# Titan_Teknic_v1p01b.net
KiCad netlist of a schematic drawn in EAGLE
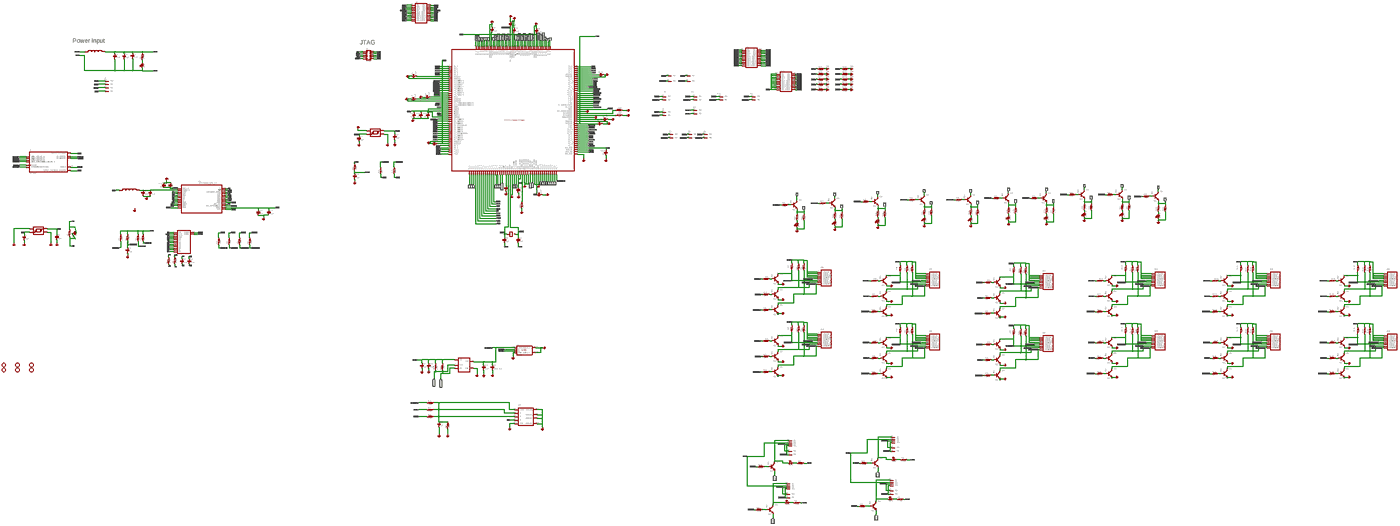
[diagram p0: schematic, sheet 1, overview]
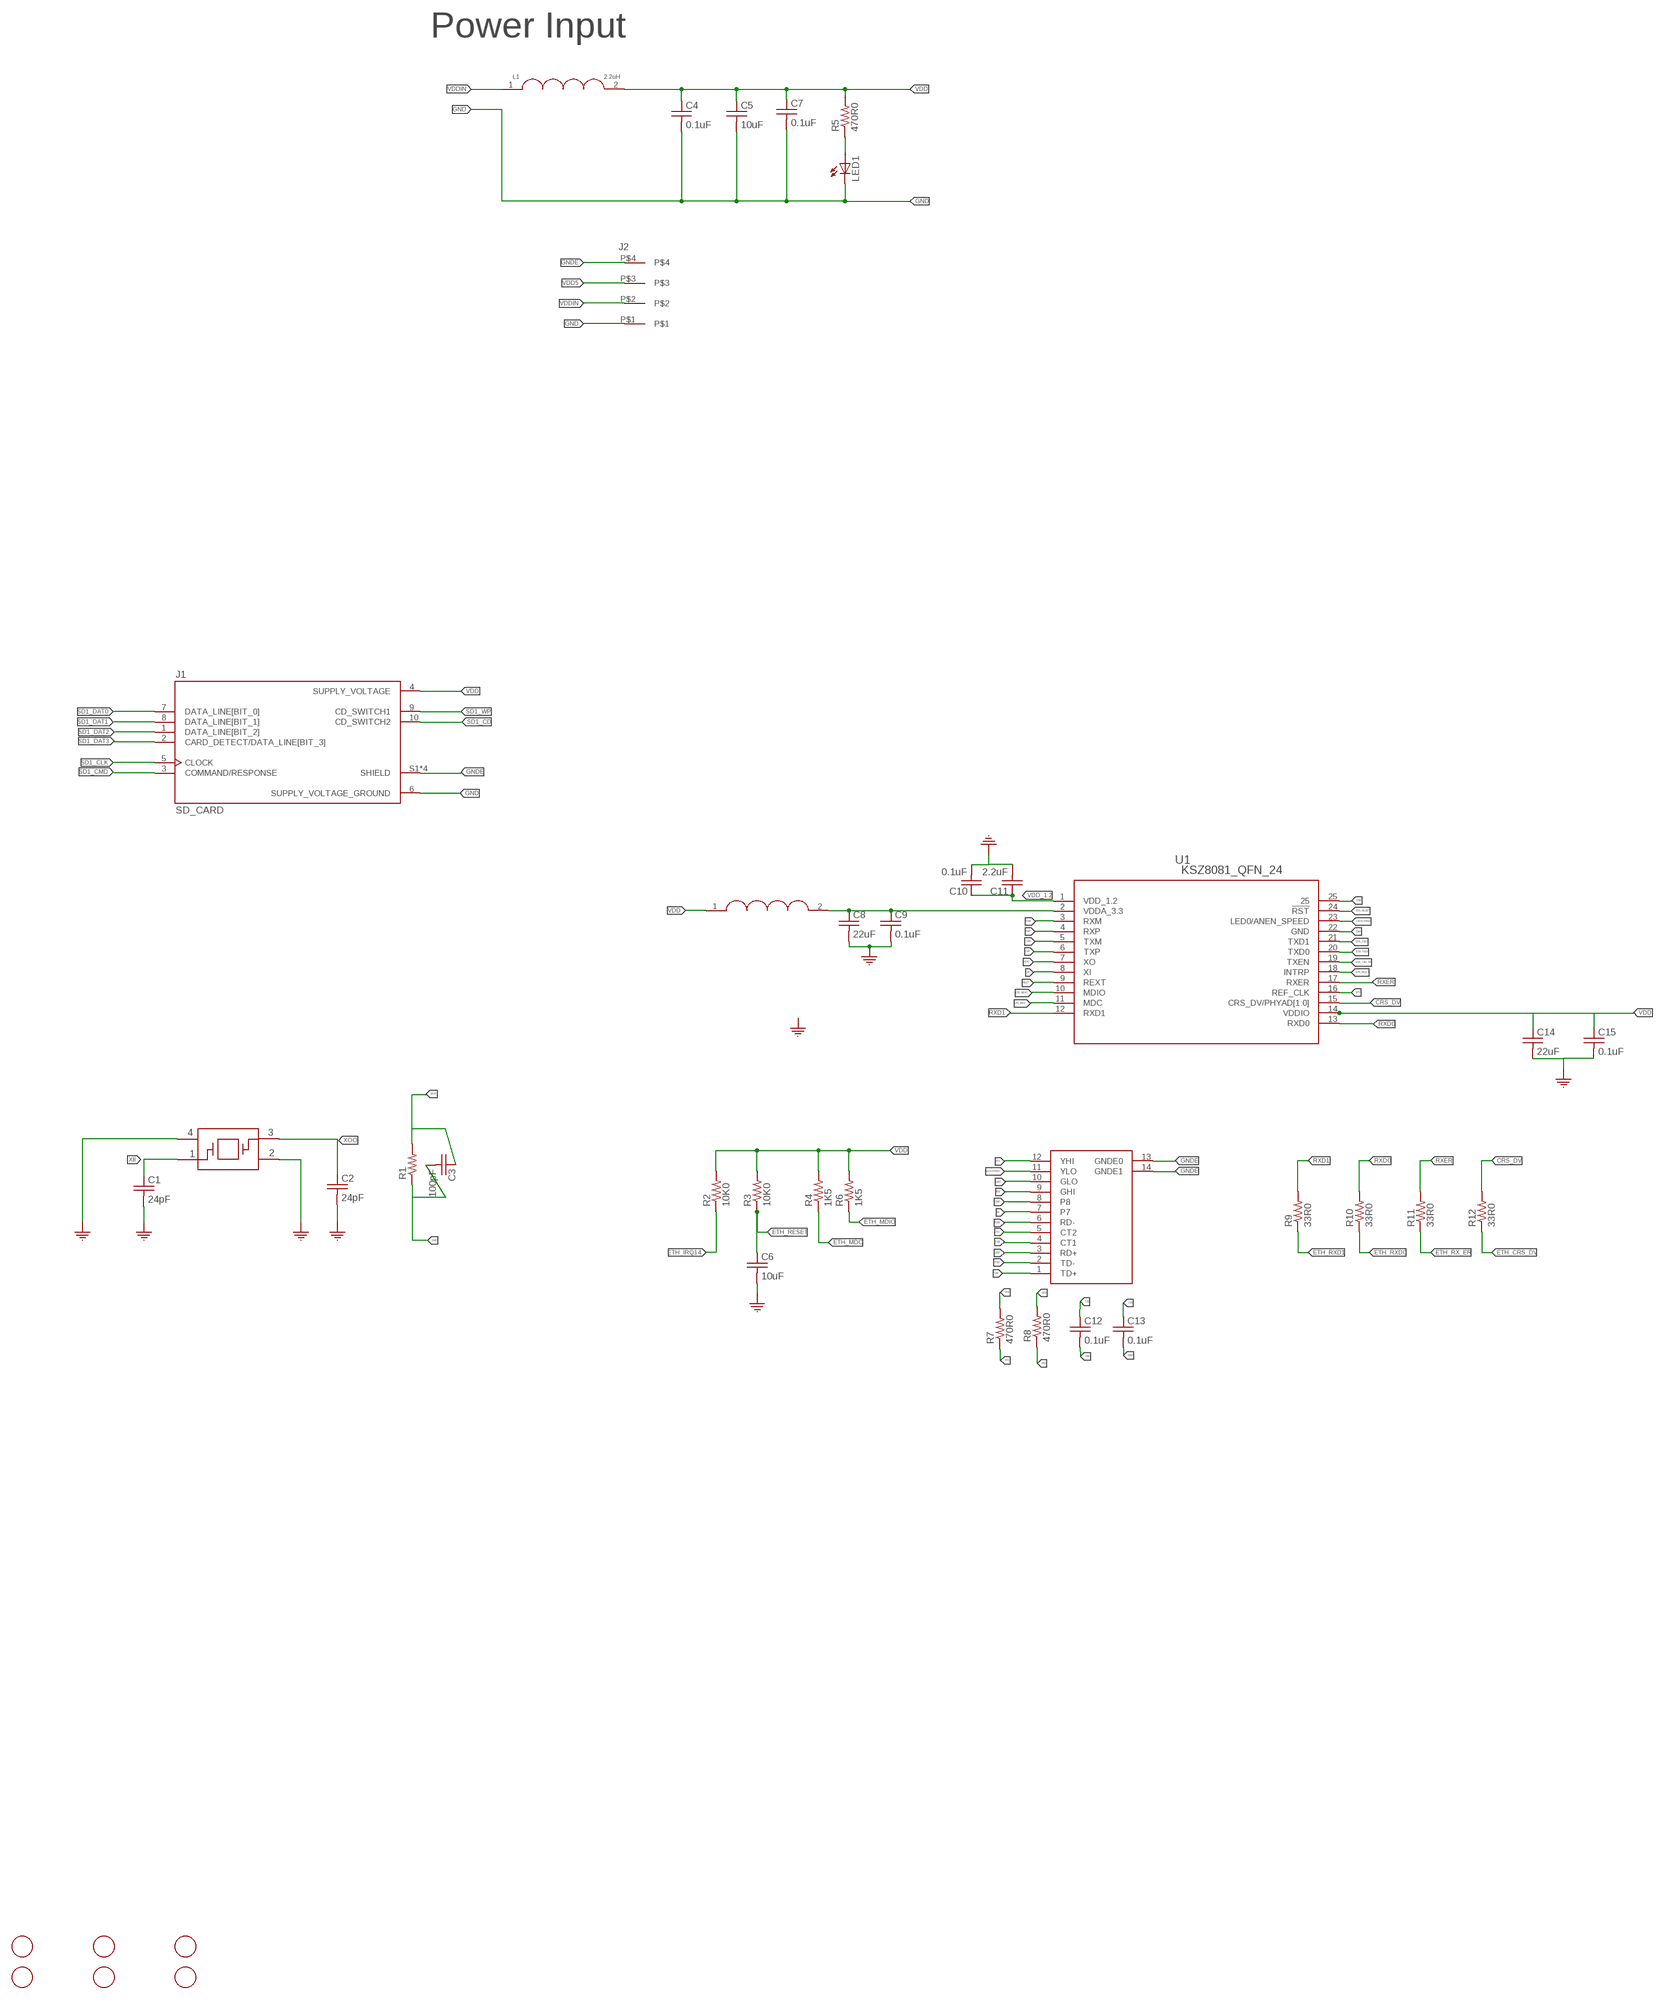
[diagram p1: schematic, sheet 1, part 1 of 6]
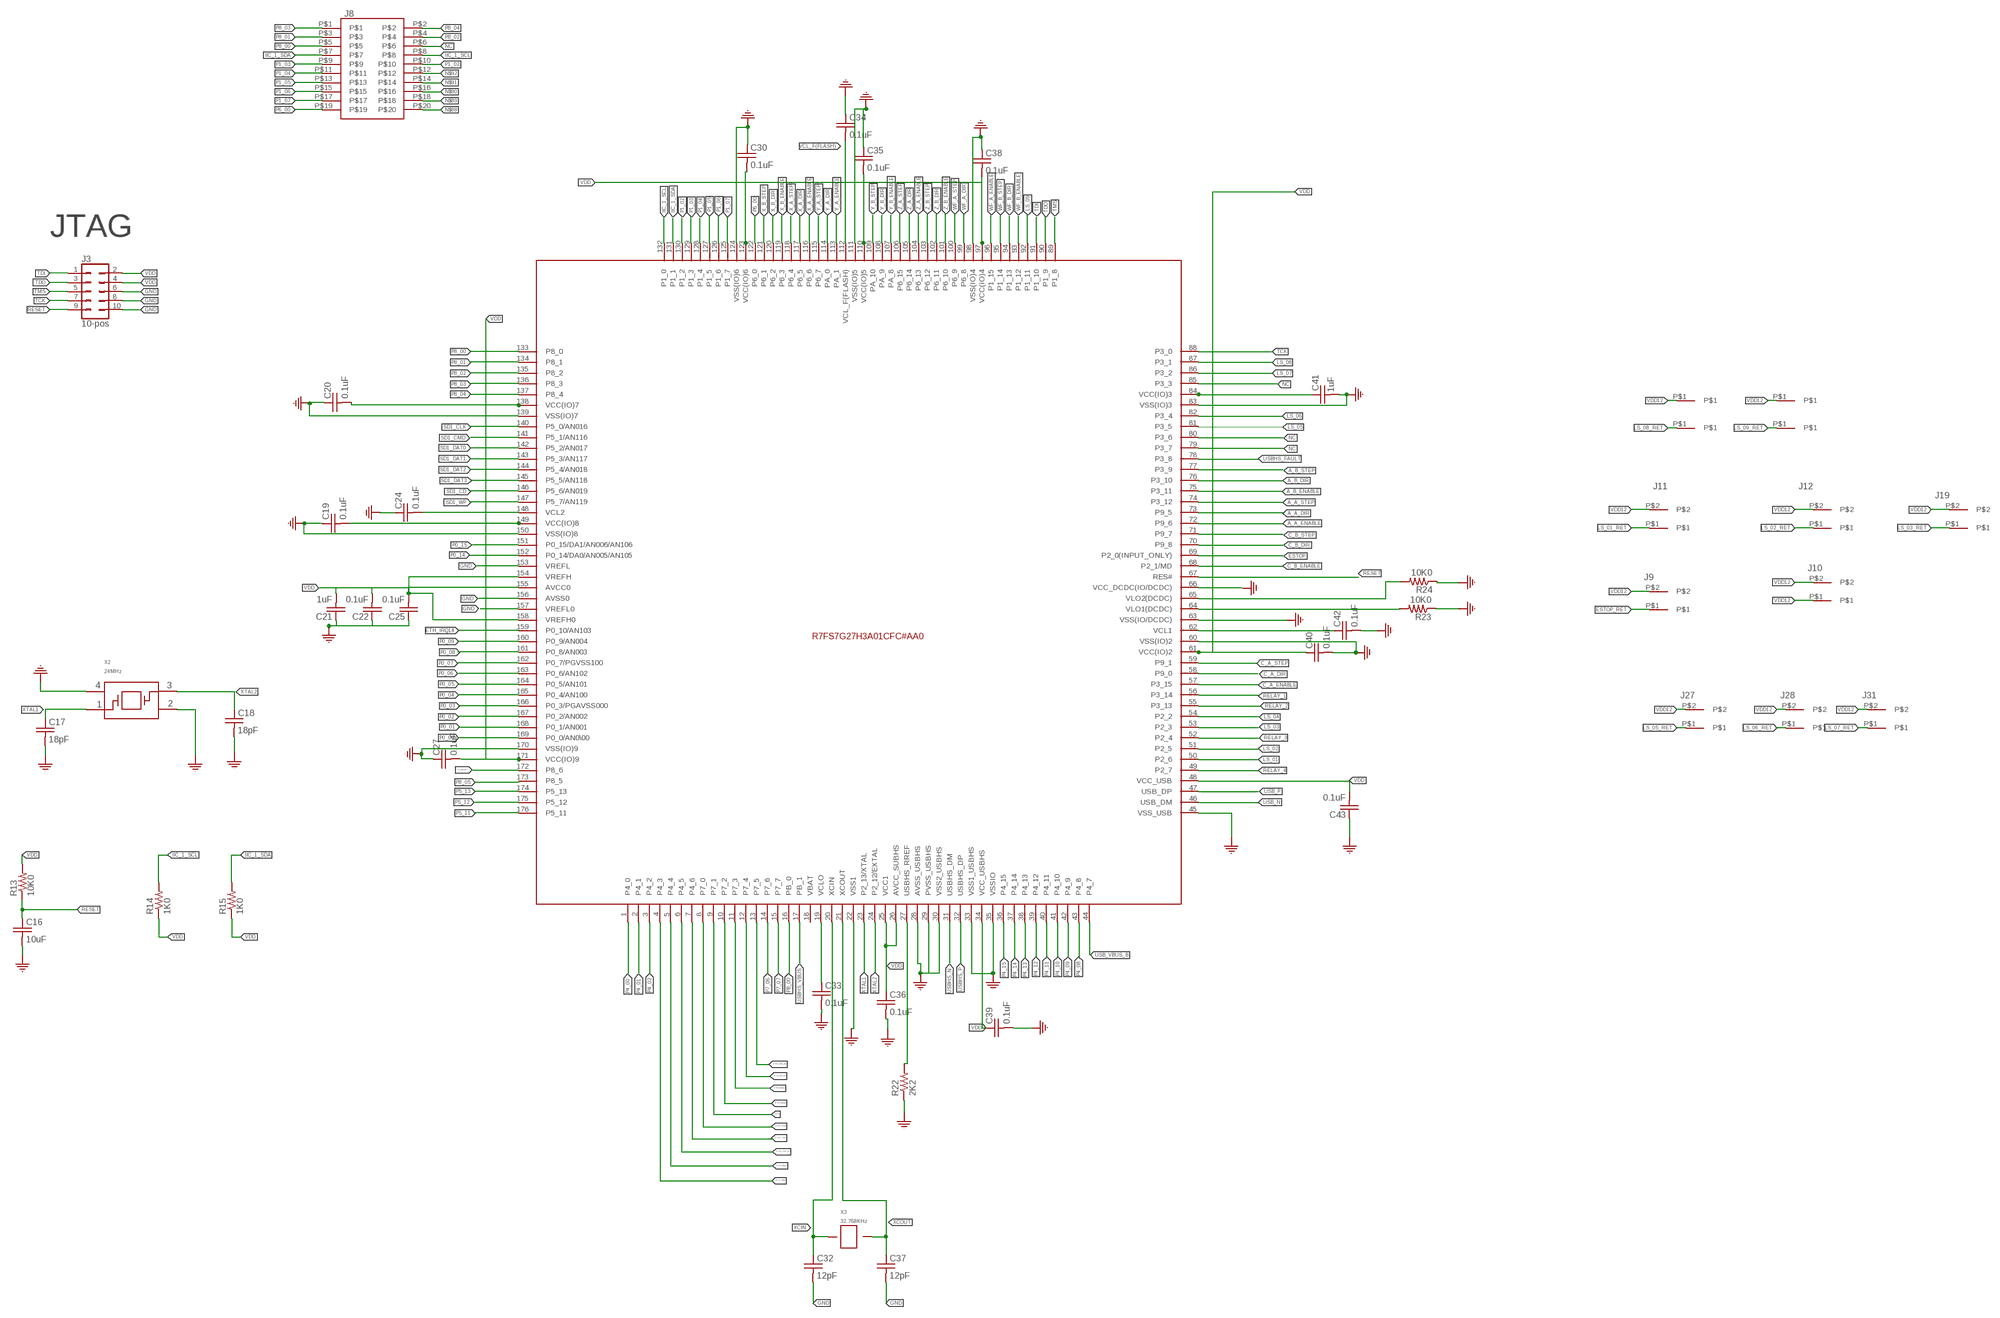
[diagram p2: schematic, sheet 1, part 2 of 6]
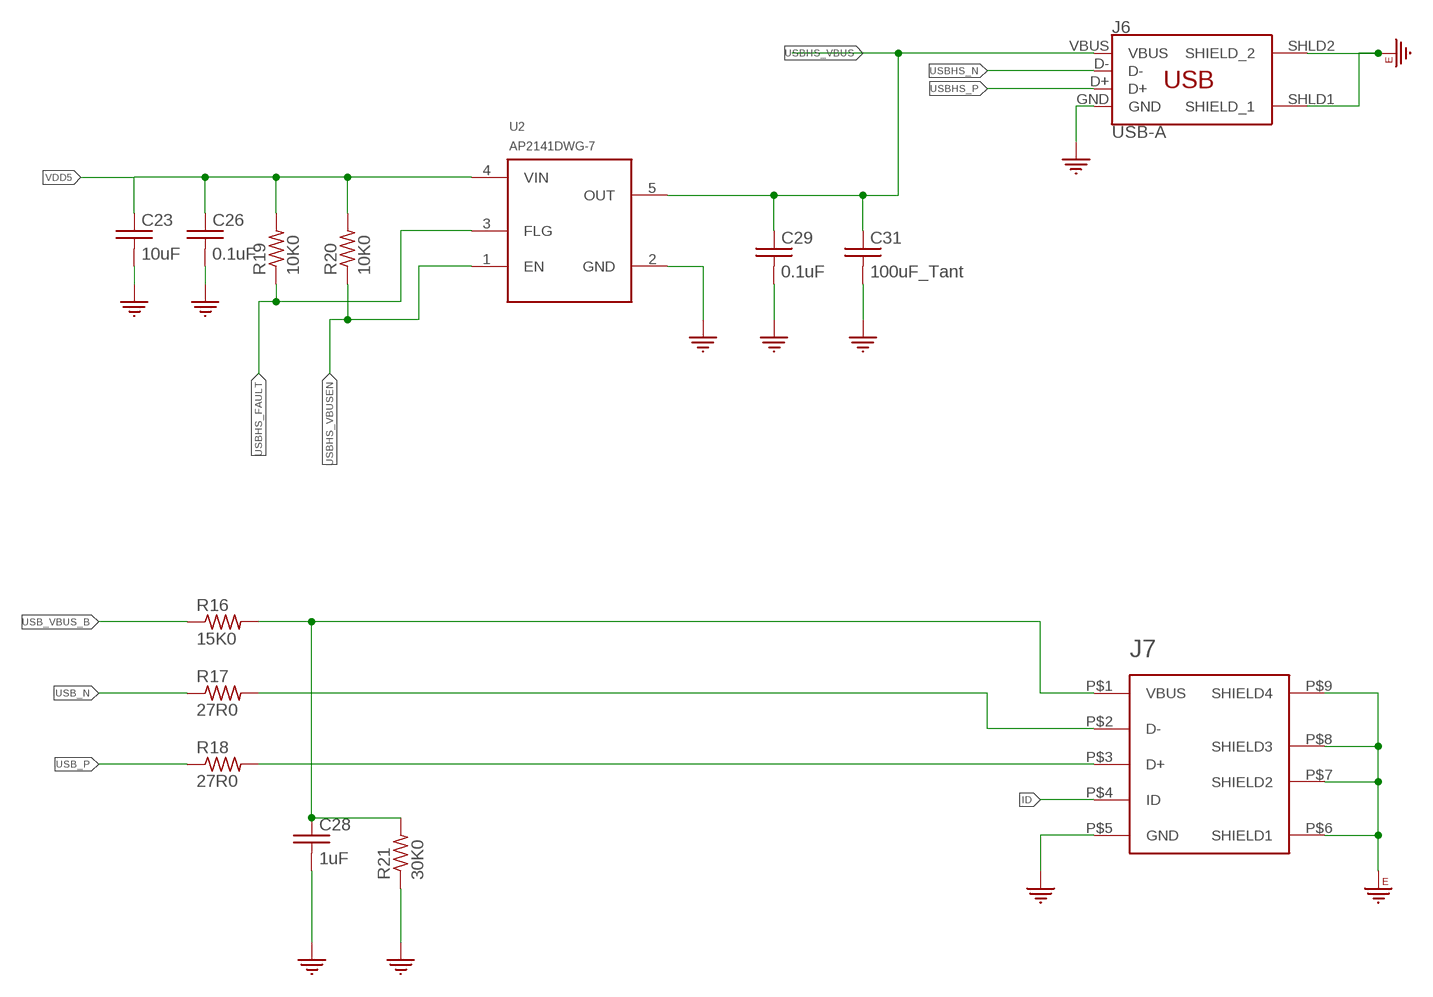
[diagram p3: schematic, sheet 1, part 3 of 6]
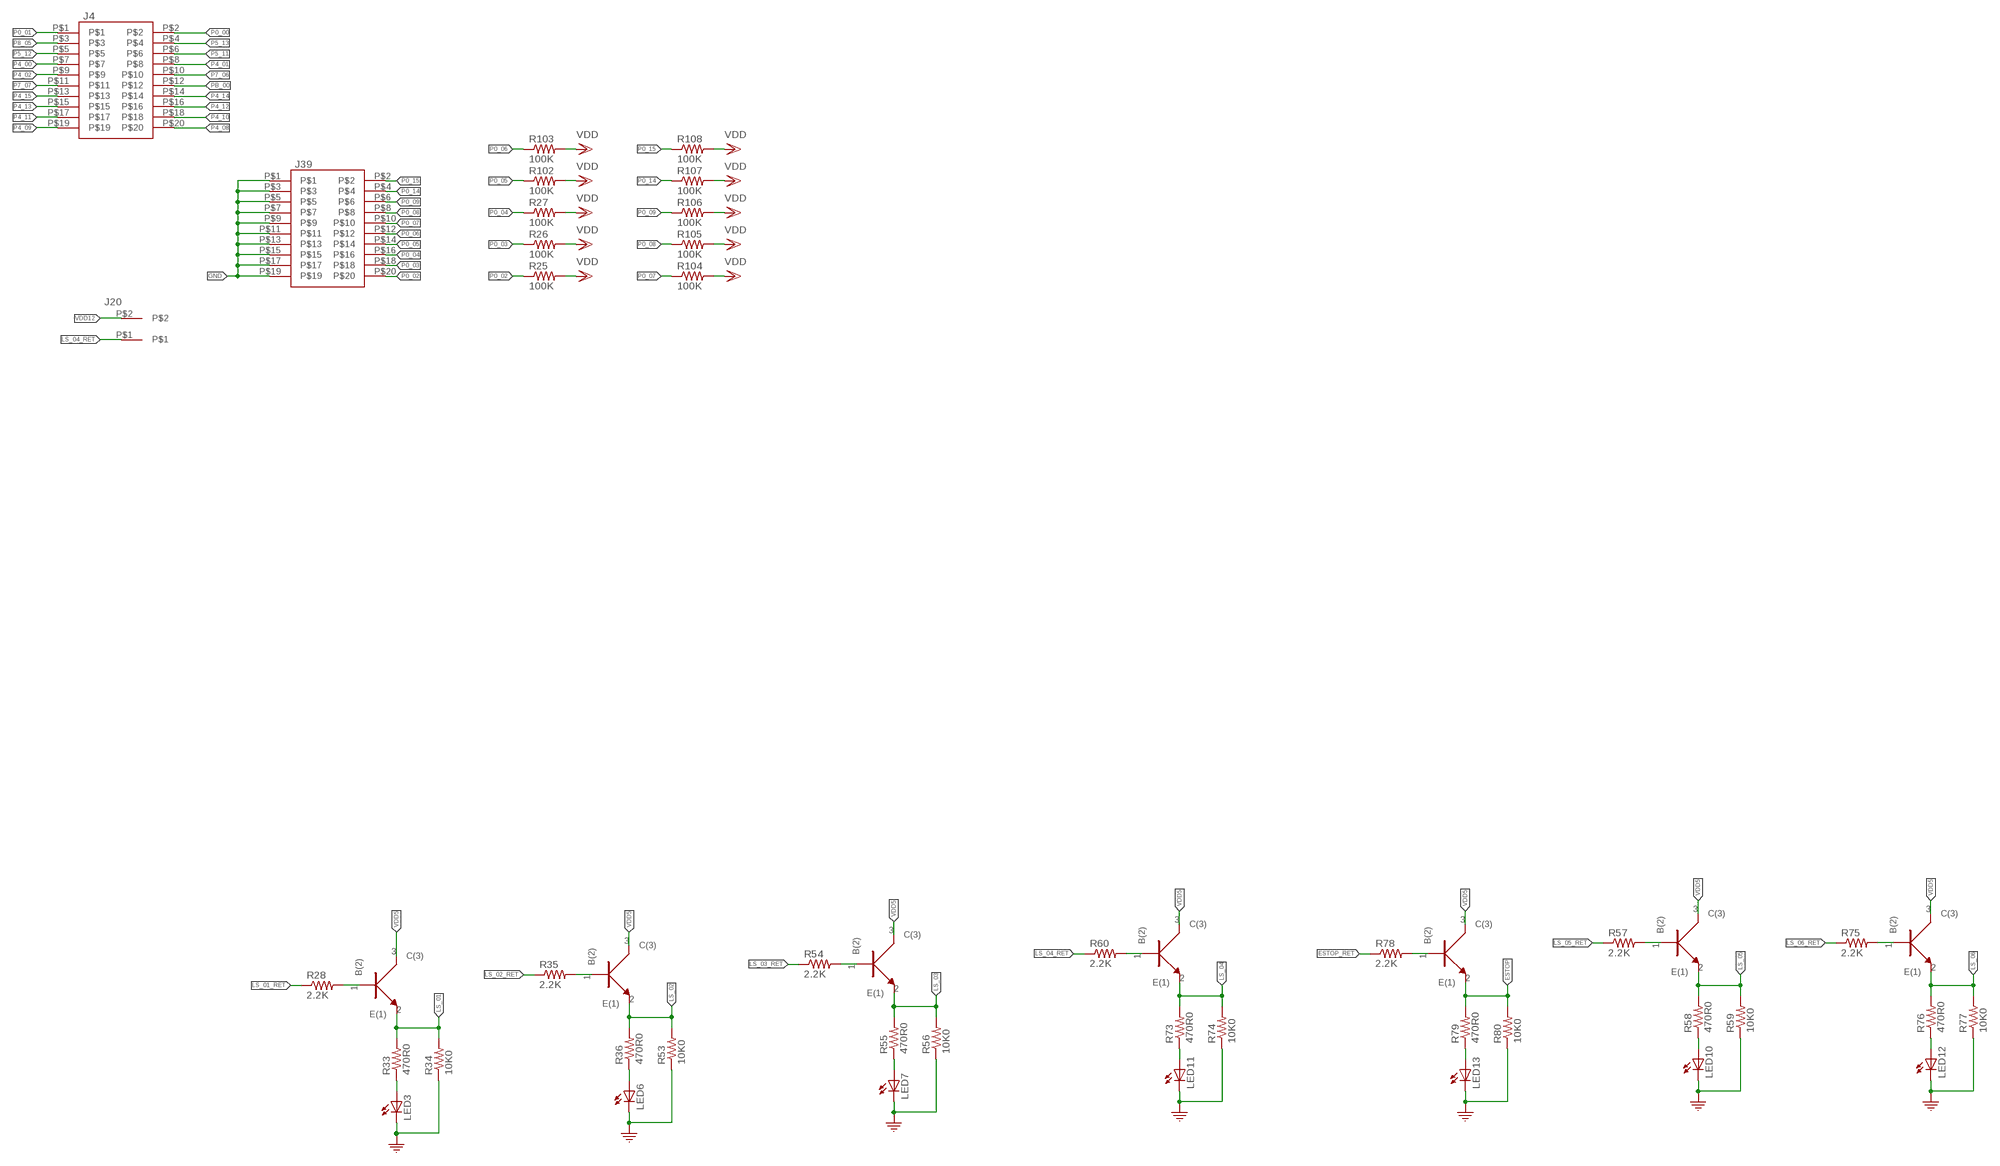
[diagram p4: schematic, sheet 1, part 4 of 6]
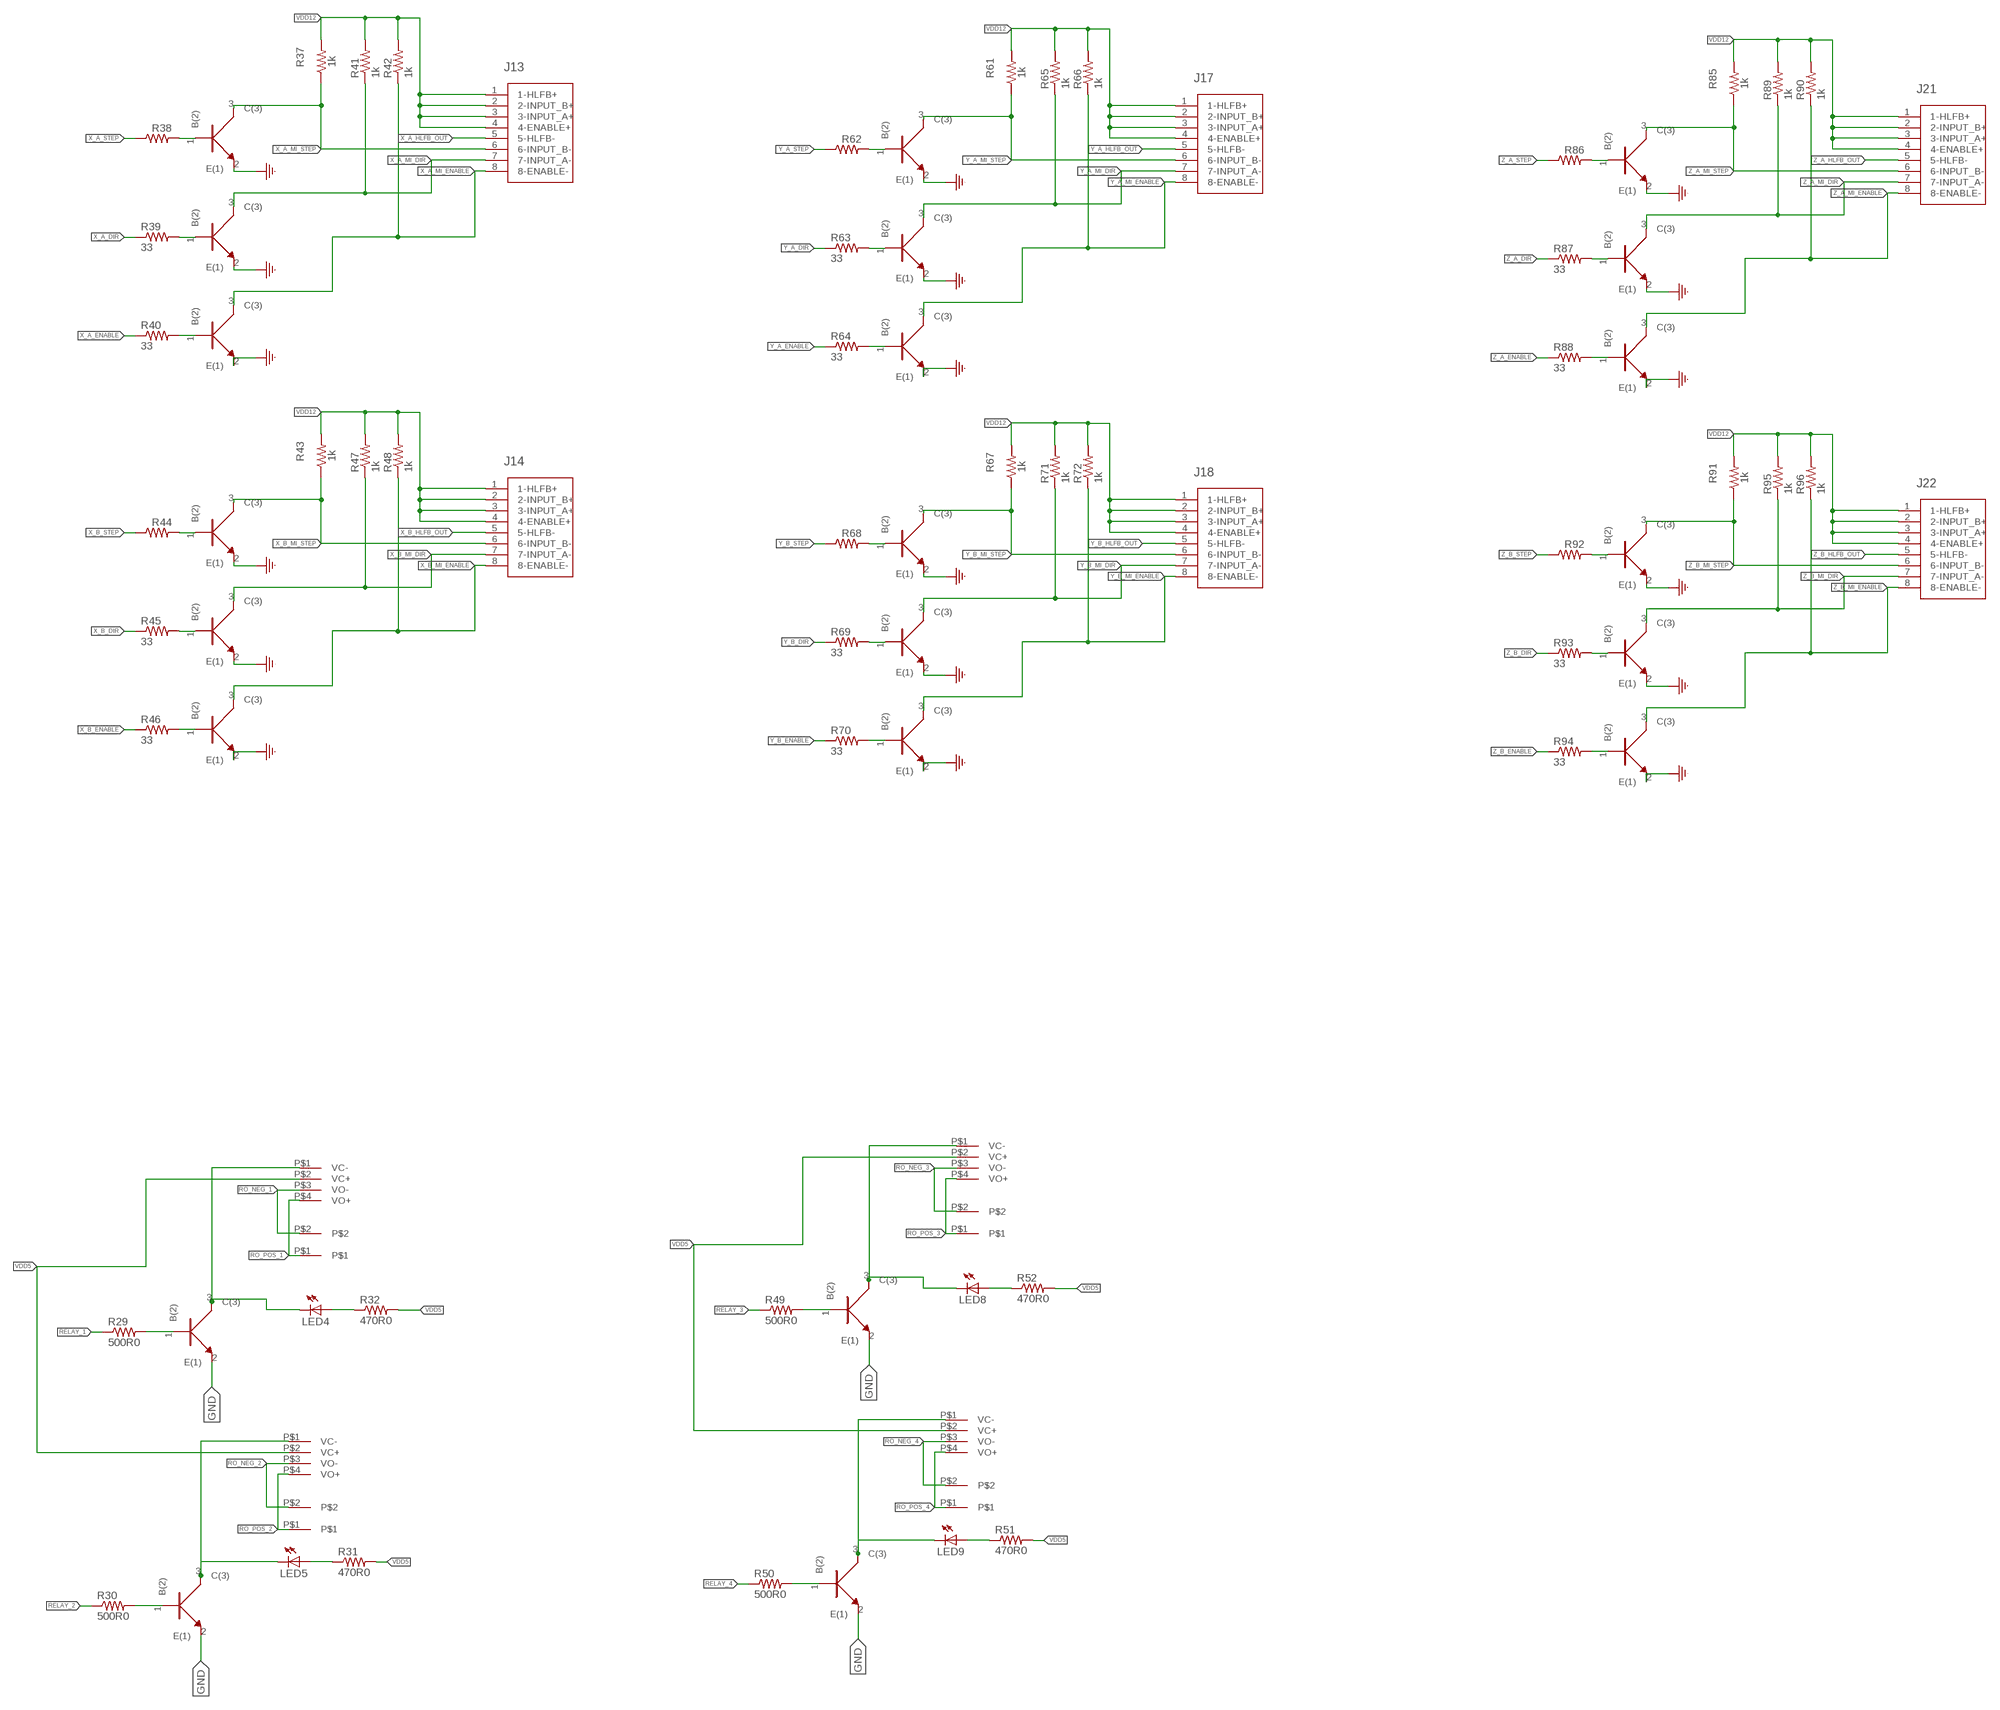
[diagram p5: schematic, sheet 1, part 5 of 6]
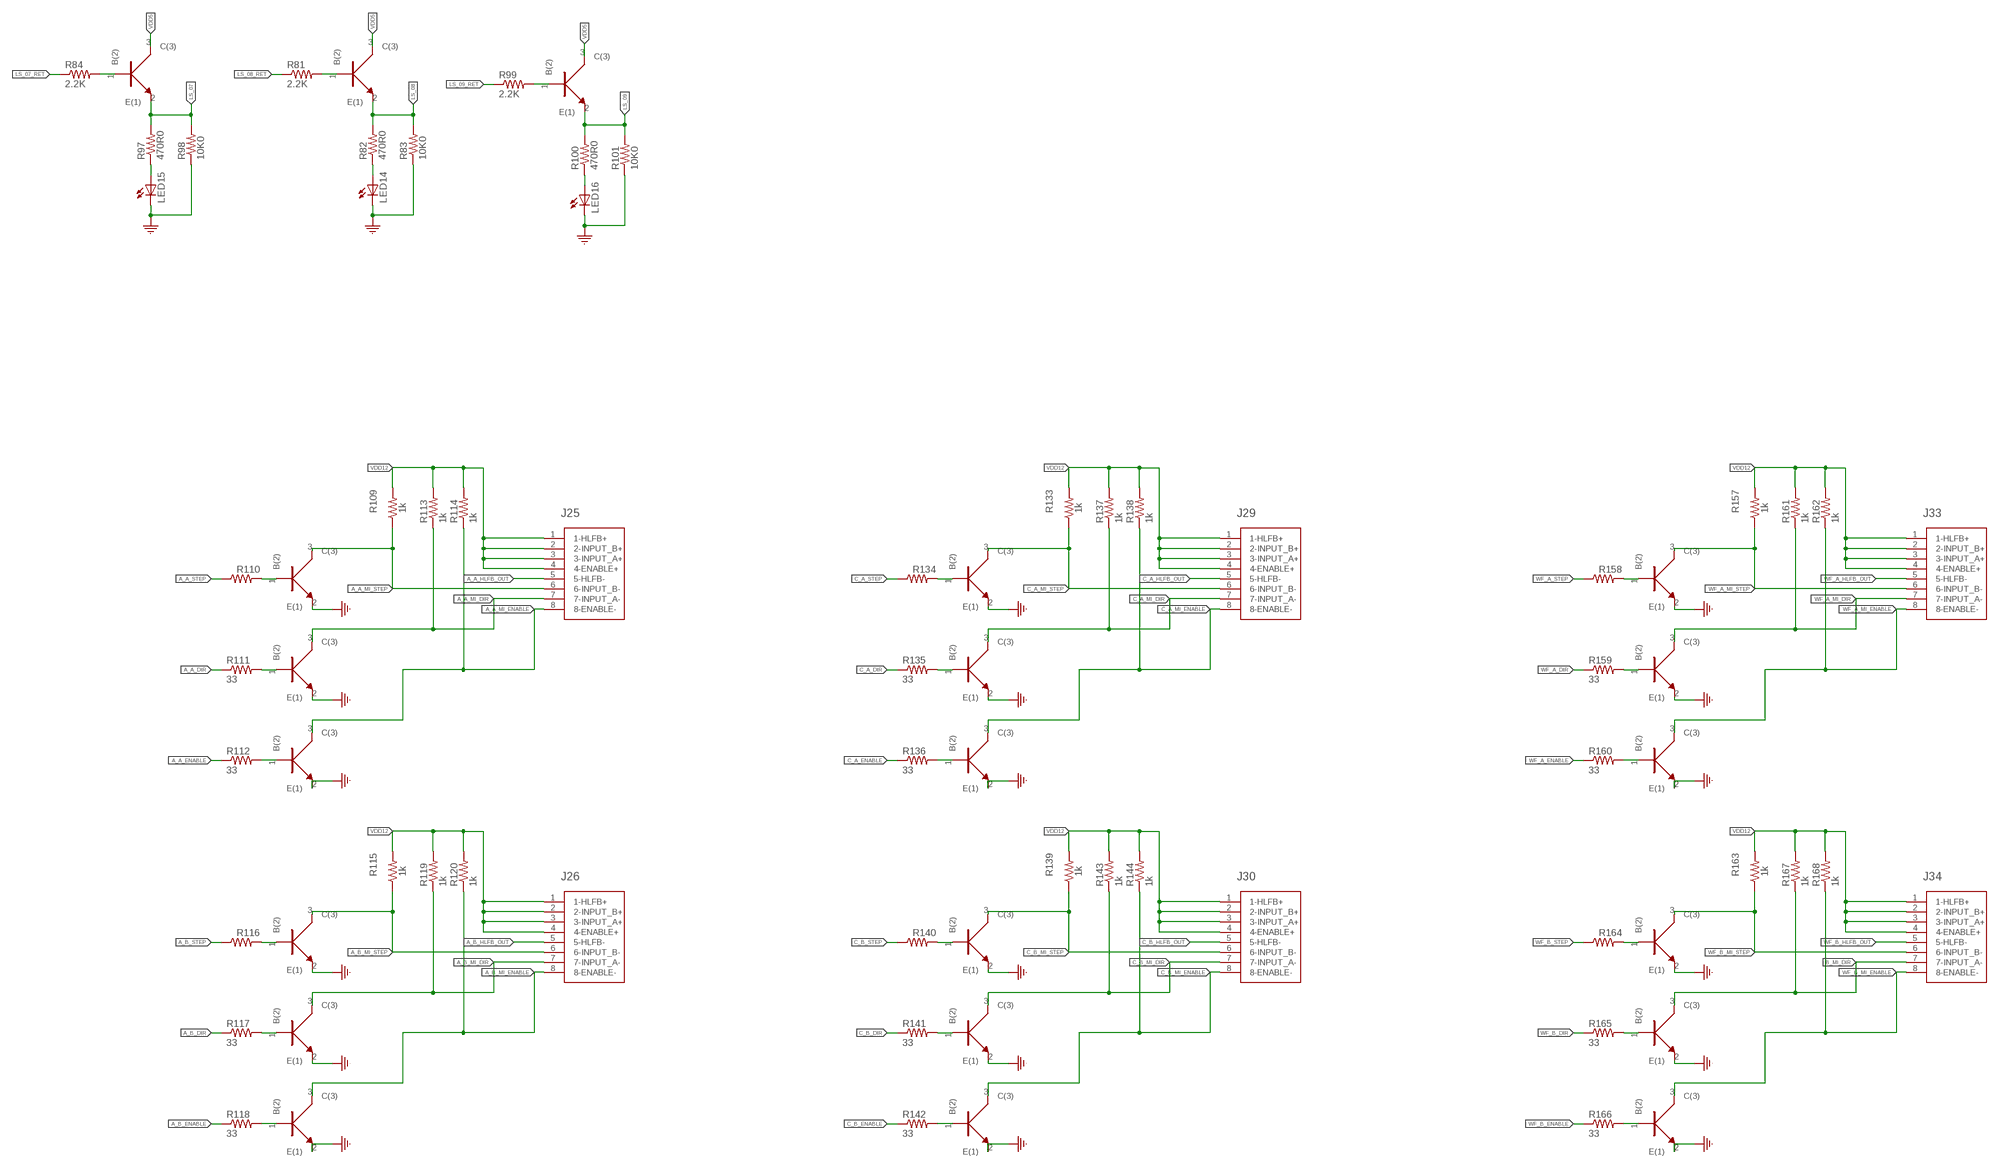
[diagram p6: schematic, sheet 1, part 6 of 6]

(export (version "E")
  (design (tool "Eeschema 10.0.6"))
  (components
    (comp (ref "AFID1")
      (value "FIDUCIAL_1MM")
      (footprint "eagle-import:FIDUCIAL_1MM")
      (libsource (lib "eagle-import") (part "FIDUCIAL_1MM"))
    )
    (comp (ref "AFID2")
      (value "FIDUCIAL_1MM")
      (footprint "eagle-import:FIDUCIAL_1MM")
      (libsource (lib "eagle-import") (part "FIDUCIAL_1MM"))
    )
    (comp (ref "AFID3")
      (value "FIDUCIAL_1MM")
      (footprint "eagle-import:FIDUCIAL_1MM")
      (libsource (lib "eagle-import") (part "FIDUCIAL_1MM"))
    )
    (comp (ref "AFID4")
      (value "FIDUCIAL_1MM")
      (footprint "eagle-import:FIDUCIAL_1MM")
      (libsource (lib "eagle-import") (part "FIDUCIAL_1MM"))
    )
    (comp (ref "AFID5")
      (value "FIDUCIAL_1MM")
      (footprint "eagle-import:FIDUCIAL_1MM")
      (libsource (lib "eagle-import") (part "FIDUCIAL_1MM"))
    )
    (comp (ref "AFID6")
      (value "FIDUCIAL_1MM")
      (footprint "eagle-import:FIDUCIAL_1MM")
      (libsource (lib "eagle-import") (part "FIDUCIAL_1MM"))
    )
    (comp (ref "C1")
      (value "24pF")
      (footprint "eagle-import:0402")
      (fields (field (name "PARTNO") "CC0402GRNPO9BN240"))
      (libsource (lib "eagle-import") (part "C_0402_24PF"))
    )
    (comp (ref "C2")
      (value "24pF")
      (footprint "eagle-import:0402")
      (fields (field (name "PARTNO") "CC0402GRNPO9BN240"))
      (libsource (lib "eagle-import") (part "C_0402_24PF"))
    )
    (comp (ref "C3")
      (value "100pF")
      (footprint "eagle-import:0402")
      (fields (field (name "PARTNO") "CL05C101JB5NNNC"))
      (libsource (lib "eagle-import") (part "C_0402_100PF"))
    )
    (comp (ref "C4")
      (value "0.1uF")
      (footprint "eagle-import:0402")
      (fields (field (name "PARTNO") "CL05F104ZO5NNNC"))
      (libsource (lib "eagle-import") (part "C_0402_0.1UF"))
    )
    (comp (ref "C5")
      (value "10uF")
      (footprint "eagle-import:0402")
      (fields (field (name "PARTNO") "CL05A106MP8NUB8"))
      (libsource (lib "eagle-import") (part "C_0402_10UF"))
    )
    (comp (ref "C6")
      (value "10uF")
      (footprint "eagle-import:0402")
      (fields (field (name "PARTNO") "CL05A106MP8NUB8"))
      (libsource (lib "eagle-import") (part "C_0402_10UF"))
    )
    (comp (ref "C7")
      (value "0.1uF")
      (footprint "eagle-import:0402")
      (fields (field (name "PARTNO") "CL05F104ZO5NNNC"))
      (libsource (lib "eagle-import") (part "C_0402_0.1UF"))
    )
    (comp (ref "C8")
      (value "22uF")
      (footprint "eagle-import:0402")
      (fields (field (name "PARTNO") "CL05A226MQ5N6J8"))
      (libsource (lib "eagle-import") (part "C_0402_22UF"))
    )
    (comp (ref "C9")
      (value "0.1uF")
      (footprint "eagle-import:0402")
      (fields (field (name "PARTNO") "CL05F104ZO5NNNC"))
      (libsource (lib "eagle-import") (part "C_0402_0.1UF"))
    )
    (comp (ref "C10")
      (value "0.1uF")
      (footprint "eagle-import:0402")
      (fields (field (name "PARTNO") "CL05F104ZO5NNNC"))
      (libsource (lib "eagle-import") (part "C_0402_0.1UF"))
    )
    (comp (ref "C11")
      (value "2.2uF")
      (footprint "eagle-import:0402")
      (fields (field (name "PARTNO") "GRM155C81C225ME15D"))
      (libsource (lib "eagle-import") (part "C_0402_2.2UF"))
    )
    (comp (ref "C12")
      (value "0.1uF")
      (footprint "eagle-import:0402")
      (fields (field (name "PARTNO") "CL05F104ZO5NNNC"))
      (libsource (lib "eagle-import") (part "C_0402_0.1UF"))
    )
    (comp (ref "C13")
      (value "0.1uF")
      (footprint "eagle-import:0402")
      (fields (field (name "PARTNO") "CL05F104ZO5NNNC"))
      (libsource (lib "eagle-import") (part "C_0402_0.1UF"))
    )
    (comp (ref "C14")
      (value "22uF")
      (footprint "eagle-import:0402")
      (fields (field (name "PARTNO") "CL05A226MQ5N6J8"))
      (libsource (lib "eagle-import") (part "C_0402_22UF"))
    )
    (comp (ref "C15")
      (value "0.1uF")
      (footprint "eagle-import:0402")
      (fields (field (name "PARTNO") "CL05F104ZO5NNNC"))
      (libsource (lib "eagle-import") (part "C_0402_0.1UF"))
    )
    (comp (ref "C16")
      (value "10uF")
      (footprint "eagle-import:0402")
      (fields (field (name "PARTNO") "CL05A106MP8NUB8"))
      (libsource (lib "eagle-import") (part "C_0402_10UF"))
    )
    (comp (ref "C17")
      (value "18pF")
      (footprint "eagle-import:0402")
      (fields (field (name "PARTNO") "UMK105CG180JV-F"))
      (libsource (lib "eagle-import") (part "C_0402_18PF"))
    )
    (comp (ref "C18")
      (value "18pF")
      (footprint "eagle-import:0402")
      (fields (field (name "PARTNO") "UMK105CG180JV-F"))
      (libsource (lib "eagle-import") (part "C_0402_18PF"))
    )
    (comp (ref "C19")
      (value "0.1uF")
      (footprint "eagle-import:0402")
      (fields (field (name "PARTNO") "CL05F104ZO5NNNC"))
      (libsource (lib "eagle-import") (part "C_0402_0.1UF"))
    )
    (comp (ref "C20")
      (value "0.1uF")
      (footprint "eagle-import:0402")
      (fields (field (name "PARTNO") "CL05F104ZO5NNNC"))
      (libsource (lib "eagle-import") (part "C_0402_0.1UF"))
    )
    (comp (ref "C21")
      (value "1uF")
      (footprint "eagle-import:0402")
      (fields (field (name "PARTNO") "CL05A105KO5NNNC"))
      (libsource (lib "eagle-import") (part "C_0402_1UF"))
    )
    (comp (ref "C22")
      (value "0.1uF")
      (footprint "eagle-import:0402")
      (fields (field (name "PARTNO") "CL05F104ZO5NNNC"))
      (libsource (lib "eagle-import") (part "C_0402_0.1UF"))
    )
    (comp (ref "C23")
      (value "10uF")
      (footprint "eagle-import:0402")
      (fields (field (name "PARTNO") "CL05A106MP8NUB8"))
      (libsource (lib "eagle-import") (part "C_0402_10UF"))
    )
    (comp (ref "C24")
      (value "0.1uF")
      (footprint "eagle-import:0402")
      (fields (field (name "PARTNO") "CL05F104ZO5NNNC"))
      (libsource (lib "eagle-import") (part "C_0402_0.1UF"))
    )
    (comp (ref "C25")
      (value "0.1uF")
      (footprint "eagle-import:0402")
      (fields (field (name "PARTNO") "CL05F104ZO5NNNC"))
      (libsource (lib "eagle-import") (part "C_0402_0.1UF"))
    )
    (comp (ref "C26")
      (value "0.1uF")
      (footprint "eagle-import:0402")
      (fields (field (name "PARTNO") "CL05F104ZO5NNNC"))
      (libsource (lib "eagle-import") (part "C_0402_0.1UF"))
    )
    (comp (ref "C27")
      (value "0.1uF")
      (footprint "eagle-import:0402")
      (fields (field (name "PARTNO") "CL05F104ZO5NNNC"))
      (libsource (lib "eagle-import") (part "C_0402_0.1UF"))
    )
    (comp (ref "C28")
      (value "1uF")
      (footprint "eagle-import:0402")
      (fields (field (name "PARTNO") "CL05A105KO5NNNC"))
      (libsource (lib "eagle-import") (part "C_0402_1UF"))
    )
    (comp (ref "C29")
      (value "0.1uF")
      (footprint "eagle-import:0402")
      (fields (field (name "PARTNO") "CL05F104ZO5NNNC"))
      (libsource (lib "eagle-import") (part "C_0402_0.1UF"))
    )
    (comp (ref "C30")
      (value "0.1uF")
      (footprint "eagle-import:0402")
      (fields (field (name "PARTNO") "CL05F104ZO5NNNC"))
      (libsource (lib "eagle-import") (part "C_0402_0.1UF"))
    )
    (comp (ref "C31")
      (value "100uF_Tant")
      (footprint "eagle-import:C1210")
      (fields (field (name "PARTNO") "TLJT107M010R0900"))
      (libsource (lib "eagle-import") (part "C_1210_100UF_TANT"))
    )
    (comp (ref "C32")
      (value "12pF")
      (footprint "eagle-import:0402")
      (fields (field (name "PARTNO") "CL05C120JB5NNNC"))
      (libsource (lib "eagle-import") (part "C_0402_12PF"))
    )
    (comp (ref "C33")
      (value "0.1uF")
      (footprint "eagle-import:0402")
      (fields (field (name "PARTNO") "CL05F104ZO5NNNC"))
      (libsource (lib "eagle-import") (part "C_0402_0.1UF"))
    )
    (comp (ref "C34")
      (value "0.1uF")
      (footprint "eagle-import:0402")
      (fields (field (name "PARTNO") "CL05F104ZO5NNNC"))
      (libsource (lib "eagle-import") (part "C_0402_0.1UF"))
    )
    (comp (ref "C35")
      (value "0.1uF")
      (footprint "eagle-import:0402")
      (fields (field (name "PARTNO") "CL05F104ZO5NNNC"))
      (libsource (lib "eagle-import") (part "C_0402_0.1UF"))
    )
    (comp (ref "C36")
      (value "0.1uF")
      (footprint "eagle-import:0402")
      (fields (field (name "PARTNO") "CL05F104ZO5NNNC"))
      (libsource (lib "eagle-import") (part "C_0402_0.1UF"))
    )
    (comp (ref "C37")
      (value "12pF")
      (footprint "eagle-import:0402")
      (fields (field (name "PARTNO") "CL05C120JB5NNNC"))
      (libsource (lib "eagle-import") (part "C_0402_12PF"))
    )
    (comp (ref "C38")
      (value "0.1uF")
      (footprint "eagle-import:0402")
      (fields (field (name "PARTNO") "CL05F104ZO5NNNC"))
      (libsource (lib "eagle-import") (part "C_0402_0.1UF"))
    )
    (comp (ref "C39")
      (value "0.1uF")
      (footprint "eagle-import:0402")
      (fields (field (name "PARTNO") "CL05F104ZO5NNNC"))
      (libsource (lib "eagle-import") (part "C_0402_0.1UF"))
    )
    (comp (ref "C40")
      (value "0.1uF")
      (footprint "eagle-import:0402")
      (fields (field (name "PARTNO") "CL05F104ZO5NNNC"))
      (libsource (lib "eagle-import") (part "C_0402_0.1UF"))
    )
    (comp (ref "C41")
      (value "1uF")
      (footprint "eagle-import:0402")
      (fields (field (name "PARTNO") "CL05A105KO5NNNC"))
      (libsource (lib "eagle-import") (part "C_0402_1UF"))
    )
    (comp (ref "C42")
      (value "0.1uF")
      (footprint "eagle-import:0402")
      (fields (field (name "PARTNO") "CL05F104ZO5NNNC"))
      (libsource (lib "eagle-import") (part "C_0402_0.1UF"))
    )
    (comp (ref "C43")
      (value "0.1uF")
      (footprint "eagle-import:0402")
      (fields (field (name "PARTNO") "CL05F104ZO5NNNC"))
      (libsource (lib "eagle-import") (part "C_0402_0.1UF"))
    )
    (comp (ref "FB1")
      (value "FB2_603")
      (footprint "eagle-import:0603")
      (fields (field (name "PARTNO") "BLM18PG121SN1D"))
      (libsource (lib "eagle-import") (part "FB_0603_120_OHM0603"))
    )
    (comp (ref "J1")
      (value "SD_CARD")
      (footprint "eagle-import:SD_CARD")
      (fields (field (name "MF") "Amphenol ICC") (field (name "PARTNO") "114-00841-68"))
      (libsource (lib "eagle-import") (part "SD_CARD_1140084168"))
    )
    (comp (ref "J2")
      (value "4-pos")
      (footprint "eagle-import:1X4_3.81MM_PITCH")
      (fields (field (name "PARTNO") "691322310004"))
      (libsource (lib "eagle-import") (part "3.81MM_1_X_4_RT_ANGLE_PLUG_HEADER"))
    )
    (comp (ref "J3")
      (value "10-pos")
      (footprint "eagle-import:2X5")
      (fields (field (name "PARTNO") "PH2RA-10-UA"))
      (libsource (lib "eagle-import") (part "CONN_05X2_RAPTH"))
    )
    (comp (ref "J4")
      (value "20-pos")
      (footprint "eagle-import:2_X_10_.1_INCH")
      (fields (field (name "PARTNO") "67996-420HLF"))
      (libsource (lib "eagle-import") (part "2_X_10_HEADER_GENERIC"))
    )
    (comp (ref "J6")
      (value "USB-A")
      (footprint "eagle-import:USB_A_SMT")
      (fields (field (name "PARTNO") "87583-3010RPALF"))
      (libsource (lib "eagle-import") (part "USB_A"))
    )
    (comp (ref "J7")
      (value "USB-B-Micro")
      (footprint "eagle-import:USB_MICRO-B")
      (fields (field (name "PARTNO") "10118192-0002LF"))
      (libsource (lib "eagle-import") (part "USB_MICRO-B"))
    )
    (comp (ref "J8")
      (value "2_X_10_HEADER_GENERIC")
      (footprint "eagle-import:2_X_10_.1_INCH")
      (fields (field (name "PARTNO") "67996-420HLF"))
      (libsource (lib "eagle-import") (part "2_X_10_HEADER_GENERIC"))
    )
    (comp (ref "J9")
      (value "2-pos")
      (footprint "eagle-import:2_3.81MM_PITCH")
      (fields (field (name "PARTNO") "691322310002"))
      (libsource (lib "eagle-import") (part "3.81MM_1_X_2_RT_ANGLE_PLUG_HEADER"))
    )
    (comp (ref "J10")
      (value "2-pos")
      (footprint "eagle-import:2_3.81MM_PITCH")
      (fields (field (name "PARTNO") "691322310002"))
      (libsource (lib "eagle-import") (part "3.81MM_1_X_2_RT_ANGLE_PLUG_HEADER"))
    )
    (comp (ref "J11")
      (value "2-pos")
      (footprint "eagle-import:2_3.81MM_PITCH")
      (fields (field (name "PARTNO") "691322310002"))
      (libsource (lib "eagle-import") (part "3.81MM_1_X_2_RT_ANGLE_PLUG_HEADER"))
    )
    (comp (ref "J12")
      (value "2-pos")
      (footprint "eagle-import:2_3.81MM_PITCH")
      (fields (field (name "PARTNO") "691322310002"))
      (libsource (lib "eagle-import") (part "3.81MM_1_X_2_RT_ANGLE_PLUG_HEADER"))
    )
    (comp (ref "J13")
      (value "TEKNIC_MOTOR_8PIN")
      (footprint "eagle-import:CON_39281083")
      (fields
        (field (name "MANUFACTURER_PART_NUMBER") "39281083")
        (field (name "COPYRIGHT") "Copyright (C) 2022 Ultra Librarian. All rights reserved.")
      )
      (libsource (lib "eagle-import") (part "TEKNIC_MOTOR_8PIN"))
    )
    (comp (ref "J14")
      (value "TEKNIC_MOTOR_8PIN")
      (footprint "eagle-import:CON_39281083")
      (fields
        (field (name "MANUFACTURER_PART_NUMBER") "39281083")
        (field (name "COPYRIGHT") "Copyright (C) 2022 Ultra Librarian. All rights reserved.")
      )
      (libsource (lib "eagle-import") (part "TEKNIC_MOTOR_8PIN"))
    )
    (comp (ref "J15")
      (value "2-pos")
      (footprint "eagle-import:2_3.81MM_PITCH")
      (fields (field (name "PARTNO") "691322310002"))
      (libsource (lib "eagle-import") (part "3.81MM_1_X_2_RT_ANGLE_PLUG_HEADER"))
    )
    (comp (ref "J16")
      (value "2-pos")
      (footprint "eagle-import:2_3.81MM_PITCH")
      (fields (field (name "PARTNO") "691322310002"))
      (libsource (lib "eagle-import") (part "3.81MM_1_X_2_RT_ANGLE_PLUG_HEADER"))
    )
    (comp (ref "J17")
      (value "TEKNIC_MOTOR_8PIN")
      (footprint "eagle-import:CON_39281083")
      (fields
        (field (name "MANUFACTURER_PART_NUMBER") "39281083")
        (field (name "COPYRIGHT") "Copyright (C) 2022 Ultra Librarian. All rights reserved.")
      )
      (libsource (lib "eagle-import") (part "TEKNIC_MOTOR_8PIN"))
    )
    (comp (ref "J18")
      (value "TEKNIC_MOTOR_8PIN")
      (footprint "eagle-import:CON_39281083")
      (fields
        (field (name "MANUFACTURER_PART_NUMBER") "39281083")
        (field (name "COPYRIGHT") "Copyright (C) 2022 Ultra Librarian. All rights reserved.")
      )
      (libsource (lib "eagle-import") (part "TEKNIC_MOTOR_8PIN"))
    )
    (comp (ref "J19")
      (value "2-pos")
      (footprint "eagle-import:2_3.81MM_PITCH")
      (fields (field (name "PARTNO") "691322310002"))
      (libsource (lib "eagle-import") (part "3.81MM_1_X_2_RT_ANGLE_PLUG_HEADER"))
    )
    (comp (ref "J20")
      (value "2-pos")
      (footprint "eagle-import:2_3.81MM_PITCH")
      (fields (field (name "PARTNO") "691322310002"))
      (libsource (lib "eagle-import") (part "3.81MM_1_X_2_RT_ANGLE_PLUG_HEADER"))
    )
    (comp (ref "J21")
      (value "TEKNIC_MOTOR_8PIN")
      (footprint "eagle-import:CON_39281083")
      (fields
        (field (name "MANUFACTURER_PART_NUMBER") "39281083")
        (field (name "COPYRIGHT") "Copyright (C) 2022 Ultra Librarian. All rights reserved.")
      )
      (libsource (lib "eagle-import") (part "TEKNIC_MOTOR_8PIN"))
    )
    (comp (ref "J22")
      (value "TEKNIC_MOTOR_8PIN")
      (footprint "eagle-import:CON_39281083")
      (fields
        (field (name "MANUFACTURER_PART_NUMBER") "39281083")
        (field (name "COPYRIGHT") "Copyright (C) 2022 Ultra Librarian. All rights reserved.")
      )
      (libsource (lib "eagle-import") (part "TEKNIC_MOTOR_8PIN"))
    )
    (comp (ref "J23")
      (value "2-pos")
      (footprint "eagle-import:2_3.81MM_PITCH")
      (fields (field (name "PARTNO") "691322310002"))
      (libsource (lib "eagle-import") (part "3.81MM_1_X_2_RT_ANGLE_PLUG_HEADER"))
    )
    (comp (ref "J24")
      (value "2-pos")
      (footprint "eagle-import:2_3.81MM_PITCH")
      (fields (field (name "PARTNO") "691322310002"))
      (libsource (lib "eagle-import") (part "3.81MM_1_X_2_RT_ANGLE_PLUG_HEADER"))
    )
    (comp (ref "J25")
      (value "TEKNIC_MOTOR_8PIN")
      (footprint "eagle-import:CON_39281083")
      (fields
        (field (name "MANUFACTURER_PART_NUMBER") "39281083")
        (field (name "COPYRIGHT") "Copyright (C) 2022 Ultra Librarian. All rights reserved.")
      )
      (libsource (lib "eagle-import") (part "TEKNIC_MOTOR_8PIN"))
    )
    (comp (ref "J26")
      (value "TEKNIC_MOTOR_8PIN")
      (footprint "eagle-import:CON_39281083")
      (fields
        (field (name "MANUFACTURER_PART_NUMBER") "39281083")
        (field (name "COPYRIGHT") "Copyright (C) 2022 Ultra Librarian. All rights reserved.")
      )
      (libsource (lib "eagle-import") (part "TEKNIC_MOTOR_8PIN"))
    )
    (comp (ref "J27")
      (value "2-pos")
      (footprint "eagle-import:2_3.81MM_PITCH")
      (fields (field (name "PARTNO") "691322310002"))
      (libsource (lib "eagle-import") (part "3.81MM_1_X_2_RT_ANGLE_PLUG_HEADER"))
    )
    (comp (ref "J28")
      (value "2-pos")
      (footprint "eagle-import:2_3.81MM_PITCH")
      (fields (field (name "PARTNO") "691322310002"))
      (libsource (lib "eagle-import") (part "3.81MM_1_X_2_RT_ANGLE_PLUG_HEADER"))
    )
    (comp (ref "J29")
      (value "TEKNIC_MOTOR_8PIN")
      (footprint "eagle-import:CON_39281083")
      (fields
        (field (name "MANUFACTURER_PART_NUMBER") "39281083")
        (field (name "COPYRIGHT") "Copyright (C) 2022 Ultra Librarian. All rights reserved.")
      )
      (libsource (lib "eagle-import") (part "TEKNIC_MOTOR_8PIN"))
    )
    (comp (ref "J30")
      (value "TEKNIC_MOTOR_8PIN")
      (footprint "eagle-import:CON_39281083")
      (fields
        (field (name "MANUFACTURER_PART_NUMBER") "39281083")
        (field (name "COPYRIGHT") "Copyright (C) 2022 Ultra Librarian. All rights reserved.")
      )
      (libsource (lib "eagle-import") (part "TEKNIC_MOTOR_8PIN"))
    )
    (comp (ref "J31")
      (value "2-pos")
      (footprint "eagle-import:2_3.81MM_PITCH")
      (fields (field (name "PARTNO") "691322310002"))
      (libsource (lib "eagle-import") (part "3.81MM_1_X_2_RT_ANGLE_PLUG_HEADER"))
    )
    (comp (ref "J33")
      (value "TEKNIC_MOTOR_8PIN")
      (footprint "eagle-import:CON_39281083")
      (fields
        (field (name "MANUFACTURER_PART_NUMBER") "39281083")
        (field (name "COPYRIGHT") "Copyright (C) 2022 Ultra Librarian. All rights reserved.")
      )
      (libsource (lib "eagle-import") (part "TEKNIC_MOTOR_8PIN"))
    )
    (comp (ref "J34")
      (value "TEKNIC_MOTOR_8PIN")
      (footprint "eagle-import:CON_39281083")
      (fields
        (field (name "MANUFACTURER_PART_NUMBER") "39281083")
        (field (name "COPYRIGHT") "Copyright (C) 2022 Ultra Librarian. All rights reserved.")
      )
      (libsource (lib "eagle-import") (part "TEKNIC_MOTOR_8PIN"))
    )
    (comp (ref "J39")
      (value "2_X_10_HEADER_GENERIC")
      (footprint "eagle-import:2_X_10_.1_INCH")
      (fields (field (name "PARTNO") "67996-420HLF"))
      (libsource (lib "eagle-import") (part "2_X_10_HEADER_GENERIC"))
    )
    (comp (ref "L1")
      (value "2.2uH")
      (footprint "eagle-import:1008")
      (fields (field (name "PARTNO") "LQM2HPN2R2MG0L"))
      (libsource (lib "eagle-import") (part "INDUCTOR_1008_2.2_MH_1.3A"))
    )
    (comp (ref "LED1")
      (value "Green")
      (footprint "eagle-import:0805")
      (fields (field (name "PARTNO") "LG R971-KN-1"))
      (libsource (lib "eagle-import") (part "LED_0805_GREEN"))
    )
    (comp (ref "LED3")
      (value "Green")
      (footprint "eagle-import:0805")
      (fields (field (name "PARTNO") "LG R971-KN-1"))
      (libsource (lib "eagle-import") (part "LED_0805_GREEN"))
    )
    (comp (ref "LED4")
      (value "Green")
      (footprint "eagle-import:0805")
      (fields (field (name "PARTNO") "LG R971-KN-1"))
      (libsource (lib "eagle-import") (part "LED_0805_GREEN"))
    )
    (comp (ref "LED5")
      (value "Green")
      (footprint "eagle-import:0805")
      (fields (field (name "PARTNO") "LG R971-KN-1"))
      (libsource (lib "eagle-import") (part "LED_0805_GREEN"))
    )
    (comp (ref "LED6")
      (value "Green")
      (footprint "eagle-import:0805")
      (fields (field (name "PARTNO") "LG R971-KN-1"))
      (libsource (lib "eagle-import") (part "LED_0805_GREEN"))
    )
    (comp (ref "LED7")
      (value "Green")
      (footprint "eagle-import:0805")
      (fields (field (name "PARTNO") "LG R971-KN-1"))
      (libsource (lib "eagle-import") (part "LED_0805_GREEN"))
    )
    (comp (ref "LED8")
      (value "Green")
      (footprint "eagle-import:0805")
      (fields (field (name "PARTNO") "LG R971-KN-1"))
      (libsource (lib "eagle-import") (part "LED_0805_GREEN"))
    )
    (comp (ref "LED9")
      (value "Green")
      (footprint "eagle-import:0805")
      (fields (field (name "PARTNO") "LG R971-KN-1"))
      (libsource (lib "eagle-import") (part "LED_0805_GREEN"))
    )
    (comp (ref "LED10")
      (value "Green")
      (footprint "eagle-import:0805")
      (fields (field (name "PARTNO") "LG R971-KN-1"))
      (libsource (lib "eagle-import") (part "LED_0805_GREEN"))
    )
    (comp (ref "LED11")
      (value "Green")
      (footprint "eagle-import:0805")
      (fields (field (name "PARTNO") "LG R971-KN-1"))
      (libsource (lib "eagle-import") (part "LED_0805_GREEN"))
    )
    (comp (ref "LED12")
      (value "Green")
      (footprint "eagle-import:0805")
      (fields (field (name "PARTNO") "LG R971-KN-1"))
      (libsource (lib "eagle-import") (part "LED_0805_GREEN"))
    )
    (comp (ref "LED13")
      (value "Green")
      (footprint "eagle-import:0805")
      (fields (field (name "PARTNO") "LG R971-KN-1"))
      (libsource (lib "eagle-import") (part "LED_0805_GREEN"))
    )
    (comp (ref "LED14")
      (value "Green")
      (footprint "eagle-import:0805")
      (fields (field (name "PARTNO") "LG R971-KN-1"))
      (libsource (lib "eagle-import") (part "LED_0805_GREEN"))
    )
    (comp (ref "LED15")
      (value "Green")
      (footprint "eagle-import:0805")
      (fields (field (name "PARTNO") "LG R971-KN-1"))
      (libsource (lib "eagle-import") (part "LED_0805_GREEN"))
    )
    (comp (ref "LED16")
      (value "Green")
      (footprint "eagle-import:0805")
      (fields (field (name "PARTNO") "LG R971-KN-1"))
      (libsource (lib "eagle-import") (part "LED_0805_GREEN"))
    )
    (comp (ref "P1")
      (value "1_X_1_1MM_PIN")
      (footprint "eagle-import:1_X_1_1MM_PIN")
      (libsource (lib "eagle-import") (part "1_X_1_1MM_PIN"))
    )
    (comp (ref "P2")
      (value "1_X_1_1MM_PIN")
      (footprint "eagle-import:1_X_1_1MM_PIN")
      (libsource (lib "eagle-import") (part "1_X_1_1MM_PIN"))
    )
    (comp (ref "P3")
      (value "1_X_1_1MM_PIN")
      (footprint "eagle-import:1_X_1_1MM_PIN")
      (libsource (lib "eagle-import") (part "1_X_1_1MM_PIN"))
    )
    (comp (ref "P4")
      (value "1_X_1_1MM_PIN")
      (footprint "eagle-import:1_X_1_1MM_PIN")
      (libsource (lib "eagle-import") (part "1_X_1_1MM_PIN"))
    )
    (comp (ref "R1")
      (value "6K49")
      (footprint "eagle-import:0402")
      (fields (field (name "PARTNO") "RMCF0402FT6K49"))
      (libsource (lib "eagle-import") (part "R_0402_6K49"))
    )
    (comp (ref "R2")
      (value "10K0")
      (footprint "eagle-import:0402")
      (fields (field (name "PARTNO") "RMCF0402JT10K0"))
      (libsource (lib "eagle-import") (part "R_0402_10K0"))
    )
    (comp (ref "R3")
      (value "10K0")
      (footprint "eagle-import:0402")
      (fields (field (name "PARTNO") "RMCF0402JT10K0"))
      (libsource (lib "eagle-import") (part "R_0402_10K0"))
    )
    (comp (ref "R4")
      (value "1K5")
      (footprint "eagle-import:0402")
      (fields (field (name "PARTNO") "RMCF0402JT1K50"))
      (libsource (lib "eagle-import") (part "R_0402_1K5"))
    )
    (comp (ref "R5")
      (value "470R0")
      (footprint "eagle-import:0402")
      (fields (field (name "PARTNO") "RMCF0402JT470R"))
      (libsource (lib "eagle-import") (part "R_0402_470R0"))
    )
    (comp (ref "R6")
      (value "1K5")
      (footprint "eagle-import:0402")
      (fields (field (name "PARTNO") "RMCF0402JT1K50"))
      (libsource (lib "eagle-import") (part "R_0402_1K5"))
    )
    (comp (ref "R7")
      (value "470R0")
      (footprint "eagle-import:0402")
      (fields (field (name "PARTNO") "RMCF0402JT470R"))
      (libsource (lib "eagle-import") (part "R_0402_470R0"))
    )
    (comp (ref "R8")
      (value "470R0")
      (footprint "eagle-import:0402")
      (fields (field (name "PARTNO") "RMCF0402JT470R"))
      (libsource (lib "eagle-import") (part "R_0402_470R0"))
    )
    (comp (ref "R9")
      (value "33R0")
      (footprint "eagle-import:0402")
      (fields (field (name "PARTNO") "RMCF0402JT33R0"))
      (libsource (lib "eagle-import") (part "R_0402_33R0"))
    )
    (comp (ref "R10")
      (value "33R0")
      (footprint "eagle-import:0402")
      (fields (field (name "PARTNO") "RMCF0402JT33R0"))
      (libsource (lib "eagle-import") (part "R_0402_33R0"))
    )
    (comp (ref "R11")
      (value "33R0")
      (footprint "eagle-import:0402")
      (fields (field (name "PARTNO") "RMCF0402JT33R0"))
      (libsource (lib "eagle-import") (part "R_0402_33R0"))
    )
    (comp (ref "R12")
      (value "33R0")
      (footprint "eagle-import:0402")
      (fields (field (name "PARTNO") "RMCF0402JT33R0"))
      (libsource (lib "eagle-import") (part "R_0402_33R0"))
    )
    (comp (ref "R13")
      (value "10K0")
      (footprint "eagle-import:0402")
      (fields (field (name "PARTNO") "RMCF0402JT10K0"))
      (libsource (lib "eagle-import") (part "R_0402_10K0"))
    )
    (comp (ref "R14")
      (value "1K0")
      (footprint "eagle-import:0402")
      (fields (field (name "PARTNO") "CRG0402J1K0"))
      (libsource (lib "eagle-import") (part "R_0402_1K0"))
    )
    (comp (ref "R15")
      (value "1K0")
      (footprint "eagle-import:0402")
      (fields (field (name "PARTNO") "CRG0402J1K0"))
      (libsource (lib "eagle-import") (part "R_0402_1K0"))
    )
    (comp (ref "R16")
      (value "15K0")
      (footprint "eagle-import:0402")
      (fields (field (name "PARTNO") "RMCF0402JT15K0"))
      (libsource (lib "eagle-import") (part "R_0402_15K0"))
    )
    (comp (ref "R17")
      (value "27R0")
      (footprint "eagle-import:0402")
      (fields (field (name "PARTNO") "RMCF0402JT27R0"))
      (libsource (lib "eagle-import") (part "R_0402_27R0"))
    )
    (comp (ref "R18")
      (value "27R0")
      (footprint "eagle-import:0402")
      (fields (field (name "PARTNO") "RMCF0402JT27R0"))
      (libsource (lib "eagle-import") (part "R_0402_27R0"))
    )
    (comp (ref "R19")
      (value "10K0")
      (footprint "eagle-import:0402")
      (fields (field (name "PARTNO") "RMCF0402JT10K0"))
      (libsource (lib "eagle-import") (part "R_0402_10K0"))
    )
    (comp (ref "R20")
      (value "10K0")
      (footprint "eagle-import:0402")
      (fields (field (name "PARTNO") "RMCF0402JT10K0"))
      (libsource (lib "eagle-import") (part "R_0402_10K0"))
    )
    (comp (ref "R21")
      (value "30K0")
      (footprint "eagle-import:0402")
      (fields (field (name "PARTNO") "RC0402JR-0730KL"))
      (libsource (lib "eagle-import") (part "R_0402_30K0"))
    )
    (comp (ref "R22")
      (value "2K2")
      (footprint "eagle-import:0402")
      (fields (field (name "PARTNO") "RMCF0402JT2K20"))
      (libsource (lib "eagle-import") (part "R_0402_2K2"))
    )
    (comp (ref "R23")
      (value "10K0")
      (footprint "eagle-import:0402")
      (fields (field (name "PARTNO") "RMCF0402JT10K0"))
      (libsource (lib "eagle-import") (part "R_0402_10K0"))
    )
    (comp (ref "R24")
      (value "10K0")
      (footprint "eagle-import:0402")
      (fields (field (name "PARTNO") "RMCF0402JT10K0"))
      (libsource (lib "eagle-import") (part "R_0402_10K0"))
    )
    (comp (ref "R25")
      (value "100K")
      (footprint "eagle-import:0402")
      (libsource (lib "eagle-import") (part "R_0402"))
    )
    (comp (ref "R26")
      (value "100K")
      (footprint "eagle-import:0402")
      (libsource (lib "eagle-import") (part "R_0402"))
    )
    (comp (ref "R27")
      (value "100K")
      (footprint "eagle-import:0402")
      (libsource (lib "eagle-import") (part "R_0402"))
    )
    (comp (ref "R28")
      (value "2.2K")
      (footprint "eagle-import:0402")
      (libsource (lib "eagle-import") (part "R_0402"))
    )
    (comp (ref "R29")
      (value "500R0")
      (footprint "eagle-import:0402")
      (libsource (lib "eagle-import") (part "R_0402"))
    )
    (comp (ref "R30")
      (value "500R0")
      (footprint "eagle-import:0402")
      (libsource (lib "eagle-import") (part "R_0402"))
    )
    (comp (ref "R31")
      (value "470R0")
      (footprint "eagle-import:0402")
      (fields (field (name "PARTNO") "RMCF0402JT470R"))
      (libsource (lib "eagle-import") (part "R_0402_470R0"))
    )
    (comp (ref "R32")
      (value "470R0")
      (footprint "eagle-import:0402")
      (fields (field (name "PARTNO") "RMCF0402JT470R"))
      (libsource (lib "eagle-import") (part "R_0402_470R0"))
    )
    (comp (ref "R33")
      (value "470R0")
      (footprint "eagle-import:0402")
      (fields (field (name "PARTNO") "RMCF0402JT470R"))
      (libsource (lib "eagle-import") (part "R_0402_470R0"))
    )
    (comp (ref "R34")
      (value "10K0")
      (footprint "eagle-import:0402")
      (fields (field (name "PARTNO") "RMCF0402JT10K0"))
      (libsource (lib "eagle-import") (part "R_0402_10K0"))
    )
    (comp (ref "R35")
      (value "2.2K")
      (footprint "eagle-import:0402")
      (libsource (lib "eagle-import") (part "R_0402"))
    )
    (comp (ref "R36")
      (value "470R0")
      (footprint "eagle-import:0402")
      (fields (field (name "PARTNO") "RMCF0402JT470R"))
      (libsource (lib "eagle-import") (part "R_0402_470R0"))
    )
    (comp (ref "R37")
      (value "1k")
      (footprint "eagle-import:0805")
      (libsource (lib "eagle-import") (part "R_0805"))
    )
    (comp (ref "R38")
      (value "33")
      (footprint "eagle-import:0805")
      (libsource (lib "eagle-import") (part "R_0805"))
    )
    (comp (ref "R39")
      (value "33")
      (footprint "eagle-import:0805")
      (libsource (lib "eagle-import") (part "R_0805"))
    )
    (comp (ref "R40")
      (value "33")
      (footprint "eagle-import:0805")
      (libsource (lib "eagle-import") (part "R_0805"))
    )
    (comp (ref "R41")
      (value "1k")
      (footprint "eagle-import:0805")
      (libsource (lib "eagle-import") (part "R_0805"))
    )
    (comp (ref "R42")
      (value "1k")
      (footprint "eagle-import:0805")
      (libsource (lib "eagle-import") (part "R_0805"))
    )
    (comp (ref "R43")
      (value "1k")
      (footprint "eagle-import:0805")
      (libsource (lib "eagle-import") (part "R_0805"))
    )
    (comp (ref "R44")
      (value "33")
      (footprint "eagle-import:0805")
      (libsource (lib "eagle-import") (part "R_0805"))
    )
    (comp (ref "R45")
      (value "33")
      (footprint "eagle-import:0805")
      (libsource (lib "eagle-import") (part "R_0805"))
    )
    (comp (ref "R46")
      (value "33")
      (footprint "eagle-import:0805")
      (libsource (lib "eagle-import") (part "R_0805"))
    )
    (comp (ref "R47")
      (value "1k")
      (footprint "eagle-import:0805")
      (libsource (lib "eagle-import") (part "R_0805"))
    )
    (comp (ref "R48")
      (value "1k")
      (footprint "eagle-import:0805")
      (libsource (lib "eagle-import") (part "R_0805"))
    )
    (comp (ref "R49")
      (value "500R0")
      (footprint "eagle-import:0402")
      (libsource (lib "eagle-import") (part "R_0402"))
    )
    (comp (ref "R50")
      (value "500R0")
      (footprint "eagle-import:0402")
      (libsource (lib "eagle-import") (part "R_0402"))
    )
    (comp (ref "R51")
      (value "470R0")
      (footprint "eagle-import:0402")
      (fields (field (name "PARTNO") "RMCF0402JT470R"))
      (libsource (lib "eagle-import") (part "R_0402_470R0"))
    )
    (comp (ref "R52")
      (value "470R0")
      (footprint "eagle-import:0402")
      (fields (field (name "PARTNO") "RMCF0402JT470R"))
      (libsource (lib "eagle-import") (part "R_0402_470R0"))
    )
    (comp (ref "R53")
      (value "10K0")
      (footprint "eagle-import:0402")
      (fields (field (name "PARTNO") "RMCF0402JT10K0"))
      (libsource (lib "eagle-import") (part "R_0402_10K0"))
    )
    (comp (ref "R54")
      (value "2.2K")
      (footprint "eagle-import:0402")
      (libsource (lib "eagle-import") (part "R_0402"))
    )
    (comp (ref "R55")
      (value "470R0")
      (footprint "eagle-import:0402")
      (fields (field (name "PARTNO") "RMCF0402JT470R"))
      (libsource (lib "eagle-import") (part "R_0402_470R0"))
    )
    (comp (ref "R56")
      (value "10K0")
      (footprint "eagle-import:0402")
      (fields (field (name "PARTNO") "RMCF0402JT10K0"))
      (libsource (lib "eagle-import") (part "R_0402_10K0"))
    )
    (comp (ref "R57")
      (value "2.2K")
      (footprint "eagle-import:0402")
      (libsource (lib "eagle-import") (part "R_0402"))
    )
    (comp (ref "R58")
      (value "470R0")
      (footprint "eagle-import:0402")
      (fields (field (name "PARTNO") "RMCF0402JT470R"))
      (libsource (lib "eagle-import") (part "R_0402_470R0"))
    )
    (comp (ref "R59")
      (value "10K0")
      (footprint "eagle-import:0402")
      (fields (field (name "PARTNO") "RMCF0402JT10K0"))
      (libsource (lib "eagle-import") (part "R_0402_10K0"))
    )
    (comp (ref "R60")
      (value "2.2K")
      (footprint "eagle-import:0402")
      (libsource (lib "eagle-import") (part "R_0402"))
    )
    (comp (ref "R61")
      (value "1k")
      (footprint "eagle-import:0805")
      (libsource (lib "eagle-import") (part "R_0805"))
    )
    (comp (ref "R62")
      (value "33")
      (footprint "eagle-import:0805")
      (libsource (lib "eagle-import") (part "R_0805"))
    )
    (comp (ref "R63")
      (value "33")
      (footprint "eagle-import:0805")
      (libsource (lib "eagle-import") (part "R_0805"))
    )
    (comp (ref "R64")
      (value "33")
      (footprint "eagle-import:0805")
      (libsource (lib "eagle-import") (part "R_0805"))
    )
    (comp (ref "R65")
      (value "1k")
      (footprint "eagle-import:0805")
      (libsource (lib "eagle-import") (part "R_0805"))
    )
    (comp (ref "R66")
      (value "1k")
      (footprint "eagle-import:0805")
      (libsource (lib "eagle-import") (part "R_0805"))
    )
    (comp (ref "R67")
      (value "1k")
      (footprint "eagle-import:0805")
      (libsource (lib "eagle-import") (part "R_0805"))
    )
    (comp (ref "R68")
      (value "33")
      (footprint "eagle-import:0805")
      (libsource (lib "eagle-import") (part "R_0805"))
    )
    (comp (ref "R69")
      (value "33")
      (footprint "eagle-import:0805")
      (libsource (lib "eagle-import") (part "R_0805"))
    )
    (comp (ref "R70")
      (value "33")
      (footprint "eagle-import:0805")
      (libsource (lib "eagle-import") (part "R_0805"))
    )
    (comp (ref "R71")
      (value "1k")
      (footprint "eagle-import:0805")
      (libsource (lib "eagle-import") (part "R_0805"))
    )
    (comp (ref "R72")
      (value "1k")
      (footprint "eagle-import:0805")
      (libsource (lib "eagle-import") (part "R_0805"))
    )
    (comp (ref "R73")
      (value "470R0")
      (footprint "eagle-import:0402")
      (fields (field (name "PARTNO") "RMCF0402JT470R"))
      (libsource (lib "eagle-import") (part "R_0402_470R0"))
    )
    (comp (ref "R74")
      (value "10K0")
      (footprint "eagle-import:0402")
      (fields (field (name "PARTNO") "RMCF0402JT10K0"))
      (libsource (lib "eagle-import") (part "R_0402_10K0"))
    )
    (comp (ref "R75")
      (value "2.2K")
      (footprint "eagle-import:0402")
      (libsource (lib "eagle-import") (part "R_0402"))
    )
    (comp (ref "R76")
      (value "470R0")
      (footprint "eagle-import:0402")
      (fields (field (name "PARTNO") "RMCF0402JT470R"))
      (libsource (lib "eagle-import") (part "R_0402_470R0"))
    )
    (comp (ref "R77")
      (value "10K0")
      (footprint "eagle-import:0402")
      (fields (field (name "PARTNO") "RMCF0402JT10K0"))
      (libsource (lib "eagle-import") (part "R_0402_10K0"))
    )
    (comp (ref "R78")
      (value "2.2K")
      (footprint "eagle-import:0402")
      (libsource (lib "eagle-import") (part "R_0402"))
    )
    (comp (ref "R79")
      (value "470R0")
      (footprint "eagle-import:0402")
      (fields (field (name "PARTNO") "RMCF0402JT470R"))
      (libsource (lib "eagle-import") (part "R_0402_470R0"))
    )
    (comp (ref "R80")
      (value "10K0")
      (footprint "eagle-import:0402")
      (fields (field (name "PARTNO") "RMCF0402JT10K0"))
      (libsource (lib "eagle-import") (part "R_0402_10K0"))
    )
    (comp (ref "R81")
      (value "2.2K")
      (footprint "eagle-import:0402")
      (libsource (lib "eagle-import") (part "R_0402"))
    )
    (comp (ref "R82")
      (value "470R0")
      (footprint "eagle-import:0402")
      (fields (field (name "PARTNO") "RMCF0402JT470R"))
      (libsource (lib "eagle-import") (part "R_0402_470R0"))
    )
    (comp (ref "R83")
      (value "10K0")
      (footprint "eagle-import:0402")
      (fields (field (name "PARTNO") "RMCF0402JT10K0"))
      (libsource (lib "eagle-import") (part "R_0402_10K0"))
    )
    (comp (ref "R84")
      (value "2.2K")
      (footprint "eagle-import:0402")
      (libsource (lib "eagle-import") (part "R_0402"))
    )
    (comp (ref "R85")
      (value "1k")
      (footprint "eagle-import:0805")
      (libsource (lib "eagle-import") (part "R_0805"))
    )
    (comp (ref "R86")
      (value "33")
      (footprint "eagle-import:0805")
      (libsource (lib "eagle-import") (part "R_0805"))
    )
    (comp (ref "R87")
      (value "33")
      (footprint "eagle-import:0805")
      (libsource (lib "eagle-import") (part "R_0805"))
    )
    (comp (ref "R88")
      (value "33")
      (footprint "eagle-import:0805")
      (libsource (lib "eagle-import") (part "R_0805"))
    )
    (comp (ref "R89")
      (value "1k")
      (footprint "eagle-import:0805")
      (libsource (lib "eagle-import") (part "R_0805"))
    )
    (comp (ref "R90")
      (value "1k")
      (footprint "eagle-import:0805")
      (libsource (lib "eagle-import") (part "R_0805"))
    )
    (comp (ref "R91")
      (value "1k")
      (footprint "eagle-import:0805")
      (libsource (lib "eagle-import") (part "R_0805"))
    )
    (comp (ref "R92")
      (value "33")
      (footprint "eagle-import:0805")
      (libsource (lib "eagle-import") (part "R_0805"))
    )
    (comp (ref "R93")
      (value "33")
      (footprint "eagle-import:0805")
      (libsource (lib "eagle-import") (part "R_0805"))
    )
    (comp (ref "R94")
      (value "33")
      (footprint "eagle-import:0805")
      (libsource (lib "eagle-import") (part "R_0805"))
    )
    (comp (ref "R95")
      (value "1k")
      (footprint "eagle-import:0805")
      (libsource (lib "eagle-import") (part "R_0805"))
    )
    (comp (ref "R96")
      (value "1k")
      (footprint "eagle-import:0805")
      (libsource (lib "eagle-import") (part "R_0805"))
    )
    (comp (ref "R97")
      (value "470R0")
      (footprint "eagle-import:0402")
      (fields (field (name "PARTNO") "RMCF0402JT470R"))
      (libsource (lib "eagle-import") (part "R_0402_470R0"))
    )
    (comp (ref "R98")
      (value "10K0")
      (footprint "eagle-import:0402")
      (fields (field (name "PARTNO") "RMCF0402JT10K0"))
      (libsource (lib "eagle-import") (part "R_0402_10K0"))
    )
    (comp (ref "R99")
      (value "2.2K")
      (footprint "eagle-import:0402")
      (libsource (lib "eagle-import") (part "R_0402"))
    )
    (comp (ref "R100")
      (value "470R0")
      (footprint "eagle-import:0402")
      (fields (field (name "PARTNO") "RMCF0402JT470R"))
      (libsource (lib "eagle-import") (part "R_0402_470R0"))
    )
    (comp (ref "R101")
      (value "10K0")
      (footprint "eagle-import:0402")
      (fields (field (name "PARTNO") "RMCF0402JT10K0"))
      (libsource (lib "eagle-import") (part "R_0402_10K0"))
    )
    (comp (ref "R102")
      (value "100K")
      (footprint "eagle-import:0402")
      (libsource (lib "eagle-import") (part "R_0402"))
    )
    (comp (ref "R103")
      (value "100K")
      (footprint "eagle-import:0402")
      (libsource (lib "eagle-import") (part "R_0402"))
    )
    (comp (ref "R104")
      (value "100K")
      (footprint "eagle-import:0402")
      (libsource (lib "eagle-import") (part "R_0402"))
    )
    (comp (ref "R105")
      (value "100K")
      (footprint "eagle-import:0402")
      (libsource (lib "eagle-import") (part "R_0402"))
    )
    (comp (ref "R106")
      (value "100K")
      (footprint "eagle-import:0402")
      (libsource (lib "eagle-import") (part "R_0402"))
    )
    (comp (ref "R107")
      (value "100K")
      (footprint "eagle-import:0402")
      (libsource (lib "eagle-import") (part "R_0402"))
    )
    (comp (ref "R108")
      (value "100K")
      (footprint "eagle-import:0402")
      (libsource (lib "eagle-import") (part "R_0402"))
    )
    (comp (ref "R109")
      (value "1k")
      (footprint "eagle-import:0805")
      (libsource (lib "eagle-import") (part "R_0805"))
    )
    (comp (ref "R110")
      (value "33")
      (footprint "eagle-import:0805")
      (libsource (lib "eagle-import") (part "R_0805"))
    )
    (comp (ref "R111")
      (value "33")
      (footprint "eagle-import:0805")
      (libsource (lib "eagle-import") (part "R_0805"))
    )
    (comp (ref "R112")
      (value "33")
      (footprint "eagle-import:0805")
      (libsource (lib "eagle-import") (part "R_0805"))
    )
    (comp (ref "R113")
      (value "1k")
      (footprint "eagle-import:0805")
      (libsource (lib "eagle-import") (part "R_0805"))
    )
    (comp (ref "R114")
      (value "1k")
      (footprint "eagle-import:0805")
      (libsource (lib "eagle-import") (part "R_0805"))
    )
    (comp (ref "R115")
      (value "1k")
      (footprint "eagle-import:0805")
      (libsource (lib "eagle-import") (part "R_0805"))
    )
    (comp (ref "R116")
      (value "33")
      (footprint "eagle-import:0805")
      (libsource (lib "eagle-import") (part "R_0805"))
    )
    (comp (ref "R117")
      (value "33")
      (footprint "eagle-import:0805")
      (libsource (lib "eagle-import") (part "R_0805"))
    )
    (comp (ref "R118")
      (value "33")
      (footprint "eagle-import:0805")
      (libsource (lib "eagle-import") (part "R_0805"))
    )
    (comp (ref "R119")
      (value "1k")
      (footprint "eagle-import:0805")
      (libsource (lib "eagle-import") (part "R_0805"))
    )
    (comp (ref "R120")
      (value "1k")
      (footprint "eagle-import:0805")
      (libsource (lib "eagle-import") (part "R_0805"))
    )
    (comp (ref "R133")
      (value "1k")
      (footprint "eagle-import:0805")
      (libsource (lib "eagle-import") (part "R_0805"))
    )
    (comp (ref "R134")
      (value "33")
      (footprint "eagle-import:0805")
      (libsource (lib "eagle-import") (part "R_0805"))
    )
    (comp (ref "R135")
      (value "33")
      (footprint "eagle-import:0805")
      (libsource (lib "eagle-import") (part "R_0805"))
    )
    (comp (ref "R136")
      (value "33")
      (footprint "eagle-import:0805")
      (libsource (lib "eagle-import") (part "R_0805"))
    )
    (comp (ref "R137")
      (value "1k")
      (footprint "eagle-import:0805")
      (libsource (lib "eagle-import") (part "R_0805"))
    )
    (comp (ref "R138")
      (value "1k")
      (footprint "eagle-import:0805")
      (libsource (lib "eagle-import") (part "R_0805"))
    )
    (comp (ref "R139")
      (value "1k")
      (footprint "eagle-import:0805")
      (libsource (lib "eagle-import") (part "R_0805"))
    )
    (comp (ref "R140")
      (value "33")
      (footprint "eagle-import:0805")
      (libsource (lib "eagle-import") (part "R_0805"))
    )
    (comp (ref "R141")
      (value "33")
      (footprint "eagle-import:0805")
      (libsource (lib "eagle-import") (part "R_0805"))
    )
    (comp (ref "R142")
      (value "33")
      (footprint "eagle-import:0805")
      (libsource (lib "eagle-import") (part "R_0805"))
    )
    (comp (ref "R143")
      (value "1k")
      (footprint "eagle-import:0805")
      (libsource (lib "eagle-import") (part "R_0805"))
    )
    (comp (ref "R144")
      (value "1k")
      (footprint "eagle-import:0805")
      (libsource (lib "eagle-import") (part "R_0805"))
    )
    (comp (ref "R157")
      (value "1k")
      (footprint "eagle-import:0805")
      (libsource (lib "eagle-import") (part "R_0805"))
    )
    (comp (ref "R158")
      (value "33")
      (footprint "eagle-import:0805")
      (libsource (lib "eagle-import") (part "R_0805"))
    )
    (comp (ref "R159")
      (value "33")
      (footprint "eagle-import:0805")
      (libsource (lib "eagle-import") (part "R_0805"))
    )
    (comp (ref "R160")
      (value "33")
      (footprint "eagle-import:0805")
      (libsource (lib "eagle-import") (part "R_0805"))
    )
    (comp (ref "R161")
      (value "1k")
      (footprint "eagle-import:0805")
      (libsource (lib "eagle-import") (part "R_0805"))
    )
    (comp (ref "R162")
      (value "1k")
      (footprint "eagle-import:0805")
      (libsource (lib "eagle-import") (part "R_0805"))
    )
    (comp (ref "R163")
      (value "1k")
      (footprint "eagle-import:0805")
      (libsource (lib "eagle-import") (part "R_0805"))
    )
    (comp (ref "R164")
      (value "33")
      (footprint "eagle-import:0805")
      (libsource (lib "eagle-import") (part "R_0805"))
    )
    (comp (ref "R165")
      (value "33")
      (footprint "eagle-import:0805")
      (libsource (lib "eagle-import") (part "R_0805"))
    )
    (comp (ref "R166")
      (value "33")
      (footprint "eagle-import:0805")
      (libsource (lib "eagle-import") (part "R_0805"))
    )
    (comp (ref "R167")
      (value "1k")
      (footprint "eagle-import:0805")
      (libsource (lib "eagle-import") (part "R_0805"))
    )
    (comp (ref "R168")
      (value "1k")
      (footprint "eagle-import:0805")
      (libsource (lib "eagle-import") (part "R_0805"))
    )
    (comp (ref "RJ1")
      (value "RJ45")
      (footprint "eagle-import:RJ45_TH_ELEC")
      (fields (field (name "PARTNO") "13F-64GYD2PL2NL"))
      (libsource (lib "eagle-import") (part "RJ45_WITH_ELEC"))
    )
    (comp (ref "U$1")
      (value "RELAY_KYOTO_KF0604D")
      (footprint "eagle-import:RELAY_KYOTO_KF0604D")
      (libsource (lib "eagle-import") (part "RELAY_KYOTO_KF0604D"))
    )
    (comp (ref "U$2")
      (value "RELAY_KYOTO_KF0604D")
      (footprint "eagle-import:RELAY_KYOTO_KF0604D")
      (libsource (lib "eagle-import") (part "RELAY_KYOTO_KF0604D"))
    )
    (comp (ref "U$7")
      (value "RELAY_KYOTO_KF0604D")
      (footprint "eagle-import:RELAY_KYOTO_KF0604D")
      (libsource (lib "eagle-import") (part "RELAY_KYOTO_KF0604D"))
    )
    (comp (ref "U$8")
      (value "RELAY_KYOTO_KF0604D")
      (footprint "eagle-import:RELAY_KYOTO_KF0604D")
      (libsource (lib "eagle-import") (part "RELAY_KYOTO_KF0604D"))
    )
    (comp (ref "U1")
      (value "KSZ8081_QFN_24")
      (footprint "eagle-import:QFN-24-M")
      (fields (field (name "PARTNO") "KSZ8081RNACA"))
      (libsource (lib "eagle-import") (part "KSZ8081RNACAQFN-24-M"))
    )
    (comp (ref "U2")
      (value "AP2151DWG-7")
      (footprint "eagle-import:SOT-23-5")
      (fields (field (name "PARTNO") "AP2151WG-7"))
      (libsource (lib "eagle-import") (part "AP2151DWG-7"))
    )
    (comp (ref "U3")
      (value "S7G2LQFP176")
      (footprint "eagle-import:LQFP176_24X24")
      (fields (field (name "PARTNO") "R7FS7G27H3A01CFC#AA0"))
      (libsource (lib "eagle-import") (part "RENESAS_S7G2_X_176"))
    )
    (comp (ref "U5")
      (value "NPN")
      (footprint "eagle-import:SOT323")
      (fields (field (name "PARTNO") "BC846BW_NPN"))
      (libsource (lib "eagle-import") (part "BC846BW"))
    )
    (comp (ref "U6")
      (value "NPN")
      (footprint "eagle-import:SOT323")
      (fields (field (name "PARTNO") "BC846BW_NPN"))
      (libsource (lib "eagle-import") (part "BC846BW"))
    )
    (comp (ref "U7")
      (value "NPN")
      (footprint "eagle-import:SOT323")
      (fields (field (name "PARTNO") "BC846BW_NPN"))
      (libsource (lib "eagle-import") (part "BC846BW"))
    )
    (comp (ref "U8")
      (value "NPN")
      (footprint "eagle-import:SOT323")
      (fields (field (name "PARTNO") "BC846BW_NPN"))
      (libsource (lib "eagle-import") (part "BC846BW"))
    )
    (comp (ref "U9")
      (value "NPN")
      (footprint "eagle-import:SOT323")
      (fields (field (name "PARTNO") "BC846BW_NPN"))
      (libsource (lib "eagle-import") (part "BC846BW"))
    )
    (comp (ref "U10")
      (value "NPN")
      (footprint "eagle-import:SOT323")
      (fields (field (name "PARTNO") "BC846BW_NPN"))
      (libsource (lib "eagle-import") (part "BC846BW"))
    )
    (comp (ref "U11")
      (value "NPN")
      (footprint "eagle-import:SOT323")
      (fields (field (name "PARTNO") "BC846BW_NPN"))
      (libsource (lib "eagle-import") (part "BC846BW"))
    )
    (comp (ref "U12")
      (value "NPN")
      (footprint "eagle-import:SOT323")
      (fields (field (name "PARTNO") "BC846BW_NPN"))
      (libsource (lib "eagle-import") (part "BC846BW"))
    )
    (comp (ref "U13")
      (value "NPN")
      (footprint "eagle-import:SOT323")
      (fields (field (name "PARTNO") "BC846BW_NPN"))
      (libsource (lib "eagle-import") (part "BC846BW"))
    )
    (comp (ref "U14")
      (value "NPN")
      (footprint "eagle-import:SOT323")
      (fields (field (name "PARTNO") "BC846BW_NPN"))
      (libsource (lib "eagle-import") (part "BC846BW"))
    )
    (comp (ref "U15")
      (value "NPN")
      (footprint "eagle-import:SOT323")
      (fields (field (name "PARTNO") "BC846BW_NPN"))
      (libsource (lib "eagle-import") (part "BC846BW"))
    )
    (comp (ref "U16")
      (value "NPN")
      (footprint "eagle-import:SOT323")
      (fields (field (name "PARTNO") "BC846BW_NPN"))
      (libsource (lib "eagle-import") (part "BC846BW"))
    )
    (comp (ref "U17")
      (value "NPN")
      (footprint "eagle-import:SOT323")
      (fields (field (name "PARTNO") "BC846BW_NPN"))
      (libsource (lib "eagle-import") (part "BC846BW"))
    )
    (comp (ref "U18")
      (value "NPN")
      (footprint "eagle-import:SOT323")
      (fields (field (name "PARTNO") "BC846BW_NPN"))
      (libsource (lib "eagle-import") (part "BC846BW"))
    )
    (comp (ref "U19")
      (value "NPN")
      (footprint "eagle-import:SOT323")
      (fields (field (name "PARTNO") "BC846BW_NPN"))
      (libsource (lib "eagle-import") (part "BC846BW"))
    )
    (comp (ref "U20")
      (value "NPN")
      (footprint "eagle-import:SOT323")
      (fields (field (name "PARTNO") "BC846BW_NPN"))
      (libsource (lib "eagle-import") (part "BC846BW"))
    )
    (comp (ref "U21")
      (value "NPN")
      (footprint "eagle-import:SOT323")
      (fields (field (name "PARTNO") "BC846BW_NPN"))
      (libsource (lib "eagle-import") (part "BC846BW"))
    )
    (comp (ref "U22")
      (value "NPN")
      (footprint "eagle-import:SOT323")
      (fields (field (name "PARTNO") "BC846BW_NPN"))
      (libsource (lib "eagle-import") (part "BC846BW"))
    )
    (comp (ref "U23")
      (value "NPN")
      (footprint "eagle-import:SOT323")
      (fields (field (name "PARTNO") "BC846BW_NPN"))
      (libsource (lib "eagle-import") (part "BC846BW"))
    )
    (comp (ref "U24")
      (value "NPN")
      (footprint "eagle-import:SOT323")
      (fields (field (name "PARTNO") "BC846BW_NPN"))
      (libsource (lib "eagle-import") (part "BC846BW"))
    )
    (comp (ref "U25")
      (value "NPN")
      (footprint "eagle-import:SOT323")
      (fields (field (name "PARTNO") "BC846BW_NPN"))
      (libsource (lib "eagle-import") (part "BC846BW"))
    )
    (comp (ref "U26")
      (value "NPN")
      (footprint "eagle-import:SOT323")
      (fields (field (name "PARTNO") "BC846BW_NPN"))
      (libsource (lib "eagle-import") (part "BC846BW"))
    )
    (comp (ref "U27")
      (value "NPN")
      (footprint "eagle-import:SOT323")
      (fields (field (name "PARTNO") "BC846BW_NPN"))
      (libsource (lib "eagle-import") (part "BC846BW"))
    )
    (comp (ref "U28")
      (value "NPN")
      (footprint "eagle-import:SOT323")
      (fields (field (name "PARTNO") "BC846BW_NPN"))
      (libsource (lib "eagle-import") (part "BC846BW"))
    )
    (comp (ref "U29")
      (value "NPN")
      (footprint "eagle-import:SOT323")
      (fields (field (name "PARTNO") "BC846BW_NPN"))
      (libsource (lib "eagle-import") (part "BC846BW"))
    )
    (comp (ref "U30")
      (value "NPN")
      (footprint "eagle-import:SOT323")
      (fields (field (name "PARTNO") "BC846BW_NPN"))
      (libsource (lib "eagle-import") (part "BC846BW"))
    )
    (comp (ref "U34")
      (value "NPN")
      (footprint "eagle-import:SOT323")
      (fields (field (name "PARTNO") "BC846BW_NPN"))
      (libsource (lib "eagle-import") (part "BC846BW"))
    )
    (comp (ref "U35")
      (value "NPN")
      (footprint "eagle-import:SOT323")
      (fields (field (name "PARTNO") "BC846BW_NPN"))
      (libsource (lib "eagle-import") (part "BC846BW"))
    )
    (comp (ref "U36")
      (value "NPN")
      (footprint "eagle-import:SOT323")
      (fields (field (name "PARTNO") "BC846BW_NPN"))
      (libsource (lib "eagle-import") (part "BC846BW"))
    )
    (comp (ref "U37")
      (value "NPN")
      (footprint "eagle-import:SOT323")
      (fields (field (name "PARTNO") "BC846BW_NPN"))
      (libsource (lib "eagle-import") (part "BC846BW"))
    )
    (comp (ref "U38")
      (value "NPN")
      (footprint "eagle-import:SOT323")
      (fields (field (name "PARTNO") "BC846BW_NPN"))
      (libsource (lib "eagle-import") (part "BC846BW"))
    )
    (comp (ref "U39")
      (value "NPN")
      (footprint "eagle-import:SOT323")
      (fields (field (name "PARTNO") "BC846BW_NPN"))
      (libsource (lib "eagle-import") (part "BC846BW"))
    )
    (comp (ref "U46")
      (value "NPN")
      (footprint "eagle-import:SOT323")
      (fields (field (name "PARTNO") "BC846BW_NPN"))
      (libsource (lib "eagle-import") (part "BC846BW"))
    )
    (comp (ref "U47")
      (value "NPN")
      (footprint "eagle-import:SOT323")
      (fields (field (name "PARTNO") "BC846BW_NPN"))
      (libsource (lib "eagle-import") (part "BC846BW"))
    )
    (comp (ref "U48")
      (value "NPN")
      (footprint "eagle-import:SOT323")
      (fields (field (name "PARTNO") "BC846BW_NPN"))
      (libsource (lib "eagle-import") (part "BC846BW"))
    )
    (comp (ref "U49")
      (value "NPN")
      (footprint "eagle-import:SOT323")
      (fields (field (name "PARTNO") "BC846BW_NPN"))
      (libsource (lib "eagle-import") (part "BC846BW"))
    )
    (comp (ref "U50")
      (value "NPN")
      (footprint "eagle-import:SOT323")
      (fields (field (name "PARTNO") "BC846BW_NPN"))
      (libsource (lib "eagle-import") (part "BC846BW"))
    )
    (comp (ref "U51")
      (value "NPN")
      (footprint "eagle-import:SOT323")
      (fields (field (name "PARTNO") "BC846BW_NPN"))
      (libsource (lib "eagle-import") (part "BC846BW"))
    )
    (comp (ref "U58")
      (value "NPN")
      (footprint "eagle-import:SOT323")
      (fields (field (name "PARTNO") "BC846BW_NPN"))
      (libsource (lib "eagle-import") (part "BC846BW"))
    )
    (comp (ref "U59")
      (value "NPN")
      (footprint "eagle-import:SOT323")
      (fields (field (name "PARTNO") "BC846BW_NPN"))
      (libsource (lib "eagle-import") (part "BC846BW"))
    )
    (comp (ref "U60")
      (value "NPN")
      (footprint "eagle-import:SOT323")
      (fields (field (name "PARTNO") "BC846BW_NPN"))
      (libsource (lib "eagle-import") (part "BC846BW"))
    )
    (comp (ref "U61")
      (value "NPN")
      (footprint "eagle-import:SOT323")
      (fields (field (name "PARTNO") "BC846BW_NPN"))
      (libsource (lib "eagle-import") (part "BC846BW"))
    )
    (comp (ref "U62")
      (value "NPN")
      (footprint "eagle-import:SOT323")
      (fields (field (name "PARTNO") "BC846BW_NPN"))
      (libsource (lib "eagle-import") (part "BC846BW"))
    )
    (comp (ref "U63")
      (value "NPN")
      (footprint "eagle-import:SOT323")
      (fields (field (name "PARTNO") "BC846BW_NPN"))
      (libsource (lib "eagle-import") (part "BC846BW"))
    )
    (comp (ref "U70")
      (value "NPN")
      (footprint "eagle-import:SOT323")
      (fields (field (name "PARTNO") "BC846BW_NPN"))
      (libsource (lib "eagle-import") (part "BC846BW"))
    )
    (comp (ref "U71")
      (value "NPN")
      (footprint "eagle-import:SOT323")
      (fields (field (name "PARTNO") "BC846BW_NPN"))
      (libsource (lib "eagle-import") (part "BC846BW"))
    )
    (comp (ref "U72")
      (value "NPN")
      (footprint "eagle-import:SOT323")
      (fields (field (name "PARTNO") "BC846BW_NPN"))
      (libsource (lib "eagle-import") (part "BC846BW"))
    )
    (comp (ref "U73")
      (value "NPN")
      (footprint "eagle-import:SOT323")
      (fields (field (name "PARTNO") "BC846BW_NPN"))
      (libsource (lib "eagle-import") (part "BC846BW"))
    )
    (comp (ref "U74")
      (value "NPN")
      (footprint "eagle-import:SOT323")
      (fields (field (name "PARTNO") "BC846BW_NPN"))
      (libsource (lib "eagle-import") (part "BC846BW"))
    )
    (comp (ref "U75")
      (value "NPN")
      (footprint "eagle-import:SOT323")
      (fields (field (name "PARTNO") "BC846BW_NPN"))
      (libsource (lib "eagle-import") (part "BC846BW"))
    )
    (comp (ref "X1")
      (value "25MHz")
      (footprint "eagle-import:SMD_3225")
      (fields (field (name "PARTNO") "FA-238 25.0000MB-B3"))
      (libsource (lib "eagle-import") (part "XTAL_25_MHZ"))
    )
    (comp (ref "X2")
      (value "24MHz")
      (footprint "eagle-import:SMD_3225")
      (fields (field (name "PARTNO") "FA-238 24.0000MB-C3 "))
      (libsource (lib "eagle-import") (part "XTAL_24_MHZ"))
    )
    (comp (ref "X3")
      (value "32.768KHz")
      (footprint "eagle-import:SMD_X_2_PADS")
      (fields (field (name "PARTNO") "ABS07-32.768KHZ-T"))
      (libsource (lib "eagle-import") (part "XTAL_32.768KHZ"))
    )
  )
  (nets
    (net (code "1") (name "A_A_DIR") (class "Default")
      (node (ref "R111") (pin "1") (pinfunction "1_1") (pintype "passive"))
      (node (ref "U3") (pin "73") (pinfunction "P9_5_73") (pintype "bidirectional"))
    )
    (net (code "2") (name "A_A_ENABLE") (class "Default")
      (node (ref "R112") (pin "1") (pinfunction "1_1") (pintype "passive"))
      (node (ref "U3") (pin "72") (pinfunction "P9_6_72") (pintype "bidirectional"))
    )
    (net (code "3") (name "A_A_HLFB_OUT") (class "Default")
      (node (ref "J25") (pin "5") (pinfunction "5-HLFB-_5") (pintype "passive"))
    )
    (net (code "4") (name "A_A_MI_DIR") (class "Default")
      (node (ref "J25") (pin "7") (pinfunction "7-INPUT_A-_7") (pintype "passive"))
      (node (ref "R113") (pin "1") (pinfunction "1_1") (pintype "passive"))
      (node (ref "U47") (pin "3") (pinfunction "C(3)_3") (pintype "input"))
    )
    (net (code "5") (name "A_A_MI_ENABLE") (class "Default")
      (node (ref "J25") (pin "8") (pinfunction "8-ENABLE-_8") (pintype "passive"))
      (node (ref "R114") (pin "1") (pinfunction "1_1") (pintype "passive"))
      (node (ref "U48") (pin "3") (pinfunction "C(3)_3") (pintype "input"))
    )
    (net (code "6") (name "A_A_MI_STEP") (class "Default")
      (node (ref "J25") (pin "6") (pinfunction "6-INPUT_B-_6") (pintype "passive"))
      (node (ref "R109") (pin "1") (pinfunction "1_1") (pintype "passive"))
      (node (ref "U46") (pin "3") (pinfunction "C(3)_3") (pintype "input"))
    )
    (net (code "7") (name "A_A_STEP") (class "Default")
      (node (ref "R110") (pin "1") (pinfunction "1_1") (pintype "passive"))
      (node (ref "U3") (pin "74") (pinfunction "P3_12_74") (pintype "bidirectional"))
    )
    (net (code "8") (name "A_B_DIR") (class "Default")
      (node (ref "R117") (pin "1") (pinfunction "1_1") (pintype "passive"))
      (node (ref "U3") (pin "76") (pinfunction "P3_10_76") (pintype "bidirectional"))
    )
    (net (code "9") (name "A_B_ENABLE") (class "Default")
      (node (ref "R118") (pin "1") (pinfunction "1_1") (pintype "passive"))
      (node (ref "U3") (pin "75") (pinfunction "P3_11_75") (pintype "bidirectional"))
    )
    (net (code "10") (name "A_B_HLFB_OUT") (class "Default")
      (node (ref "J26") (pin "5") (pinfunction "5-HLFB-_5") (pintype "passive"))
    )
    (net (code "11") (name "A_B_MI_DIR") (class "Default")
      (node (ref "J26") (pin "7") (pinfunction "7-INPUT_A-_7") (pintype "passive"))
      (node (ref "R119") (pin "1") (pinfunction "1_1") (pintype "passive"))
      (node (ref "U50") (pin "3") (pinfunction "C(3)_3") (pintype "input"))
    )
    (net (code "12") (name "A_B_MI_ENABLE") (class "Default")
      (node (ref "J26") (pin "8") (pinfunction "8-ENABLE-_8") (pintype "passive"))
      (node (ref "R120") (pin "1") (pinfunction "1_1") (pintype "passive"))
      (node (ref "U51") (pin "3") (pinfunction "C(3)_3") (pintype "input"))
    )
    (net (code "13") (name "A_B_MI_STEP") (class "Default")
      (node (ref "J26") (pin "6") (pinfunction "6-INPUT_B-_6") (pintype "passive"))
      (node (ref "R115") (pin "1") (pinfunction "1_1") (pintype "passive"))
      (node (ref "U49") (pin "3") (pinfunction "C(3)_3") (pintype "input"))
    )
    (net (code "14") (name "A_B_STEP") (class "Default")
      (node (ref "R116") (pin "1") (pinfunction "1_1") (pintype "passive"))
      (node (ref "U3") (pin "77") (pinfunction "P3_9_77") (pintype "bidirectional"))
    )
    (net (code "15") (name "B_MI_DIR") (class "Default")
      (node (ref "J34") (pin "7") (pinfunction "7-INPUT_A-_7") (pintype "passive"))
      (node (ref "R167") (pin "1") (pinfunction "1_1") (pintype "passive"))
      (node (ref "U74") (pin "3") (pinfunction "C(3)_3") (pintype "input"))
    )
    (net (code "16") (name "C58") (class "Default")
      (node (ref "C12") (pin "P$1") (pinfunction "1_P$1") (pintype "passive"))
      (node (ref "RJ1") (pin "4") (pinfunction "CT1_4") (pintype "bidirectional"))
    )
    (net (code "17") (name "C60") (class "Default")
      (node (ref "C13") (pin "P$1") (pinfunction "1_P$1") (pintype "passive"))
      (node (ref "RJ1") (pin "5") (pinfunction "CT2_5") (pintype "bidirectional"))
    )
    (net (code "18") (name "CRS_DV") (class "Default")
      (node (ref "R12") (pin "P$2") (pinfunction "2_P$2") (pintype "passive"))
      (node (ref "U1") (pin "15") (pinfunction "CRS_DV/PHYAD[1:0]_15") (pintype "bidirectional"))
    )
    (net (code "19") (name "C_A_DIR") (class "Default")
      (node (ref "R135") (pin "1") (pinfunction "1_1") (pintype "passive"))
      (node (ref "U3") (pin "58") (pinfunction "P9_0_58") (pintype "bidirectional"))
    )
    (net (code "20") (name "C_A_ENABLE") (class "Default")
      (node (ref "R136") (pin "1") (pinfunction "1_1") (pintype "passive"))
      (node (ref "U3") (pin "57") (pinfunction "P3_15_57") (pintype "bidirectional"))
    )
    (net (code "21") (name "C_A_HLFB_OUT") (class "Default")
      (node (ref "J29") (pin "5") (pinfunction "5-HLFB-_5") (pintype "passive"))
    )
    (net (code "22") (name "C_A_MI_DIR") (class "Default")
      (node (ref "J29") (pin "7") (pinfunction "7-INPUT_A-_7") (pintype "passive"))
      (node (ref "R137") (pin "1") (pinfunction "1_1") (pintype "passive"))
      (node (ref "U59") (pin "3") (pinfunction "C(3)_3") (pintype "input"))
    )
    (net (code "23") (name "C_A_MI_ENABLE") (class "Default")
      (node (ref "J29") (pin "8") (pinfunction "8-ENABLE-_8") (pintype "passive"))
      (node (ref "R138") (pin "1") (pinfunction "1_1") (pintype "passive"))
      (node (ref "U60") (pin "3") (pinfunction "C(3)_3") (pintype "input"))
    )
    (net (code "24") (name "C_A_MI_STEP") (class "Default")
      (node (ref "J29") (pin "6") (pinfunction "6-INPUT_B-_6") (pintype "passive"))
      (node (ref "R133") (pin "1") (pinfunction "1_1") (pintype "passive"))
      (node (ref "U58") (pin "3") (pinfunction "C(3)_3") (pintype "input"))
    )
    (net (code "25") (name "C_A_STEP") (class "Default")
      (node (ref "R134") (pin "1") (pinfunction "1_1") (pintype "passive"))
      (node (ref "U3") (pin "59") (pinfunction "P9_1_59") (pintype "bidirectional"))
    )
    (net (code "26") (name "C_B_DIR") (class "Default")
      (node (ref "R141") (pin "1") (pinfunction "1_1") (pintype "passive"))
      (node (ref "U3") (pin "70") (pinfunction "P9_8_70") (pintype "bidirectional"))
    )
    (net (code "27") (name "C_B_ENABLE") (class "Default")
      (node (ref "R142") (pin "1") (pinfunction "1_1") (pintype "passive"))
      (node (ref "U3") (pin "68") (pinfunction "P2_1/MD_68") (pintype "bidirectional"))
    )
    (net (code "28") (name "C_B_HLFB_OUT") (class "Default")
      (node (ref "J30") (pin "5") (pinfunction "5-HLFB-_5") (pintype "passive"))
    )
    (net (code "29") (name "C_B_MI_DIR") (class "Default")
      (node (ref "J30") (pin "7") (pinfunction "7-INPUT_A-_7") (pintype "passive"))
      (node (ref "R143") (pin "1") (pinfunction "1_1") (pintype "passive"))
      (node (ref "U62") (pin "3") (pinfunction "C(3)_3") (pintype "input"))
    )
    (net (code "30") (name "C_B_MI_ENABLE") (class "Default")
      (node (ref "J30") (pin "8") (pinfunction "8-ENABLE-_8") (pintype "passive"))
      (node (ref "R144") (pin "1") (pinfunction "1_1") (pintype "passive"))
      (node (ref "U63") (pin "3") (pinfunction "C(3)_3") (pintype "input"))
    )
    (net (code "31") (name "C_B_MI_STEP") (class "Default")
      (node (ref "J30") (pin "6") (pinfunction "6-INPUT_B-_6") (pintype "passive"))
      (node (ref "R139") (pin "1") (pinfunction "1_1") (pintype "passive"))
      (node (ref "U61") (pin "3") (pinfunction "C(3)_3") (pintype "input"))
    )
    (net (code "32") (name "C_B_STEP") (class "Default")
      (node (ref "R140") (pin "1") (pinfunction "1_1") (pintype "passive"))
      (node (ref "U3") (pin "71") (pinfunction "P9_7_71") (pintype "bidirectional"))
    )
    (net (code "33") (name "ESTOP") (class "Default")
      (node (ref "R79") (pin "P$2") (pinfunction "2_P$2") (pintype "passive"))
      (node (ref "R80") (pin "P$2") (pinfunction "2_P$2") (pintype "passive"))
      (node (ref "U21") (pin "2") (pinfunction "E(1)_2") (pintype "output"))
      (node (ref "U3") (pin "69") (pinfunction "P2_0(INPUT_ONLY)_69") (pintype "bidirectional"))
    )
    (net (code "34") (name "ESTOP_RET") (class "Default")
      (node (ref "J9") (pin "P$1") (pinfunction "P$1_P$1") (pintype "bidirectional"))
      (node (ref "R78") (pin "P$1") (pinfunction "1_P$1") (pintype "passive"))
    )
    (net (code "35") (name "ETH") (class "Default")
      (node (ref "U1") (pin "16") (pinfunction "REF_CLK_16") (pintype "bidirectional"))
      (node (ref "U3") (pin "9") (pinfunction "P7_1_9") (pintype "bidirectional"))
    )
    (net (code "36") (name "ETH_CRS_DV") (class "Default")
      (node (ref "R12") (pin "P$1") (pinfunction "1_P$1") (pintype "passive"))
      (node (ref "U3") (pin "13") (pinfunction "P7_5_13") (pintype "bidirectional"))
    )
    (net (code "37") (name "ETH_IRQ14") (class "Default")
      (node (ref "R2") (pin "P$1") (pinfunction "1_P$1") (pintype "passive"))
      (node (ref "U1") (pin "18") (pinfunction "INTRP_18") (pintype "bidirectional"))
      (node (ref "U3") (pin "159") (pinfunction "P0_10/AN103_159") (pintype "bidirectional"))
    )
    (net (code "38") (name "ETH_MDC") (class "Default")
      (node (ref "R4") (pin "P$1") (pinfunction "1_P$1") (pintype "passive"))
      (node (ref "U1") (pin "11") (pinfunction "MDC_11") (pintype "input"))
      (node (ref "U3") (pin "4") (pinfunction "P4_3_4") (pintype "bidirectional"))
    )
    (net (code "39") (name "ETH_MDIO") (class "Default")
      (node (ref "R6") (pin "P$1") (pinfunction "1_P$1") (pintype "passive"))
      (node (ref "U1") (pin "10") (pinfunction "MDIO_10") (pintype "bidirectional"))
      (node (ref "U3") (pin "5") (pinfunction "P4_4_5") (pintype "bidirectional"))
    )
    (net (code "40") (name "ETH_RESET") (class "Default")
      (node (ref "C6") (pin "P$1") (pinfunction "1_P$1") (pintype "passive"))
      (node (ref "R3") (pin "P$1") (pinfunction "1_P$1") (pintype "passive"))
      (node (ref "U1") (pin "24") (pinfunction "~{RST}_24") (pintype "input"))
      (node (ref "U3") (pin "172") (pinfunction "P8_6_172") (pintype "bidirectional"))
    )
    (net (code "41") (name "ETH_RXD0") (class "Default")
      (node (ref "R10") (pin "P$1") (pinfunction "1_P$1") (pintype "passive"))
      (node (ref "U3") (pin "10") (pinfunction "P7_2_10") (pintype "bidirectional"))
    )
    (net (code "42") (name "ETH_RXD1") (class "Default")
      (node (ref "R9") (pin "P$1") (pinfunction "1_P$1") (pintype "passive"))
      (node (ref "U3") (pin "11") (pinfunction "P7_3_11") (pintype "bidirectional"))
    )
    (net (code "43") (name "ETH_RX_ER") (class "Default")
      (node (ref "R11") (pin "P$1") (pinfunction "1_P$1") (pintype "passive"))
      (node (ref "U3") (pin "12") (pinfunction "P7_4_12") (pintype "bidirectional"))
    )
    (net (code "44") (name "ETH_TXD0") (class "Default")
      (node (ref "U1") (pin "20") (pinfunction "TXD0_20") (pintype "input"))
      (node (ref "U3") (pin "8") (pinfunction "P7_0_8") (pintype "bidirectional"))
    )
    (net (code "45") (name "ETH_TXD1") (class "Default")
      (node (ref "U1") (pin "21") (pinfunction "TXD1_21") (pintype "bidirectional"))
      (node (ref "U3") (pin "7") (pinfunction "P4_6_7") (pintype "bidirectional"))
    )
    (net (code "46") (name "ETH_TXD_EN") (class "Default")
      (node (ref "U1") (pin "19") (pinfunction "TXEN_19") (pintype "input"))
      (node (ref "U3") (pin "6") (pinfunction "P4_5_6") (pintype "bidirectional"))
    )
    (net (code "47") (name "GND") (class "Default")
      (node (ref "C1") (pin "P$2") (pinfunction "2_P$2") (pintype "passive"))
      (node (ref "C10") (pin "P$2") (pinfunction "2_P$2") (pintype "passive"))
      (node (ref "C11") (pin "P$2") (pinfunction "2_P$2") (pintype "passive"))
      (node (ref "C12") (pin "P$2") (pinfunction "2_P$2") (pintype "passive"))
      (node (ref "C13") (pin "P$2") (pinfunction "2_P$2") (pintype "passive"))
      (node (ref "C14") (pin "P$2") (pinfunction "2_P$2") (pintype "passive"))
      (node (ref "C15") (pin "P$2") (pinfunction "2_P$2") (pintype "passive"))
      (node (ref "C16") (pin "P$2") (pinfunction "2_P$2") (pintype "passive"))
      (node (ref "C17") (pin "P$2") (pinfunction "2_P$2") (pintype "passive"))
      (node (ref "C18") (pin "P$2") (pinfunction "2_P$2") (pintype "passive"))
      (node (ref "C19") (pin "P$1") (pinfunction "1_P$1") (pintype "passive"))
      (node (ref "C2") (pin "P$2") (pinfunction "2_P$2") (pintype "passive"))
      (node (ref "C20") (pin "P$1") (pinfunction "1_P$1") (pintype "passive"))
      (node (ref "C21") (pin "P$1") (pinfunction "1_P$1") (pintype "passive"))
      (node (ref "C22") (pin "P$1") (pinfunction "1_P$1") (pintype "passive"))
      (node (ref "C23") (pin "P$2") (pinfunction "2_P$2") (pintype "passive"))
      (node (ref "C24") (pin "P$1") (pinfunction "1_P$1") (pintype "passive"))
      (node (ref "C25") (pin "P$1") (pinfunction "1_P$1") (pintype "passive"))
      (node (ref "C26") (pin "P$2") (pinfunction "2_P$2") (pintype "passive"))
      (node (ref "C27") (pin "P$1") (pinfunction "1_P$1") (pintype "passive"))
      (node (ref "C28") (pin "P$2") (pinfunction "2_P$2") (pintype "passive"))
      (node (ref "C29") (pin "P$2") (pinfunction "2_P$2") (pintype "passive"))
      (node (ref "C3") (pin "P$2") (pinfunction "2_P$2") (pintype "passive"))
      (node (ref "C30") (pin "P$1") (pinfunction "1_P$1") (pintype "passive"))
      (node (ref "C31") (pin "2") (pinfunction "2_2") (pintype "passive"))
      (node (ref "C32") (pin "P$2") (pinfunction "2_P$2") (pintype "passive"))
      (node (ref "C33") (pin "P$2") (pinfunction "2_P$2") (pintype "passive"))
      (node (ref "C34") (pin "P$1") (pinfunction "1_P$1") (pintype "passive"))
      (node (ref "C35") (pin "P$1") (pinfunction "1_P$1") (pintype "passive"))
      (node (ref "C36") (pin "P$2") (pinfunction "2_P$2") (pintype "passive"))
      (node (ref "C37") (pin "P$2") (pinfunction "2_P$2") (pintype "passive"))
      (node (ref "C38") (pin "P$1") (pinfunction "1_P$1") (pintype "passive"))
      (node (ref "C39") (pin "P$2") (pinfunction "2_P$2") (pintype "passive"))
      (node (ref "C4") (pin "P$2") (pinfunction "2_P$2") (pintype "passive"))
      (node (ref "C40") (pin "P$2") (pinfunction "2_P$2") (pintype "passive"))
      (node (ref "C41") (pin "P$2") (pinfunction "2_P$2") (pintype "passive"))
      (node (ref "C42") (pin "P$2") (pinfunction "2_P$2") (pintype "passive"))
      (node (ref "C43") (pin "P$1") (pinfunction "1_P$1") (pintype "passive"))
      (node (ref "C5") (pin "P$2") (pinfunction "2_P$2") (pintype "passive"))
      (node (ref "C6") (pin "P$2") (pinfunction "2_P$2") (pintype "passive"))
      (node (ref "C7") (pin "P$2") (pinfunction "2_P$2") (pintype "passive"))
      (node (ref "C8") (pin "P$2") (pinfunction "2_P$2") (pintype "passive"))
      (node (ref "C9") (pin "P$2") (pinfunction "2_P$2") (pintype "passive"))
      (node (ref "J1") (pin "6") (pinfunction "SUPPLY_VOLTAGE_GROUND_6") (pintype "power_in"))
      (node (ref "J2") (pin "P$1") (pinfunction "P$1_P$1") (pintype "bidirectional"))
      (node (ref "J3") (pin "10") (pinfunction "10_10") (pintype "passive"))
      (node (ref "J3") (pin "6") (pinfunction "6_6") (pintype "passive"))
      (node (ref "J3") (pin "8") (pinfunction "8_8") (pintype "passive"))
      (node (ref "J39") (pin "P$1") (pinfunction "P$1_P$1") (pintype "bidirectional"))
      (node (ref "J39") (pin "P$11") (pinfunction "P$11_P$11") (pintype "bidirectional"))
      (node (ref "J39") (pin "P$13") (pinfunction "P$13_P$13") (pintype "bidirectional"))
      (node (ref "J39") (pin "P$15") (pinfunction "P$15_P$15") (pintype "bidirectional"))
      (node (ref "J39") (pin "P$17") (pinfunction "P$17_P$17") (pintype "bidirectional"))
      (node (ref "J39") (pin "P$19") (pinfunction "P$19_P$19") (pintype "bidirectional"))
      (node (ref "J39") (pin "P$3") (pinfunction "P$3_P$3") (pintype "bidirectional"))
      (node (ref "J39") (pin "P$5") (pinfunction "P$5_P$5") (pintype "bidirectional"))
      (node (ref "J39") (pin "P$7") (pinfunction "P$7_P$7") (pintype "bidirectional"))
      (node (ref "J39") (pin "P$9") (pinfunction "P$9_P$9") (pintype "bidirectional"))
      (node (ref "J6") (pin "GND") (pinfunction "GND_GND") (pintype "power_in"))
      (node (ref "J7") (pin "P$5") (pinfunction "GND_P$5") (pintype "bidirectional"))
      (node (ref "LED1") (pin "2") (pinfunction "C_2") (pintype "passive"))
      (node (ref "LED10") (pin "2") (pinfunction "C_2") (pintype "passive"))
      (node (ref "LED11") (pin "2") (pinfunction "C_2") (pintype "passive"))
      (node (ref "LED12") (pin "2") (pinfunction "C_2") (pintype "passive"))
      (node (ref "LED13") (pin "2") (pinfunction "C_2") (pintype "passive"))
      (node (ref "LED14") (pin "2") (pinfunction "C_2") (pintype "passive"))
      (node (ref "LED15") (pin "2") (pinfunction "C_2") (pintype "passive"))
      (node (ref "LED16") (pin "2") (pinfunction "C_2") (pintype "passive"))
      (node (ref "LED3") (pin "2") (pinfunction "C_2") (pintype "passive"))
      (node (ref "LED6") (pin "2") (pinfunction "C_2") (pintype "passive"))
      (node (ref "LED7") (pin "2") (pinfunction "C_2") (pintype "passive"))
      (node (ref "R1") (pin "P$1") (pinfunction "1_P$1") (pintype "passive"))
      (node (ref "R101") (pin "P$1") (pinfunction "1_P$1") (pintype "passive"))
      (node (ref "R21") (pin "P$1") (pinfunction "1_P$1") (pintype "passive"))
      (node (ref "R22") (pin "P$1") (pinfunction "1_P$1") (pintype "passive"))
      (node (ref "R23") (pin "P$1") (pinfunction "1_P$1") (pintype "passive"))
      (node (ref "R24") (pin "P$1") (pinfunction "1_P$1") (pintype "passive"))
      (node (ref "R34") (pin "P$1") (pinfunction "1_P$1") (pintype "passive"))
      (node (ref "R53") (pin "P$1") (pinfunction "1_P$1") (pintype "passive"))
      (node (ref "R56") (pin "P$1") (pinfunction "1_P$1") (pintype "passive"))
      (node (ref "R59") (pin "P$1") (pinfunction "1_P$1") (pintype "passive"))
      (node (ref "R74") (pin "P$1") (pinfunction "1_P$1") (pintype "passive"))
      (node (ref "R77") (pin "P$1") (pinfunction "1_P$1") (pintype "passive"))
      (node (ref "R80") (pin "P$1") (pinfunction "1_P$1") (pintype "passive"))
      (node (ref "R83") (pin "P$1") (pinfunction "1_P$1") (pintype "passive"))
      (node (ref "R98") (pin "P$1") (pinfunction "1_P$1") (pintype "passive"))
      (node (ref "RJ1") (pin "10") (pinfunction "GLO_10") (pintype "bidirectional"))
      (node (ref "RJ1") (pin "8") (pinfunction "P8_8") (pintype "bidirectional"))
      (node (ref "U1") (pin "22") (pinfunction "GND_22") (pintype "power_in"))
      (node (ref "U1") (pin "25") (pinfunction "25_25") (pintype "passive"))
      (node (ref "U10") (pin "2") (pinfunction "E(1)_2") (pintype "output"))
      (node (ref "U11") (pin "2") (pinfunction "E(1)_2") (pintype "output"))
      (node (ref "U12") (pin "2") (pinfunction "E(1)_2") (pintype "output"))
      (node (ref "U13") (pin "2") (pinfunction "E(1)_2") (pintype "output"))
      (node (ref "U14") (pin "2") (pinfunction "E(1)_2") (pintype "output"))
      (node (ref "U15") (pin "2") (pinfunction "E(1)_2") (pintype "output"))
      (node (ref "U16") (pin "2") (pinfunction "E(1)_2") (pintype "output"))
      (node (ref "U17") (pin "2") (pinfunction "E(1)_2") (pintype "output"))
      (node (ref "U2") (pin "2") (pinfunction "GND_2") (pintype "input"))
      (node (ref "U22") (pin "2") (pinfunction "E(1)_2") (pintype "output"))
      (node (ref "U23") (pin "2") (pinfunction "E(1)_2") (pintype "output"))
      (node (ref "U24") (pin "2") (pinfunction "E(1)_2") (pintype "output"))
      (node (ref "U25") (pin "2") (pinfunction "E(1)_2") (pintype "output"))
      (node (ref "U26") (pin "2") (pinfunction "E(1)_2") (pintype "output"))
      (node (ref "U27") (pin "2") (pinfunction "E(1)_2") (pintype "output"))
      (node (ref "U3") (pin "111") (pinfunction "VSS(IO)5_111") (pintype "bidirectional"))
      (node (ref "U3") (pin "124") (pinfunction "VSS(IO)6_124") (pintype "bidirectional"))
      (node (ref "U3") (pin "139") (pinfunction "VSS(IO)7_139") (pintype "bidirectional"))
      (node (ref "U3") (pin "150") (pinfunction "VSS(IO)8_150") (pintype "bidirectional"))
      (node (ref "U3") (pin "153") (pinfunction "VREFL_153") (pintype "bidirectional"))
      (node (ref "U3") (pin "156") (pinfunction "AVSS0_156") (pintype "bidirectional"))
      (node (ref "U3") (pin "157") (pinfunction "VREFL0_157") (pintype "bidirectional"))
      (node (ref "U3") (pin "170") (pinfunction "VSS(IO)9_170") (pintype "bidirectional"))
      (node (ref "U3") (pin "22") (pinfunction "VSS1_22") (pintype "bidirectional"))
      (node (ref "U3") (pin "28") (pinfunction "AVSS_USBHS_28") (pintype "bidirectional"))
      (node (ref "U3") (pin "29") (pinfunction "PVSS_USBHS_29") (pintype "bidirectional"))
      (node (ref "U3") (pin "30") (pinfunction "VSS2_USBHS_30") (pintype "bidirectional"))
      (node (ref "U3") (pin "33") (pinfunction "VSS1_USBHS_33") (pintype "bidirectional"))
      (node (ref "U3") (pin "35") (pinfunction "VSSIO_35") (pintype "bidirectional"))
      (node (ref "U3") (pin "45") (pinfunction "VSS_USB_45") (pintype "bidirectional"))
      (node (ref "U3") (pin "60") (pinfunction "VSS(IO)2_60") (pintype "bidirectional"))
      (node (ref "U3") (pin "63") (pinfunction "VSS(IO/DCDC)_63") (pintype "bidirectional"))
      (node (ref "U3") (pin "66") (pinfunction "VCC_DCDC(IO/DCDC)_66") (pintype "bidirectional"))
      (node (ref "U3") (pin "83") (pinfunction "VSS(IO)3_83") (pintype "bidirectional"))
      (node (ref "U3") (pin "98") (pinfunction "VSS(IO)4_98") (pintype "bidirectional"))
      (node (ref "U34") (pin "2") (pinfunction "E(1)_2") (pintype "output"))
      (node (ref "U35") (pin "2") (pinfunction "E(1)_2") (pintype "output"))
      (node (ref "U36") (pin "2") (pinfunction "E(1)_2") (pintype "output"))
      (node (ref "U37") (pin "2") (pinfunction "E(1)_2") (pintype "output"))
      (node (ref "U38") (pin "2") (pinfunction "E(1)_2") (pintype "output"))
      (node (ref "U39") (pin "2") (pinfunction "E(1)_2") (pintype "output"))
      (node (ref "U46") (pin "2") (pinfunction "E(1)_2") (pintype "output"))
      (node (ref "U47") (pin "2") (pinfunction "E(1)_2") (pintype "output"))
      (node (ref "U48") (pin "2") (pinfunction "E(1)_2") (pintype "output"))
      (node (ref "U49") (pin "2") (pinfunction "E(1)_2") (pintype "output"))
      (node (ref "U50") (pin "2") (pinfunction "E(1)_2") (pintype "output"))
      (node (ref "U51") (pin "2") (pinfunction "E(1)_2") (pintype "output"))
      (node (ref "U58") (pin "2") (pinfunction "E(1)_2") (pintype "output"))
      (node (ref "U59") (pin "2") (pinfunction "E(1)_2") (pintype "output"))
      (node (ref "U6") (pin "2") (pinfunction "E(1)_2") (pintype "output"))
      (node (ref "U60") (pin "2") (pinfunction "E(1)_2") (pintype "output"))
      (node (ref "U61") (pin "2") (pinfunction "E(1)_2") (pintype "output"))
      (node (ref "U62") (pin "2") (pinfunction "E(1)_2") (pintype "output"))
      (node (ref "U63") (pin "2") (pinfunction "E(1)_2") (pintype "output"))
      (node (ref "U7") (pin "2") (pinfunction "E(1)_2") (pintype "output"))
      (node (ref "U70") (pin "2") (pinfunction "E(1)_2") (pintype "output"))
      (node (ref "U71") (pin "2") (pinfunction "E(1)_2") (pintype "output"))
      (node (ref "U72") (pin "2") (pinfunction "E(1)_2") (pintype "output"))
      (node (ref "U73") (pin "2") (pinfunction "E(1)_2") (pintype "output"))
      (node (ref "U74") (pin "2") (pinfunction "E(1)_2") (pintype "output"))
      (node (ref "U75") (pin "2") (pinfunction "E(1)_2") (pintype "output"))
      (node (ref "X1") (pin "2") (pinfunction "2_2") (pintype "bidirectional"))
      (node (ref "X1") (pin "4") (pinfunction "4_4") (pintype "bidirectional"))
      (node (ref "X2") (pin "2") (pinfunction "2_2") (pintype "bidirectional"))
      (node (ref "X2") (pin "4") (pinfunction "4_4") (pintype "bidirectional"))
    )
    (net (code "48") (name "GNDE") (class "Default")
      (node (ref "J1") (pin "S1") (pinfunction "SHIELD_S1") (pintype "passive"))
      (node (ref "J1") (pin "S2") (pinfunction "SHIELD_S2") (pintype "passive"))
      (node (ref "J1") (pin "S3") (pinfunction "SHIELD_S3") (pintype "passive"))
      (node (ref "J1") (pin "S4") (pinfunction "SHIELD_S4") (pintype "passive"))
      (node (ref "J2") (pin "P$4") (pinfunction "P$4_P$4") (pintype "bidirectional"))
      (node (ref "J6") (pin "SHLD1") (pinfunction "SHIELD_1_SHLD1") (pintype "bidirectional"))
      (node (ref "J6") (pin "SHLD2") (pinfunction "SHIELD_2_SHLD2") (pintype "bidirectional"))
      (node (ref "J7") (pin "P$6") (pinfunction "SHIELD1_P$6") (pintype "bidirectional"))
      (node (ref "J7") (pin "P$7") (pinfunction "SHIELD2_P$7") (pintype "bidirectional"))
      (node (ref "J7") (pin "P$8") (pinfunction "SHIELD3_P$8") (pintype "bidirectional"))
      (node (ref "J7") (pin "P$9") (pinfunction "SHIELD4_P$9") (pintype "bidirectional"))
      (node (ref "RJ1") (pin "13") (pinfunction "GNDE0_13") (pintype "bidirectional"))
      (node (ref "RJ1") (pin "14") (pinfunction "GNDE1_14") (pintype "bidirectional"))
    )
    (net (code "49") (name "ID") (class "Default")
      (node (ref "J7") (pin "P$4") (pinfunction "ID_P$4") (pintype "bidirectional"))
    )
    (net (code "50") (name "IIC_1_SCL") (class "Default")
      (node (ref "J8") (pin "P$8") (pinfunction "P$8_P$8") (pintype "bidirectional"))
      (node (ref "R14") (pin "P$2") (pinfunction "2_P$2") (pintype "passive"))
      (node (ref "U3") (pin "132") (pinfunction "P1_0_132") (pintype "bidirectional"))
    )
    (net (code "51") (name "IIC_1_SDA") (class "Default")
      (node (ref "J8") (pin "P$7") (pinfunction "P$7_P$7") (pintype "bidirectional"))
      (node (ref "R15") (pin "P$2") (pinfunction "2_P$2") (pintype "passive"))
      (node (ref "U3") (pin "131") (pinfunction "P1_1_131") (pintype "bidirectional"))
    )
    (net (code "52") (name "LED1{slash}SPEED") (class "Default")
      (node (ref "RJ1") (pin "11") (pinfunction "YLO_11") (pintype "bidirectional"))
      (node (ref "U1") (pin "23") (pinfunction "LED0/ANEN_SPEED_23") (pintype "bidirectional"))
    )
    (net (code "53") (name "LS_01") (class "Default")
      (node (ref "R33") (pin "P$2") (pinfunction "2_P$2") (pintype "passive"))
      (node (ref "R34") (pin "P$2") (pinfunction "2_P$2") (pintype "passive"))
      (node (ref "U3") (pin "50") (pinfunction "P2_6_50") (pintype "bidirectional"))
      (node (ref "U5") (pin "2") (pinfunction "E(1)_2") (pintype "output"))
    )
    (net (code "54") (name "LS_01_RET") (class "Default")
      (node (ref "J11") (pin "P$1") (pinfunction "P$1_P$1") (pintype "bidirectional"))
      (node (ref "R28") (pin "P$1") (pinfunction "1_P$1") (pintype "passive"))
    )
    (net (code "55") (name "LS_02") (class "Default")
      (node (ref "R36") (pin "P$2") (pinfunction "2_P$2") (pintype "passive"))
      (node (ref "R53") (pin "P$2") (pinfunction "2_P$2") (pintype "passive"))
      (node (ref "U3") (pin "51") (pinfunction "P2_5_51") (pintype "bidirectional"))
      (node (ref "U8") (pin "2") (pinfunction "E(1)_2") (pintype "output"))
    )
    (net (code "56") (name "LS_02_RET") (class "Default")
      (node (ref "J12") (pin "P$1") (pinfunction "P$1_P$1") (pintype "bidirectional"))
      (node (ref "R35") (pin "P$1") (pinfunction "1_P$1") (pintype "passive"))
    )
    (net (code "57") (name "LS_03") (class "Default")
      (node (ref "R55") (pin "P$2") (pinfunction "2_P$2") (pintype "passive"))
      (node (ref "R56") (pin "P$2") (pinfunction "2_P$2") (pintype "passive"))
      (node (ref "U3") (pin "53") (pinfunction "P2_3_53") (pintype "bidirectional"))
      (node (ref "U9") (pin "2") (pinfunction "E(1)_2") (pintype "output"))
    )
    (net (code "58") (name "LS_03_RET") (class "Default")
      (node (ref "J19") (pin "P$1") (pinfunction "P$1_P$1") (pintype "bidirectional"))
      (node (ref "R54") (pin "P$1") (pinfunction "1_P$1") (pintype "passive"))
    )
    (net (code "59") (name "LS_04") (class "Default")
      (node (ref "R73") (pin "P$2") (pinfunction "2_P$2") (pintype "passive"))
      (node (ref "R74") (pin "P$2") (pinfunction "2_P$2") (pintype "passive"))
      (node (ref "U19") (pin "2") (pinfunction "E(1)_2") (pintype "output"))
      (node (ref "U3") (pin "54") (pinfunction "P2_2_54") (pintype "bidirectional"))
    )
    (net (code "60") (name "LS_04_RET") (class "Default")
      (node (ref "J20") (pin "P$1") (pinfunction "P$1_P$1") (pintype "bidirectional"))
      (node (ref "R60") (pin "P$1") (pinfunction "1_P$1") (pintype "passive"))
    )
    (net (code "61") (name "LS_05") (class "Default")
      (node (ref "R58") (pin "P$2") (pinfunction "2_P$2") (pintype "passive"))
      (node (ref "R59") (pin "P$2") (pinfunction "2_P$2") (pintype "passive"))
      (node (ref "U18") (pin "2") (pinfunction "E(1)_2") (pintype "output"))
      (node (ref "U3") (pin "81") (pinfunction "P3_5_81") (pintype "bidirectional"))
    )
    (net (code "62") (name "LS_05_RET") (class "Default")
      (node (ref "J27") (pin "P$1") (pinfunction "P$1_P$1") (pintype "bidirectional"))
      (node (ref "R57") (pin "P$1") (pinfunction "1_P$1") (pintype "passive"))
    )
    (net (code "63") (name "LS_06") (class "Default")
      (node (ref "R76") (pin "P$2") (pinfunction "2_P$2") (pintype "passive"))
      (node (ref "R77") (pin "P$2") (pinfunction "2_P$2") (pintype "passive"))
      (node (ref "U20") (pin "2") (pinfunction "E(1)_2") (pintype "output"))
      (node (ref "U3") (pin "82") (pinfunction "P3_4_82") (pintype "bidirectional"))
    )
    (net (code "64") (name "LS_06_RET") (class "Default")
      (node (ref "J28") (pin "P$1") (pinfunction "P$1_P$1") (pintype "bidirectional"))
      (node (ref "R75") (pin "P$1") (pinfunction "1_P$1") (pintype "passive"))
    )
    (net (code "65") (name "LS_07") (class "Default")
      (node (ref "R97") (pin "P$2") (pinfunction "2_P$2") (pintype "passive"))
      (node (ref "R98") (pin "P$2") (pinfunction "2_P$2") (pintype "passive"))
      (node (ref "U29") (pin "2") (pinfunction "E(1)_2") (pintype "output"))
      (node (ref "U3") (pin "86") (pinfunction "P3_2_86") (pintype "bidirectional"))
    )
    (net (code "66") (name "LS_07_RET") (class "Default")
      (node (ref "J31") (pin "P$1") (pinfunction "P$1_P$1") (pintype "bidirectional"))
      (node (ref "R84") (pin "P$1") (pinfunction "1_P$1") (pintype "passive"))
    )
    (net (code "67") (name "LS_08") (class "Default")
      (node (ref "R82") (pin "P$2") (pinfunction "2_P$2") (pintype "passive"))
      (node (ref "R83") (pin "P$2") (pinfunction "2_P$2") (pintype "passive"))
      (node (ref "U28") (pin "2") (pinfunction "E(1)_2") (pintype "output"))
      (node (ref "U3") (pin "87") (pinfunction "P3_1_87") (pintype "bidirectional"))
    )
    (net (code "68") (name "LS_08_RET") (class "Default")
      (node (ref "P1") (pin "P$1") (pinfunction "P$1_P$1") (pintype "bidirectional"))
      (node (ref "R81") (pin "P$1") (pinfunction "1_P$1") (pintype "passive"))
    )
    (net (code "69") (name "LS_09") (class "Default")
      (node (ref "R100") (pin "P$2") (pinfunction "2_P$2") (pintype "passive"))
      (node (ref "R101") (pin "P$2") (pinfunction "2_P$2") (pintype "passive"))
      (node (ref "U3") (pin "92") (pinfunction "P1_11_92") (pintype "bidirectional"))
      (node (ref "U30") (pin "2") (pinfunction "E(1)_2") (pintype "output"))
    )
    (net (code "70") (name "LS_09_RET") (class "Default")
      (node (ref "P3") (pin "P$1") (pinfunction "P$1_P$1") (pintype "bidirectional"))
      (node (ref "R99") (pin "P$1") (pinfunction "1_P$1") (pintype "passive"))
    )
    (net (code "71") (name "N$88") (class "Default")
      (node (ref "J8") (pin "P$20") (pinfunction "P$20_P$20") (pintype "bidirectional"))
    )
    (net (code "72") (name "N$89") (class "Default")
      (node (ref "J8") (pin "P$18") (pinfunction "P$18_P$18") (pintype "bidirectional"))
    )
    (net (code "73") (name "N$90") (class "Default")
      (node (ref "J8") (pin "P$16") (pinfunction "P$16_P$16") (pintype "bidirectional"))
    )
    (net (code "74") (name "N$91") (class "Default")
      (node (ref "J8") (pin "P$14") (pinfunction "P$14_P$14") (pintype "bidirectional"))
    )
    (net (code "75") (name "N$92") (class "Default")
      (node (ref "J8") (pin "P$12") (pinfunction "P$12_P$12") (pintype "bidirectional"))
    )
    (net (code "76") (name "NC") (class "Default")
      (node (ref "J8") (pin "P$6") (pinfunction "P$6_P$6") (pintype "bidirectional"))
      (node (ref "RJ1") (pin "7") (pinfunction "P7_7") (pintype "bidirectional"))
      (node (ref "U3") (pin "79") (pinfunction "P3_7_79") (pintype "bidirectional"))
      (node (ref "U3") (pin "80") (pinfunction "P3_6_80") (pintype "bidirectional"))
      (node (ref "U3") (pin "85") (pinfunction "P3_3_85") (pintype "bidirectional"))
    )
    (net (code "77") (name "Net-(C8-1)") (class "Default")
      (node (ref "C8") (pin "P$1") (pinfunction "1_P$1") (pintype "passive"))
      (node (ref "C9") (pin "P$1") (pinfunction "1_P$1") (pintype "passive"))
      (node (ref "FB1") (pin "2") (pinfunction "P$2_2") (pintype "bidirectional"))
      (node (ref "U1") (pin "2") (pinfunction "VDDA_3.3_2") (pintype "power_in"))
    )
    (net (code "78") (name "Net-(C24-2)") (class "Default")
      (node (ref "C24") (pin "P$2") (pinfunction "2_P$2") (pintype "passive"))
      (node (ref "U3") (pin "148") (pinfunction "VCL2_148") (pintype "bidirectional"))
    )
    (net (code "79") (name "Net-(C28-1)") (class "Default")
      (node (ref "C28") (pin "P$1") (pinfunction "1_P$1") (pintype "passive"))
      (node (ref "J7") (pin "P$1") (pinfunction "VBUS_P$1") (pintype "bidirectional"))
      (node (ref "R16") (pin "P$2") (pinfunction "2_P$2") (pintype "passive"))
      (node (ref "R21") (pin "P$2") (pinfunction "2_P$2") (pintype "passive"))
    )
    (net (code "80") (name "Net-(C33-1)") (class "Default")
      (node (ref "C33") (pin "P$1") (pinfunction "1_P$1") (pintype "passive"))
      (node (ref "U3") (pin "19") (pinfunction "VCLO_19") (pintype "bidirectional"))
    )
    (net (code "81") (name "Net-(C42-1)") (class "Default")
      (node (ref "C42") (pin "P$1") (pinfunction "1_P$1") (pintype "passive"))
      (node (ref "U3") (pin "62") (pinfunction "VCL1_62") (pintype "bidirectional"))
    )
    (net (code "82") (name "Net-(J7-D+)") (class "Default")
      (node (ref "J7") (pin "P$3") (pinfunction "D+_P$3") (pintype "bidirectional"))
      (node (ref "R18") (pin "P$2") (pinfunction "2_P$2") (pintype "passive"))
    )
    (net (code "83") (name "Net-(J7-D-)") (class "Default")
      (node (ref "J7") (pin "P$2") (pinfunction "D-_P$2") (pintype "bidirectional"))
      (node (ref "R17") (pin "P$2") (pinfunction "2_P$2") (pintype "passive"))
    )
    (net (code "84") (name "Net-(LED1-A)") (class "Default")
      (node (ref "LED1") (pin "1") (pinfunction "A_1") (pintype "passive"))
      (node (ref "R5") (pin "P$1") (pinfunction "1_P$1") (pintype "passive"))
    )
    (net (code "85") (name "Net-(LED3-A)") (class "Default")
      (node (ref "LED3") (pin "1") (pinfunction "A_1") (pintype "passive"))
      (node (ref "R33") (pin "P$1") (pinfunction "1_P$1") (pintype "passive"))
    )
    (net (code "86") (name "Net-(LED4-A)") (class "Default")
      (node (ref "LED4") (pin "1") (pinfunction "A_1") (pintype "passive"))
      (node (ref "R32") (pin "P$1") (pinfunction "1_P$1") (pintype "passive"))
    )
    (net (code "87") (name "Net-(LED4-C)") (class "Default")
      (node (ref "LED4") (pin "2") (pinfunction "C_2") (pintype "passive"))
      (node (ref "U$1") (pin "P$1") (pinfunction "VC-_P$1") (pintype "bidirectional"))
      (node (ref "U6") (pin "3") (pinfunction "C(3)_3") (pintype "input"))
    )
    (net (code "88") (name "Net-(LED5-A)") (class "Default")
      (node (ref "LED5") (pin "1") (pinfunction "A_1") (pintype "passive"))
      (node (ref "R31") (pin "P$1") (pinfunction "1_P$1") (pintype "passive"))
    )
    (net (code "89") (name "Net-(LED5-C)") (class "Default")
      (node (ref "LED5") (pin "2") (pinfunction "C_2") (pintype "passive"))
      (node (ref "U$2") (pin "P$1") (pinfunction "VC-_P$1") (pintype "bidirectional"))
      (node (ref "U7") (pin "3") (pinfunction "C(3)_3") (pintype "input"))
    )
    (net (code "90") (name "Net-(LED6-A)") (class "Default")
      (node (ref "LED6") (pin "1") (pinfunction "A_1") (pintype "passive"))
      (node (ref "R36") (pin "P$1") (pinfunction "1_P$1") (pintype "passive"))
    )
    (net (code "91") (name "Net-(LED7-A)") (class "Default")
      (node (ref "LED7") (pin "1") (pinfunction "A_1") (pintype "passive"))
      (node (ref "R55") (pin "P$1") (pinfunction "1_P$1") (pintype "passive"))
    )
    (net (code "92") (name "Net-(LED8-A)") (class "Default")
      (node (ref "LED8") (pin "1") (pinfunction "A_1") (pintype "passive"))
      (node (ref "R52") (pin "P$1") (pinfunction "1_P$1") (pintype "passive"))
    )
    (net (code "93") (name "Net-(LED8-C)") (class "Default")
      (node (ref "LED8") (pin "2") (pinfunction "C_2") (pintype "passive"))
      (node (ref "U$7") (pin "P$1") (pinfunction "VC-_P$1") (pintype "bidirectional"))
      (node (ref "U16") (pin "3") (pinfunction "C(3)_3") (pintype "input"))
    )
    (net (code "94") (name "Net-(LED9-A)") (class "Default")
      (node (ref "LED9") (pin "1") (pinfunction "A_1") (pintype "passive"))
      (node (ref "R51") (pin "P$1") (pinfunction "1_P$1") (pintype "passive"))
    )
    (net (code "95") (name "Net-(LED9-C)") (class "Default")
      (node (ref "LED9") (pin "2") (pinfunction "C_2") (pintype "passive"))
      (node (ref "U$8") (pin "P$1") (pinfunction "VC-_P$1") (pintype "bidirectional"))
      (node (ref "U17") (pin "3") (pinfunction "C(3)_3") (pintype "input"))
    )
    (net (code "96") (name "Net-(LED10-A)") (class "Default")
      (node (ref "LED10") (pin "1") (pinfunction "A_1") (pintype "passive"))
      (node (ref "R58") (pin "P$1") (pinfunction "1_P$1") (pintype "passive"))
    )
    (net (code "97") (name "Net-(LED11-A)") (class "Default")
      (node (ref "LED11") (pin "1") (pinfunction "A_1") (pintype "passive"))
      (node (ref "R73") (pin "P$1") (pinfunction "1_P$1") (pintype "passive"))
    )
    (net (code "98") (name "Net-(LED12-A)") (class "Default")
      (node (ref "LED12") (pin "1") (pinfunction "A_1") (pintype "passive"))
      (node (ref "R76") (pin "P$1") (pinfunction "1_P$1") (pintype "passive"))
    )
    (net (code "99") (name "Net-(LED13-A)") (class "Default")
      (node (ref "LED13") (pin "1") (pinfunction "A_1") (pintype "passive"))
      (node (ref "R79") (pin "P$1") (pinfunction "1_P$1") (pintype "passive"))
    )
    (net (code "100") (name "Net-(LED14-A)") (class "Default")
      (node (ref "LED14") (pin "1") (pinfunction "A_1") (pintype "passive"))
      (node (ref "R82") (pin "P$1") (pinfunction "1_P$1") (pintype "passive"))
    )
    (net (code "101") (name "Net-(LED15-A)") (class "Default")
      (node (ref "LED15") (pin "1") (pinfunction "A_1") (pintype "passive"))
      (node (ref "R97") (pin "P$1") (pinfunction "1_P$1") (pintype "passive"))
    )
    (net (code "102") (name "Net-(LED16-A)") (class "Default")
      (node (ref "LED16") (pin "1") (pinfunction "A_1") (pintype "passive"))
      (node (ref "R100") (pin "P$1") (pinfunction "1_P$1") (pintype "passive"))
    )
    (net (code "103") (name "Net-(R22-2)") (class "Default")
      (node (ref "R22") (pin "P$2") (pinfunction "2_P$2") (pintype "passive"))
      (node (ref "U3") (pin "27") (pinfunction "USBHS_RREF_27") (pintype "bidirectional"))
    )
    (net (code "104") (name "Net-(R23-2)") (class "Default")
      (node (ref "R23") (pin "P$2") (pinfunction "2_P$2") (pintype "passive"))
      (node (ref "U3") (pin "64") (pinfunction "VLO1(DCDC)_64") (pintype "bidirectional"))
    )
    (net (code "105") (name "Net-(R24-2)") (class "Default")
      (node (ref "R24") (pin "P$2") (pinfunction "2_P$2") (pintype "passive"))
      (node (ref "U3") (pin "65") (pinfunction "VLO2(DCDC)_65") (pintype "bidirectional"))
    )
    (net (code "106") (name "Net-(R28-2)") (class "Default")
      (node (ref "R28") (pin "P$2") (pinfunction "2_P$2") (pintype "passive"))
      (node (ref "U5") (pin "1") (pinfunction "B(2)_1") (pintype "input"))
    )
    (net (code "107") (name "Net-(R29-2)") (class "Default")
      (node (ref "R29") (pin "P$2") (pinfunction "2_P$2") (pintype "passive"))
      (node (ref "U6") (pin "1") (pinfunction "B(2)_1") (pintype "input"))
    )
    (net (code "108") (name "Net-(R30-2)") (class "Default")
      (node (ref "R30") (pin "P$2") (pinfunction "2_P$2") (pintype "passive"))
      (node (ref "U7") (pin "1") (pinfunction "B(2)_1") (pintype "input"))
    )
    (net (code "109") (name "Net-(R35-2)") (class "Default")
      (node (ref "R35") (pin "P$2") (pinfunction "2_P$2") (pintype "passive"))
      (node (ref "U8") (pin "1") (pinfunction "B(2)_1") (pintype "input"))
    )
    (net (code "110") (name "Net-(R49-2)") (class "Default")
      (node (ref "R49") (pin "P$2") (pinfunction "2_P$2") (pintype "passive"))
      (node (ref "U16") (pin "1") (pinfunction "B(2)_1") (pintype "input"))
    )
    (net (code "111") (name "Net-(R50-2)") (class "Default")
      (node (ref "R50") (pin "P$2") (pinfunction "2_P$2") (pintype "passive"))
      (node (ref "U17") (pin "1") (pinfunction "B(2)_1") (pintype "input"))
    )
    (net (code "112") (name "Net-(R54-2)") (class "Default")
      (node (ref "R54") (pin "P$2") (pinfunction "2_P$2") (pintype "passive"))
      (node (ref "U9") (pin "1") (pinfunction "B(2)_1") (pintype "input"))
    )
    (net (code "113") (name "Net-(R57-2)") (class "Default")
      (node (ref "R57") (pin "P$2") (pinfunction "2_P$2") (pintype "passive"))
      (node (ref "U18") (pin "1") (pinfunction "B(2)_1") (pintype "input"))
    )
    (net (code "114") (name "Net-(R60-2)") (class "Default")
      (node (ref "R60") (pin "P$2") (pinfunction "2_P$2") (pintype "passive"))
      (node (ref "U19") (pin "1") (pinfunction "B(2)_1") (pintype "input"))
    )
    (net (code "115") (name "Net-(R75-2)") (class "Default")
      (node (ref "R75") (pin "P$2") (pinfunction "2_P$2") (pintype "passive"))
      (node (ref "U20") (pin "1") (pinfunction "B(2)_1") (pintype "input"))
    )
    (net (code "116") (name "Net-(R78-2)") (class "Default")
      (node (ref "R78") (pin "P$2") (pinfunction "2_P$2") (pintype "passive"))
      (node (ref "U21") (pin "1") (pinfunction "B(2)_1") (pintype "input"))
    )
    (net (code "117") (name "Net-(R81-2)") (class "Default")
      (node (ref "R81") (pin "P$2") (pinfunction "2_P$2") (pintype "passive"))
      (node (ref "U28") (pin "1") (pinfunction "B(2)_1") (pintype "input"))
    )
    (net (code "118") (name "Net-(R84-2)") (class "Default")
      (node (ref "R84") (pin "P$2") (pinfunction "2_P$2") (pintype "passive"))
      (node (ref "U29") (pin "1") (pinfunction "B(2)_1") (pintype "input"))
    )
    (net (code "119") (name "Net-(R99-2)") (class "Default")
      (node (ref "R99") (pin "P$2") (pinfunction "2_P$2") (pintype "passive"))
      (node (ref "U30") (pin "1") (pinfunction "B(2)_1") (pintype "input"))
    )
    (net (code "120") (name "Net-(U10-B(2))") (class "Default")
      (node (ref "R38") (pin "2") (pinfunction "2_2") (pintype "passive"))
      (node (ref "U10") (pin "1") (pinfunction "B(2)_1") (pintype "input"))
    )
    (net (code "121") (name "Net-(U11-B(2))") (class "Default")
      (node (ref "R39") (pin "2") (pinfunction "2_2") (pintype "passive"))
      (node (ref "U11") (pin "1") (pinfunction "B(2)_1") (pintype "input"))
    )
    (net (code "122") (name "Net-(U12-B(2))") (class "Default")
      (node (ref "R40") (pin "2") (pinfunction "2_2") (pintype "passive"))
      (node (ref "U12") (pin "1") (pinfunction "B(2)_1") (pintype "input"))
    )
    (net (code "123") (name "Net-(U13-B(2))") (class "Default")
      (node (ref "R44") (pin "2") (pinfunction "2_2") (pintype "passive"))
      (node (ref "U13") (pin "1") (pinfunction "B(2)_1") (pintype "input"))
    )
    (net (code "124") (name "Net-(U14-B(2))") (class "Default")
      (node (ref "R45") (pin "2") (pinfunction "2_2") (pintype "passive"))
      (node (ref "U14") (pin "1") (pinfunction "B(2)_1") (pintype "input"))
    )
    (net (code "125") (name "Net-(U15-B(2))") (class "Default")
      (node (ref "R46") (pin "2") (pinfunction "2_2") (pintype "passive"))
      (node (ref "U15") (pin "1") (pinfunction "B(2)_1") (pintype "input"))
    )
    (net (code "126") (name "Net-(U22-B(2))") (class "Default")
      (node (ref "R62") (pin "2") (pinfunction "2_2") (pintype "passive"))
      (node (ref "U22") (pin "1") (pinfunction "B(2)_1") (pintype "input"))
    )
    (net (code "127") (name "Net-(U23-B(2))") (class "Default")
      (node (ref "R63") (pin "2") (pinfunction "2_2") (pintype "passive"))
      (node (ref "U23") (pin "1") (pinfunction "B(2)_1") (pintype "input"))
    )
    (net (code "128") (name "Net-(U24-B(2))") (class "Default")
      (node (ref "R64") (pin "2") (pinfunction "2_2") (pintype "passive"))
      (node (ref "U24") (pin "1") (pinfunction "B(2)_1") (pintype "input"))
    )
    (net (code "129") (name "Net-(U25-B(2))") (class "Default")
      (node (ref "R68") (pin "2") (pinfunction "2_2") (pintype "passive"))
      (node (ref "U25") (pin "1") (pinfunction "B(2)_1") (pintype "input"))
    )
    (net (code "130") (name "Net-(U26-B(2))") (class "Default")
      (node (ref "R69") (pin "2") (pinfunction "2_2") (pintype "passive"))
      (node (ref "U26") (pin "1") (pinfunction "B(2)_1") (pintype "input"))
    )
    (net (code "131") (name "Net-(U27-B(2))") (class "Default")
      (node (ref "R70") (pin "2") (pinfunction "2_2") (pintype "passive"))
      (node (ref "U27") (pin "1") (pinfunction "B(2)_1") (pintype "input"))
    )
    (net (code "132") (name "Net-(U34-B(2))") (class "Default")
      (node (ref "R86") (pin "2") (pinfunction "2_2") (pintype "passive"))
      (node (ref "U34") (pin "1") (pinfunction "B(2)_1") (pintype "input"))
    )
    (net (code "133") (name "Net-(U35-B(2))") (class "Default")
      (node (ref "R87") (pin "2") (pinfunction "2_2") (pintype "passive"))
      (node (ref "U35") (pin "1") (pinfunction "B(2)_1") (pintype "input"))
    )
    (net (code "134") (name "Net-(U36-B(2))") (class "Default")
      (node (ref "R88") (pin "2") (pinfunction "2_2") (pintype "passive"))
      (node (ref "U36") (pin "1") (pinfunction "B(2)_1") (pintype "input"))
    )
    (net (code "135") (name "Net-(U37-B(2))") (class "Default")
      (node (ref "R92") (pin "2") (pinfunction "2_2") (pintype "passive"))
      (node (ref "U37") (pin "1") (pinfunction "B(2)_1") (pintype "input"))
    )
    (net (code "136") (name "Net-(U38-B(2))") (class "Default")
      (node (ref "R93") (pin "2") (pinfunction "2_2") (pintype "passive"))
      (node (ref "U38") (pin "1") (pinfunction "B(2)_1") (pintype "input"))
    )
    (net (code "137") (name "Net-(U39-B(2))") (class "Default")
      (node (ref "R94") (pin "2") (pinfunction "2_2") (pintype "passive"))
      (node (ref "U39") (pin "1") (pinfunction "B(2)_1") (pintype "input"))
    )
    (net (code "138") (name "Net-(U46-B(2))") (class "Default")
      (node (ref "R110") (pin "2") (pinfunction "2_2") (pintype "passive"))
      (node (ref "U46") (pin "1") (pinfunction "B(2)_1") (pintype "input"))
    )
    (net (code "139") (name "Net-(U47-B(2))") (class "Default")
      (node (ref "R111") (pin "2") (pinfunction "2_2") (pintype "passive"))
      (node (ref "U47") (pin "1") (pinfunction "B(2)_1") (pintype "input"))
    )
    (net (code "140") (name "Net-(U48-B(2))") (class "Default")
      (node (ref "R112") (pin "2") (pinfunction "2_2") (pintype "passive"))
      (node (ref "U48") (pin "1") (pinfunction "B(2)_1") (pintype "input"))
    )
    (net (code "141") (name "Net-(U49-B(2))") (class "Default")
      (node (ref "R116") (pin "2") (pinfunction "2_2") (pintype "passive"))
      (node (ref "U49") (pin "1") (pinfunction "B(2)_1") (pintype "input"))
    )
    (net (code "142") (name "Net-(U50-B(2))") (class "Default")
      (node (ref "R117") (pin "2") (pinfunction "2_2") (pintype "passive"))
      (node (ref "U50") (pin "1") (pinfunction "B(2)_1") (pintype "input"))
    )
    (net (code "143") (name "Net-(U51-B(2))") (class "Default")
      (node (ref "R118") (pin "2") (pinfunction "2_2") (pintype "passive"))
      (node (ref "U51") (pin "1") (pinfunction "B(2)_1") (pintype "input"))
    )
    (net (code "144") (name "Net-(U58-B(2))") (class "Default")
      (node (ref "R134") (pin "2") (pinfunction "2_2") (pintype "passive"))
      (node (ref "U58") (pin "1") (pinfunction "B(2)_1") (pintype "input"))
    )
    (net (code "145") (name "Net-(U59-B(2))") (class "Default")
      (node (ref "R135") (pin "2") (pinfunction "2_2") (pintype "passive"))
      (node (ref "U59") (pin "1") (pinfunction "B(2)_1") (pintype "input"))
    )
    (net (code "146") (name "Net-(U60-B(2))") (class "Default")
      (node (ref "R136") (pin "2") (pinfunction "2_2") (pintype "passive"))
      (node (ref "U60") (pin "1") (pinfunction "B(2)_1") (pintype "input"))
    )
    (net (code "147") (name "Net-(U61-B(2))") (class "Default")
      (node (ref "R140") (pin "2") (pinfunction "2_2") (pintype "passive"))
      (node (ref "U61") (pin "1") (pinfunction "B(2)_1") (pintype "input"))
    )
    (net (code "148") (name "Net-(U62-B(2))") (class "Default")
      (node (ref "R141") (pin "2") (pinfunction "2_2") (pintype "passive"))
      (node (ref "U62") (pin "1") (pinfunction "B(2)_1") (pintype "input"))
    )
    (net (code "149") (name "Net-(U63-B(2))") (class "Default")
      (node (ref "R142") (pin "2") (pinfunction "2_2") (pintype "passive"))
      (node (ref "U63") (pin "1") (pinfunction "B(2)_1") (pintype "input"))
    )
    (net (code "150") (name "Net-(U70-B(2))") (class "Default")
      (node (ref "R158") (pin "2") (pinfunction "2_2") (pintype "passive"))
      (node (ref "U70") (pin "1") (pinfunction "B(2)_1") (pintype "input"))
    )
    (net (code "151") (name "Net-(U71-B(2))") (class "Default")
      (node (ref "R159") (pin "2") (pinfunction "2_2") (pintype "passive"))
      (node (ref "U71") (pin "1") (pinfunction "B(2)_1") (pintype "input"))
    )
    (net (code "152") (name "Net-(U72-B(2))") (class "Default")
      (node (ref "R160") (pin "2") (pinfunction "2_2") (pintype "passive"))
      (node (ref "U72") (pin "1") (pinfunction "B(2)_1") (pintype "input"))
    )
    (net (code "153") (name "Net-(U73-B(2))") (class "Default")
      (node (ref "R164") (pin "2") (pinfunction "2_2") (pintype "passive"))
      (node (ref "U73") (pin "1") (pinfunction "B(2)_1") (pintype "input"))
    )
    (net (code "154") (name "Net-(U74-B(2))") (class "Default")
      (node (ref "R165") (pin "2") (pinfunction "2_2") (pintype "passive"))
      (node (ref "U74") (pin "1") (pinfunction "B(2)_1") (pintype "input"))
    )
    (net (code "155") (name "Net-(U75-B(2))") (class "Default")
      (node (ref "R166") (pin "2") (pinfunction "2_2") (pintype "passive"))
      (node (ref "U75") (pin "1") (pinfunction "B(2)_1") (pintype "input"))
    )
    (net (code "156") (name "P0_00") (class "Default")
      (node (ref "J4") (pin "P$2") (pinfunction "P$2_P$2") (pintype "bidirectional"))
      (node (ref "U3") (pin "169") (pinfunction "P0_0/AN0\\00_169") (pintype "bidirectional"))
    )
    (net (code "157") (name "P0_01") (class "Default")
      (node (ref "J4") (pin "P$1") (pinfunction "P$1_P$1") (pintype "bidirectional"))
      (node (ref "U3") (pin "168") (pinfunction "P0_1/AN001_168") (pintype "bidirectional"))
    )
    (net (code "158") (name "P0_02") (class "Default")
      (node (ref "J39") (pin "P$20") (pinfunction "P$20_P$20") (pintype "bidirectional"))
      (node (ref "R25") (pin "P$1") (pinfunction "1_P$1") (pintype "passive"))
      (node (ref "U3") (pin "167") (pinfunction "P0_2/AN002_167") (pintype "bidirectional"))
    )
    (net (code "159") (name "P0_03") (class "Default")
      (node (ref "J39") (pin "P$18") (pinfunction "P$18_P$18") (pintype "bidirectional"))
      (node (ref "R26") (pin "P$1") (pinfunction "1_P$1") (pintype "passive"))
      (node (ref "U3") (pin "166") (pinfunction "P0_3/PGAVSS000_166") (pintype "bidirectional"))
    )
    (net (code "160") (name "P0_04") (class "Default")
      (node (ref "J39") (pin "P$16") (pinfunction "P$16_P$16") (pintype "bidirectional"))
      (node (ref "R27") (pin "P$1") (pinfunction "1_P$1") (pintype "passive"))
      (node (ref "U3") (pin "165") (pinfunction "P0_4/AN100_165") (pintype "bidirectional"))
    )
    (net (code "161") (name "P0_05") (class "Default")
      (node (ref "J39") (pin "P$14") (pinfunction "P$14_P$14") (pintype "bidirectional"))
      (node (ref "R102") (pin "P$1") (pinfunction "1_P$1") (pintype "passive"))
      (node (ref "U3") (pin "164") (pinfunction "P0_5/AN101_164") (pintype "bidirectional"))
    )
    (net (code "162") (name "P0_06") (class "Default")
      (node (ref "J39") (pin "P$12") (pinfunction "P$12_P$12") (pintype "bidirectional"))
      (node (ref "R103") (pin "P$1") (pinfunction "1_P$1") (pintype "passive"))
      (node (ref "U3") (pin "163") (pinfunction "P0_6/AN102_163") (pintype "bidirectional"))
    )
    (net (code "163") (name "P0_07") (class "Default")
      (node (ref "J39") (pin "P$10") (pinfunction "P$10_P$10") (pintype "bidirectional"))
      (node (ref "R104") (pin "P$1") (pinfunction "1_P$1") (pintype "passive"))
      (node (ref "U3") (pin "162") (pinfunction "P0_7/PGVSS100_162") (pintype "bidirectional"))
    )
    (net (code "164") (name "P0_08") (class "Default")
      (node (ref "J39") (pin "P$8") (pinfunction "P$8_P$8") (pintype "bidirectional"))
      (node (ref "R105") (pin "P$1") (pinfunction "1_P$1") (pintype "passive"))
      (node (ref "U3") (pin "161") (pinfunction "P0_8/AN003_161") (pintype "bidirectional"))
    )
    (net (code "165") (name "P0_09") (class "Default")
      (node (ref "J39") (pin "P$6") (pinfunction "P$6_P$6") (pintype "bidirectional"))
      (node (ref "R106") (pin "P$1") (pinfunction "1_P$1") (pintype "passive"))
      (node (ref "U3") (pin "160") (pinfunction "P0_9/AN004_160") (pintype "bidirectional"))
    )
    (net (code "166") (name "P0_14") (class "Default")
      (node (ref "J39") (pin "P$4") (pinfunction "P$4_P$4") (pintype "bidirectional"))
      (node (ref "R107") (pin "P$1") (pinfunction "1_P$1") (pintype "passive"))
      (node (ref "U3") (pin "152") (pinfunction "P0_14/DA0/AN005/AN105_152") (pintype "bidirectional"))
    )
    (net (code "167") (name "P0_15") (class "Default")
      (node (ref "J39") (pin "P$2") (pinfunction "P$2_P$2") (pintype "bidirectional"))
      (node (ref "R108") (pin "P$1") (pinfunction "1_P$1") (pintype "passive"))
      (node (ref "U3") (pin "151") (pinfunction "P0_15/DA1/AN006/AN106_151") (pintype "bidirectional"))
    )
    (net (code "168") (name "P1_02") (class "Default")
      (node (ref "J8") (pin "P$10") (pinfunction "P$10_P$10") (pintype "bidirectional"))
      (node (ref "U3") (pin "130") (pinfunction "P1_2_130") (pintype "bidirectional"))
    )
    (net (code "169") (name "P1_03") (class "Default")
      (node (ref "J8") (pin "P$9") (pinfunction "P$9_P$9") (pintype "bidirectional"))
      (node (ref "U3") (pin "129") (pinfunction "P1_3_129") (pintype "bidirectional"))
    )
    (net (code "170") (name "P1_04") (class "Default")
      (node (ref "J8") (pin "P$11") (pinfunction "P$11_P$11") (pintype "bidirectional"))
      (node (ref "U3") (pin "128") (pinfunction "P1_4_128") (pintype "bidirectional"))
    )
    (net (code "171") (name "P1_05") (class "Default")
      (node (ref "J8") (pin "P$13") (pinfunction "P$13_P$13") (pintype "bidirectional"))
      (node (ref "U3") (pin "127") (pinfunction "P1_5_127") (pintype "bidirectional"))
    )
    (net (code "172") (name "P1_06") (class "Default")
      (node (ref "J8") (pin "P$15") (pinfunction "P$15_P$15") (pintype "bidirectional"))
      (node (ref "U3") (pin "126") (pinfunction "P1_6_126") (pintype "bidirectional"))
    )
    (net (code "173") (name "P1_07") (class "Default")
      (node (ref "J8") (pin "P$17") (pinfunction "P$17_P$17") (pintype "bidirectional"))
      (node (ref "U3") (pin "125") (pinfunction "P1_7_125") (pintype "bidirectional"))
    )
    (net (code "174") (name "P4_00") (class "Default")
      (node (ref "J4") (pin "P$7") (pinfunction "P$7_P$7") (pintype "bidirectional"))
      (node (ref "U3") (pin "1") (pinfunction "P4_0_1") (pintype "bidirectional"))
    )
    (net (code "175") (name "P4_01") (class "Default")
      (node (ref "J4") (pin "P$8") (pinfunction "P$8_P$8") (pintype "bidirectional"))
      (node (ref "U3") (pin "2") (pinfunction "P4_1_2") (pintype "bidirectional"))
    )
    (net (code "176") (name "P4_02") (class "Default")
      (node (ref "J4") (pin "P$9") (pinfunction "P$9_P$9") (pintype "bidirectional"))
      (node (ref "U3") (pin "3") (pinfunction "P4_2_3") (pintype "bidirectional"))
    )
    (net (code "177") (name "P4_08") (class "Default")
      (node (ref "J4") (pin "P$20") (pinfunction "P$20_P$20") (pintype "bidirectional"))
      (node (ref "U3") (pin "43") (pinfunction "P4_8_43") (pintype "bidirectional"))
    )
    (net (code "178") (name "P4_09") (class "Default")
      (node (ref "J4") (pin "P$19") (pinfunction "P$19_P$19") (pintype "bidirectional"))
      (node (ref "U3") (pin "42") (pinfunction "P4_9_42") (pintype "bidirectional"))
    )
    (net (code "179") (name "P4_10") (class "Default")
      (node (ref "J4") (pin "P$18") (pinfunction "P$18_P$18") (pintype "bidirectional"))
      (node (ref "U3") (pin "41") (pinfunction "P4_10_41") (pintype "bidirectional"))
    )
    (net (code "180") (name "P4_11") (class "Default")
      (node (ref "J4") (pin "P$17") (pinfunction "P$17_P$17") (pintype "bidirectional"))
      (node (ref "U3") (pin "40") (pinfunction "P4_11_40") (pintype "bidirectional"))
    )
    (net (code "181") (name "P4_12") (class "Default")
      (node (ref "J4") (pin "P$16") (pinfunction "P$16_P$16") (pintype "bidirectional"))
      (node (ref "U3") (pin "39") (pinfunction "P4_12_39") (pintype "bidirectional"))
    )
    (net (code "182") (name "P4_13") (class "Default")
      (node (ref "J4") (pin "P$15") (pinfunction "P$15_P$15") (pintype "bidirectional"))
      (node (ref "U3") (pin "38") (pinfunction "P4_13_38") (pintype "bidirectional"))
    )
    (net (code "183") (name "P4_14") (class "Default")
      (node (ref "J4") (pin "P$14") (pinfunction "P$14_P$14") (pintype "bidirectional"))
      (node (ref "U3") (pin "37") (pinfunction "P4_14_37") (pintype "bidirectional"))
    )
    (net (code "184") (name "P4_15") (class "Default")
      (node (ref "J4") (pin "P$13") (pinfunction "P$13_P$13") (pintype "bidirectional"))
      (node (ref "U3") (pin "36") (pinfunction "P4_15_36") (pintype "bidirectional"))
    )
    (net (code "185") (name "P5_11") (class "Default")
      (node (ref "J4") (pin "P$6") (pinfunction "P$6_P$6") (pintype "bidirectional"))
      (node (ref "U3") (pin "176") (pinfunction "P5_11_176") (pintype "bidirectional"))
    )
    (net (code "186") (name "P5_12") (class "Default")
      (node (ref "J4") (pin "P$5") (pinfunction "P$5_P$5") (pintype "bidirectional"))
      (node (ref "U3") (pin "175") (pinfunction "P5_12_175") (pintype "bidirectional"))
    )
    (net (code "187") (name "P5_13") (class "Default")
      (node (ref "J4") (pin "P$4") (pinfunction "P$4_P$4") (pintype "bidirectional"))
      (node (ref "U3") (pin "174") (pinfunction "P5_13_174") (pintype "bidirectional"))
    )
    (net (code "188") (name "P6_00") (class "Default")
      (node (ref "J8") (pin "P$19") (pinfunction "P$19_P$19") (pintype "bidirectional"))
      (node (ref "U3") (pin "122") (pinfunction "P6_0_122") (pintype "bidirectional"))
    )
    (net (code "189") (name "P7_06") (class "Default")
      (node (ref "J4") (pin "P$10") (pinfunction "P$10_P$10") (pintype "bidirectional"))
      (node (ref "U3") (pin "14") (pinfunction "P7_6_14") (pintype "bidirectional"))
    )
    (net (code "190") (name "P7_07") (class "Default")
      (node (ref "J4") (pin "P$11") (pinfunction "P$11_P$11") (pintype "bidirectional"))
      (node (ref "U3") (pin "15") (pinfunction "P7_7_15") (pintype "bidirectional"))
    )
    (net (code "191") (name "P8_00") (class "Default")
      (node (ref "J8") (pin "P$5") (pinfunction "P$5_P$5") (pintype "bidirectional"))
      (node (ref "U3") (pin "133") (pinfunction "P8_0_133") (pintype "bidirectional"))
    )
    (net (code "192") (name "P8_01") (class "Default")
      (node (ref "J8") (pin "P$3") (pinfunction "P$3_P$3") (pintype "bidirectional"))
      (node (ref "U3") (pin "134") (pinfunction "P8_1_134") (pintype "bidirectional"))
    )
    (net (code "193") (name "P8_02") (class "Default")
      (node (ref "J8") (pin "P$4") (pinfunction "P$4_P$4") (pintype "bidirectional"))
      (node (ref "U3") (pin "135") (pinfunction "P8_2_135") (pintype "bidirectional"))
    )
    (net (code "194") (name "P8_03") (class "Default")
      (node (ref "J8") (pin "P$1") (pinfunction "P$1_P$1") (pintype "bidirectional"))
      (node (ref "U3") (pin "136") (pinfunction "P8_3_136") (pintype "bidirectional"))
    )
    (net (code "195") (name "P8_04") (class "Default")
      (node (ref "J8") (pin "P$2") (pinfunction "P$2_P$2") (pintype "bidirectional"))
      (node (ref "U3") (pin "137") (pinfunction "P8_4_137") (pintype "bidirectional"))
    )
    (net (code "196") (name "P8_05") (class "Default")
      (node (ref "J4") (pin "P$3") (pinfunction "P$3_P$3") (pintype "bidirectional"))
      (node (ref "U3") (pin "173") (pinfunction "P8_5_173") (pintype "bidirectional"))
    )
    (net (code "197") (name "PB_00") (class "Default")
      (node (ref "J4") (pin "P$12") (pinfunction "P$12_P$12") (pintype "bidirectional"))
      (node (ref "U3") (pin "16") (pinfunction "PB_0_16") (pintype "bidirectional"))
    )
    (net (code "198") (name "R51") (class "Default")
      (node (ref "R7") (pin "P$1") (pinfunction "1_P$1") (pintype "passive"))
      (node (ref "RJ1") (pin "12") (pinfunction "YHI_12") (pintype "bidirectional"))
    )
    (net (code "199") (name "R52") (class "Default")
      (node (ref "R8") (pin "P$1") (pinfunction "1_P$1") (pintype "passive"))
      (node (ref "RJ1") (pin "9") (pinfunction "GHI_9") (pintype "bidirectional"))
    )
    (net (code "200") (name "RELAY_1") (class "Default")
      (node (ref "R29") (pin "P$1") (pinfunction "1_P$1") (pintype "passive"))
      (node (ref "U3") (pin "56") (pinfunction "P3_14_56") (pintype "bidirectional"))
    )
    (net (code "201") (name "RELAY_2") (class "Default")
      (node (ref "R30") (pin "P$1") (pinfunction "1_P$1") (pintype "passive"))
      (node (ref "U3") (pin "55") (pinfunction "P3_13_55") (pintype "bidirectional"))
    )
    (net (code "202") (name "RELAY_3") (class "Default")
      (node (ref "R49") (pin "P$1") (pinfunction "1_P$1") (pintype "passive"))
      (node (ref "U3") (pin "52") (pinfunction "P2_4_52") (pintype "bidirectional"))
    )
    (net (code "203") (name "RELAY_4") (class "Default")
      (node (ref "R50") (pin "P$1") (pinfunction "1_P$1") (pintype "passive"))
      (node (ref "U3") (pin "49") (pinfunction "P2_7_49") (pintype "bidirectional"))
    )
    (net (code "204") (name "RESET") (class "Default")
      (node (ref "C16") (pin "P$1") (pinfunction "1_P$1") (pintype "passive"))
      (node (ref "J3") (pin "9") (pinfunction "9_9") (pintype "passive"))
      (node (ref "R13") (pin "P$1") (pinfunction "1_P$1") (pintype "passive"))
      (node (ref "U3") (pin "67") (pinfunction "RES#_67") (pintype "bidirectional"))
    )
    (net (code "205") (name "REXT") (class "Default")
      (node (ref "C3") (pin "P$1") (pinfunction "1_P$1") (pintype "passive"))
      (node (ref "R1") (pin "P$2") (pinfunction "2_P$2") (pintype "passive"))
      (node (ref "U1") (pin "9") (pinfunction "REXT_9") (pintype "input"))
    )
    (net (code "206") (name "RO_NEG_1") (class "Default")
      (node (ref "J15") (pin "P$2") (pinfunction "P$2_P$2") (pintype "bidirectional"))
      (node (ref "U$1") (pin "P$3") (pinfunction "VO-_P$3") (pintype "bidirectional"))
    )
    (net (code "207") (name "RO_NEG_2") (class "Default")
      (node (ref "J16") (pin "P$2") (pinfunction "P$2_P$2") (pintype "bidirectional"))
      (node (ref "U$2") (pin "P$3") (pinfunction "VO-_P$3") (pintype "bidirectional"))
    )
    (net (code "208") (name "RO_NEG_3") (class "Default")
      (node (ref "J23") (pin "P$2") (pinfunction "P$2_P$2") (pintype "bidirectional"))
      (node (ref "U$7") (pin "P$3") (pinfunction "VO-_P$3") (pintype "bidirectional"))
    )
    (net (code "209") (name "RO_NEG_4") (class "Default")
      (node (ref "J24") (pin "P$2") (pinfunction "P$2_P$2") (pintype "bidirectional"))
      (node (ref "U$8") (pin "P$3") (pinfunction "VO-_P$3") (pintype "bidirectional"))
    )
    (net (code "210") (name "RO_POS_1") (class "Default")
      (node (ref "J15") (pin "P$1") (pinfunction "P$1_P$1") (pintype "bidirectional"))
      (node (ref "U$1") (pin "P$4") (pinfunction "VO+_P$4") (pintype "bidirectional"))
    )
    (net (code "211") (name "RO_POS_2") (class "Default")
      (node (ref "J16") (pin "P$1") (pinfunction "P$1_P$1") (pintype "bidirectional"))
      (node (ref "U$2") (pin "P$4") (pinfunction "VO+_P$4") (pintype "bidirectional"))
    )
    (net (code "212") (name "RO_POS_3") (class "Default")
      (node (ref "J23") (pin "P$1") (pinfunction "P$1_P$1") (pintype "bidirectional"))
      (node (ref "U$7") (pin "P$4") (pinfunction "VO+_P$4") (pintype "bidirectional"))
    )
    (net (code "213") (name "RO_POS_4") (class "Default")
      (node (ref "J24") (pin "P$1") (pinfunction "P$1_P$1") (pintype "bidirectional"))
      (node (ref "U$8") (pin "P$4") (pinfunction "VO+_P$4") (pintype "bidirectional"))
    )
    (net (code "214") (name "RXD0") (class "Default")
      (node (ref "R10") (pin "P$2") (pinfunction "2_P$2") (pintype "passive"))
      (node (ref "U1") (pin "13") (pinfunction "RXD0_13") (pintype "bidirectional"))
    )
    (net (code "215") (name "RXD1") (class "Default")
      (node (ref "R9") (pin "P$2") (pinfunction "2_P$2") (pintype "passive"))
      (node (ref "U1") (pin "12") (pinfunction "RXD1_12") (pintype "bidirectional"))
    )
    (net (code "216") (name "RXER") (class "Default")
      (node (ref "R11") (pin "P$2") (pinfunction "2_P$2") (pintype "passive"))
      (node (ref "U1") (pin "17") (pinfunction "RXER_17") (pintype "bidirectional"))
    )
    (net (code "217") (name "RXM") (class "Default")
      (node (ref "RJ1") (pin "6") (pinfunction "RD-_6") (pintype "bidirectional"))
      (node (ref "U1") (pin "3") (pinfunction "RXM_3") (pintype "bidirectional"))
    )
    (net (code "218") (name "RXP") (class "Default")
      (node (ref "RJ1") (pin "3") (pinfunction "RD+_3") (pintype "bidirectional"))
      (node (ref "U1") (pin "4") (pinfunction "RXP_4") (pintype "bidirectional"))
    )
    (net (code "219") (name "SD1_CD") (class "Default")
      (node (ref "J1") (pin "10") (pinfunction "CD_SWITCH2_10") (pintype "bidirectional"))
      (node (ref "U3") (pin "146") (pinfunction "P5_6/AN019_146") (pintype "bidirectional"))
    )
    (net (code "220") (name "SD1_CLK") (class "Default")
      (node (ref "J1") (pin "5") (pinfunction "CLOCK_5") (pintype "bidirectional"))
      (node (ref "U3") (pin "140") (pinfunction "P5_0/AN016_140") (pintype "bidirectional"))
    )
    (net (code "221") (name "SD1_CMD") (class "Default")
      (node (ref "J1") (pin "3") (pinfunction "COMMAND/RESPONSE_3") (pintype "bidirectional"))
      (node (ref "U3") (pin "141") (pinfunction "P5_1/AN116_141") (pintype "bidirectional"))
    )
    (net (code "222") (name "SD1_DAT0") (class "Default")
      (node (ref "J1") (pin "7") (pinfunction "DATA_LINE[BIT_0]_7") (pintype "bidirectional"))
      (node (ref "U3") (pin "142") (pinfunction "P5_2/AN017_142") (pintype "bidirectional"))
    )
    (net (code "223") (name "SD1_DAT1") (class "Default")
      (node (ref "J1") (pin "8") (pinfunction "DATA_LINE[BIT_1]_8") (pintype "bidirectional"))
      (node (ref "U3") (pin "143") (pinfunction "P5_3/AN117_143") (pintype "bidirectional"))
    )
    (net (code "224") (name "SD1_DAT2") (class "Default")
      (node (ref "J1") (pin "1") (pinfunction "DATA_LINE[BIT_2]_1") (pintype "bidirectional"))
      (node (ref "U3") (pin "144") (pinfunction "P5_4/AN018_144") (pintype "bidirectional"))
    )
    (net (code "225") (name "SD1_DAT3") (class "Default")
      (node (ref "J1") (pin "2") (pinfunction "CARD_DETECT/DATA_LINE[BIT_3]_2") (pintype "bidirectional"))
      (node (ref "U3") (pin "145") (pinfunction "P5_5/AN118_145") (pintype "bidirectional"))
    )
    (net (code "226") (name "SD1_WP") (class "Default")
      (node (ref "J1") (pin "9") (pinfunction "CD_SWITCH1_9") (pintype "bidirectional"))
      (node (ref "U3") (pin "147") (pinfunction "P5_7/AN119_147") (pintype "bidirectional"))
    )
    (net (code "227") (name "TCK") (class "Default")
      (node (ref "J3") (pin "7") (pinfunction "7_7") (pintype "passive"))
      (node (ref "U3") (pin "88") (pinfunction "P3_0_88") (pintype "bidirectional"))
    )
    (net (code "228") (name "TDI") (class "Default")
      (node (ref "J3") (pin "1") (pinfunction "1_1") (pintype "passive"))
      (node (ref "U3") (pin "91") (pinfunction "P1_10_91") (pintype "bidirectional"))
    )
    (net (code "229") (name "TDO") (class "Default")
      (node (ref "J3") (pin "3") (pinfunction "3_3") (pintype "passive"))
      (node (ref "U3") (pin "90") (pinfunction "P1_9_90") (pintype "bidirectional"))
    )
    (net (code "230") (name "TMS") (class "Default")
      (node (ref "J3") (pin "5") (pinfunction "5_5") (pintype "passive"))
      (node (ref "U3") (pin "89") (pinfunction "P1_8_89") (pintype "bidirectional"))
    )
    (net (code "231") (name "TXM") (class "Default")
      (node (ref "RJ1") (pin "2") (pinfunction "TD-_2") (pintype "bidirectional"))
      (node (ref "U1") (pin "5") (pinfunction "TXM_5") (pintype "bidirectional"))
    )
    (net (code "232") (name "TXP") (class "Default")
      (node (ref "RJ1") (pin "1") (pinfunction "TD+_1") (pintype "bidirectional"))
      (node (ref "U1") (pin "6") (pinfunction "TXP_6") (pintype "bidirectional"))
    )
    (net (code "233") (name "USBHS_FAULT") (class "Default")
      (node (ref "R19") (pin "P$1") (pinfunction "1_P$1") (pintype "passive"))
      (node (ref "U2") (pin "3") (pinfunction "FLG_3") (pintype "input"))
      (node (ref "U3") (pin "78") (pinfunction "P3_8_78") (pintype "bidirectional"))
    )
    (net (code "234") (name "USBHS_N") (class "Default")
      (node (ref "J6") (pin "D-") (pinfunction "D-_D-") (pintype "bidirectional"))
      (node (ref "U3") (pin "31") (pinfunction "USBHS_DM_31") (pintype "bidirectional"))
    )
    (net (code "235") (name "USBHS_P") (class "Default")
      (node (ref "J6") (pin "D+") (pinfunction "D+_D+") (pintype "bidirectional"))
      (node (ref "U3") (pin "32") (pinfunction "USBHS_DP_32") (pintype "bidirectional"))
    )
    (net (code "236") (name "USBHS_VBUS") (class "Default")
      (node (ref "C29") (pin "P$1") (pinfunction "1_P$1") (pintype "passive"))
      (node (ref "C31") (pin "1") (pinfunction "1_1") (pintype "passive"))
      (node (ref "J6") (pin "VBUS") (pinfunction "VBUS_VBUS") (pintype "power_in"))
      (node (ref "U2") (pin "5") (pinfunction "OUT_5") (pintype "input"))
      (node (ref "U3") (pin "17") (pinfunction "PB_1_17") (pintype "bidirectional"))
    )
    (net (code "237") (name "USBHS_VBUSEN") (class "Default")
      (node (ref "R20") (pin "P$1") (pinfunction "1_P$1") (pintype "passive"))
      (node (ref "U2") (pin "1") (pinfunction "EN_1") (pintype "input"))
    )
    (net (code "238") (name "USB_N") (class "Default")
      (node (ref "R17") (pin "P$1") (pinfunction "1_P$1") (pintype "passive"))
      (node (ref "U3") (pin "46") (pinfunction "USB_DM_46") (pintype "bidirectional"))
    )
    (net (code "239") (name "USB_P") (class "Default")
      (node (ref "R18") (pin "P$1") (pinfunction "1_P$1") (pintype "passive"))
      (node (ref "U3") (pin "47") (pinfunction "USB_DP_47") (pintype "bidirectional"))
    )
    (net (code "240") (name "USB_VBUS_B") (class "Default")
      (node (ref "R16") (pin "P$1") (pinfunction "1_P$1") (pintype "passive"))
      (node (ref "U3") (pin "44") (pinfunction "P4_7_44") (pintype "bidirectional"))
    )
    (net (code "241") (name "VCL_F(FLASH)") (class "Default")
      (node (ref "C34") (pin "P$2") (pinfunction "2_P$2") (pintype "passive"))
      (node (ref "U3") (pin "112") (pinfunction "VCL_F(FLASH)_112") (pintype "bidirectional"))
    )
    (net (code "242") (name "VDD") (class "Default")
      (node (ref "C14") (pin "P$1") (pinfunction "1_P$1") (pintype "passive"))
      (node (ref "C15") (pin "P$1") (pinfunction "1_P$1") (pintype "passive"))
      (node (ref "C19") (pin "P$2") (pinfunction "2_P$2") (pintype "passive"))
      (node (ref "C20") (pin "P$2") (pinfunction "2_P$2") (pintype "passive"))
      (node (ref "C21") (pin "P$2") (pinfunction "2_P$2") (pintype "passive"))
      (node (ref "C22") (pin "P$2") (pinfunction "2_P$2") (pintype "passive"))
      (node (ref "C25") (pin "P$2") (pinfunction "2_P$2") (pintype "passive"))
      (node (ref "C27") (pin "P$2") (pinfunction "2_P$2") (pintype "passive"))
      (node (ref "C30") (pin "P$2") (pinfunction "2_P$2") (pintype "passive"))
      (node (ref "C35") (pin "P$2") (pinfunction "2_P$2") (pintype "passive"))
      (node (ref "C36") (pin "P$1") (pinfunction "1_P$1") (pintype "passive"))
      (node (ref "C38") (pin "P$2") (pinfunction "2_P$2") (pintype "passive"))
      (node (ref "C39") (pin "P$1") (pinfunction "1_P$1") (pintype "passive"))
      (node (ref "C4") (pin "P$1") (pinfunction "1_P$1") (pintype "passive"))
      (node (ref "C40") (pin "P$1") (pinfunction "1_P$1") (pintype "passive"))
      (node (ref "C41") (pin "P$1") (pinfunction "1_P$1") (pintype "passive"))
      (node (ref "C43") (pin "P$2") (pinfunction "2_P$2") (pintype "passive"))
      (node (ref "C5") (pin "P$1") (pinfunction "1_P$1") (pintype "passive"))
      (node (ref "C7") (pin "P$1") (pinfunction "1_P$1") (pintype "passive"))
      (node (ref "FB1") (pin "1") (pinfunction "P$1_1") (pintype "bidirectional"))
      (node (ref "J1") (pin "4") (pinfunction "SUPPLY_VOLTAGE_4") (pintype "power_in"))
      (node (ref "J3") (pin "2") (pinfunction "2_2") (pintype "passive"))
      (node (ref "J3") (pin "4") (pinfunction "4_4") (pintype "passive"))
      (node (ref "L1") (pin "2") (pinfunction "P$2_2") (pintype "bidirectional"))
      (node (ref "R102") (pin "P$2") (pinfunction "2_P$2") (pintype "passive"))
      (node (ref "R103") (pin "P$2") (pinfunction "2_P$2") (pintype "passive"))
      (node (ref "R104") (pin "P$2") (pinfunction "2_P$2") (pintype "passive"))
      (node (ref "R105") (pin "P$2") (pinfunction "2_P$2") (pintype "passive"))
      (node (ref "R106") (pin "P$2") (pinfunction "2_P$2") (pintype "passive"))
      (node (ref "R107") (pin "P$2") (pinfunction "2_P$2") (pintype "passive"))
      (node (ref "R108") (pin "P$2") (pinfunction "2_P$2") (pintype "passive"))
      (node (ref "R13") (pin "P$2") (pinfunction "2_P$2") (pintype "passive"))
      (node (ref "R14") (pin "P$1") (pinfunction "1_P$1") (pintype "passive"))
      (node (ref "R15") (pin "P$1") (pinfunction "1_P$1") (pintype "passive"))
      (node (ref "R2") (pin "P$2") (pinfunction "2_P$2") (pintype "passive"))
      (node (ref "R25") (pin "P$2") (pinfunction "2_P$2") (pintype "passive"))
      (node (ref "R26") (pin "P$2") (pinfunction "2_P$2") (pintype "passive"))
      (node (ref "R27") (pin "P$2") (pinfunction "2_P$2") (pintype "passive"))
      (node (ref "R3") (pin "P$2") (pinfunction "2_P$2") (pintype "passive"))
      (node (ref "R4") (pin "P$2") (pinfunction "2_P$2") (pintype "passive"))
      (node (ref "R5") (pin "P$2") (pinfunction "2_P$2") (pintype "passive"))
      (node (ref "R6") (pin "P$2") (pinfunction "2_P$2") (pintype "passive"))
      (node (ref "R7") (pin "P$2") (pinfunction "2_P$2") (pintype "passive"))
      (node (ref "R8") (pin "P$2") (pinfunction "2_P$2") (pintype "passive"))
      (node (ref "U1") (pin "14") (pinfunction "VDDIO_14") (pintype "power_in"))
      (node (ref "U3") (pin "110") (pinfunction "VCC(IO)5_110") (pintype "bidirectional"))
      (node (ref "U3") (pin "123") (pinfunction "VCC(IO)6_123") (pintype "bidirectional"))
      (node (ref "U3") (pin "138") (pinfunction "VCC(IO)7_138") (pintype "bidirectional"))
      (node (ref "U3") (pin "149") (pinfunction "VCC(IO)8_149") (pintype "bidirectional"))
      (node (ref "U3") (pin "154") (pinfunction "VREFH_154") (pintype "bidirectional"))
      (node (ref "U3") (pin "155") (pinfunction "AVCC0_155") (pintype "bidirectional"))
      (node (ref "U3") (pin "158") (pinfunction "VREFH0_158") (pintype "bidirectional"))
      (node (ref "U3") (pin "171") (pinfunction "VCC(IO)9_171") (pintype "bidirectional"))
      (node (ref "U3") (pin "25") (pinfunction "VCC1_25") (pintype "bidirectional"))
      (node (ref "U3") (pin "26") (pinfunction "AVCC_SUBHS_26") (pintype "bidirectional"))
      (node (ref "U3") (pin "34") (pinfunction "VCC_USBHS_34") (pintype "bidirectional"))
      (node (ref "U3") (pin "48") (pinfunction "VCC_USB_48") (pintype "bidirectional"))
      (node (ref "U3") (pin "61") (pinfunction "VCC(IO)2_61") (pintype "bidirectional"))
      (node (ref "U3") (pin "84") (pinfunction "VCC(IO)3_84") (pintype "bidirectional"))
      (node (ref "U3") (pin "97") (pinfunction "VCC(IO)4_97") (pintype "bidirectional"))
    )
    (net (code "243") (name "VDD5") (class "Default")
      (node (ref "C23") (pin "P$1") (pinfunction "1_P$1") (pintype "passive"))
      (node (ref "C26") (pin "P$1") (pinfunction "1_P$1") (pintype "passive"))
      (node (ref "J2") (pin "P$3") (pinfunction "P$3_P$3") (pintype "bidirectional"))
      (node (ref "R19") (pin "P$2") (pinfunction "2_P$2") (pintype "passive"))
      (node (ref "R20") (pin "P$2") (pinfunction "2_P$2") (pintype "passive"))
      (node (ref "R31") (pin "P$2") (pinfunction "2_P$2") (pintype "passive"))
      (node (ref "R32") (pin "P$2") (pinfunction "2_P$2") (pintype "passive"))
      (node (ref "R51") (pin "P$2") (pinfunction "2_P$2") (pintype "passive"))
      (node (ref "R52") (pin "P$2") (pinfunction "2_P$2") (pintype "passive"))
      (node (ref "U$1") (pin "P$2") (pinfunction "VC+_P$2") (pintype "bidirectional"))
      (node (ref "U$2") (pin "P$2") (pinfunction "VC+_P$2") (pintype "bidirectional"))
      (node (ref "U$7") (pin "P$2") (pinfunction "VC+_P$2") (pintype "bidirectional"))
      (node (ref "U$8") (pin "P$2") (pinfunction "VC+_P$2") (pintype "bidirectional"))
      (node (ref "U18") (pin "3") (pinfunction "C(3)_3") (pintype "input"))
      (node (ref "U19") (pin "3") (pinfunction "C(3)_3") (pintype "input"))
      (node (ref "U2") (pin "4") (pinfunction "VIN_4") (pintype "input"))
      (node (ref "U20") (pin "3") (pinfunction "C(3)_3") (pintype "input"))
      (node (ref "U21") (pin "3") (pinfunction "C(3)_3") (pintype "input"))
      (node (ref "U28") (pin "3") (pinfunction "C(3)_3") (pintype "input"))
      (node (ref "U29") (pin "3") (pinfunction "C(3)_3") (pintype "input"))
      (node (ref "U30") (pin "3") (pinfunction "C(3)_3") (pintype "input"))
      (node (ref "U5") (pin "3") (pinfunction "C(3)_3") (pintype "input"))
      (node (ref "U8") (pin "3") (pinfunction "C(3)_3") (pintype "input"))
      (node (ref "U9") (pin "3") (pinfunction "C(3)_3") (pintype "input"))
    )
    (net (code "244") (name "VDD12") (class "Default")
      (node (ref "J10") (pin "P$1") (pinfunction "P$1_P$1") (pintype "bidirectional"))
      (node (ref "J10") (pin "P$2") (pinfunction "P$2_P$2") (pintype "bidirectional"))
      (node (ref "J11") (pin "P$2") (pinfunction "P$2_P$2") (pintype "bidirectional"))
      (node (ref "J12") (pin "P$2") (pinfunction "P$2_P$2") (pintype "bidirectional"))
      (node (ref "J13") (pin "1") (pinfunction "1-HLFB+_1") (pintype "passive"))
      (node (ref "J13") (pin "2") (pinfunction "2-INPUT_B+_2") (pintype "passive"))
      (node (ref "J13") (pin "3") (pinfunction "3-INPUT_A+_3") (pintype "passive"))
      (node (ref "J13") (pin "4") (pinfunction "4-ENABLE+_4") (pintype "passive"))
      (node (ref "J14") (pin "1") (pinfunction "1-HLFB+_1") (pintype "passive"))
      (node (ref "J14") (pin "2") (pinfunction "2-INPUT_B+_2") (pintype "passive"))
      (node (ref "J14") (pin "3") (pinfunction "3-INPUT_A+_3") (pintype "passive"))
      (node (ref "J14") (pin "4") (pinfunction "4-ENABLE+_4") (pintype "passive"))
      (node (ref "J17") (pin "1") (pinfunction "1-HLFB+_1") (pintype "passive"))
      (node (ref "J17") (pin "2") (pinfunction "2-INPUT_B+_2") (pintype "passive"))
      (node (ref "J17") (pin "3") (pinfunction "3-INPUT_A+_3") (pintype "passive"))
      (node (ref "J17") (pin "4") (pinfunction "4-ENABLE+_4") (pintype "passive"))
      (node (ref "J18") (pin "1") (pinfunction "1-HLFB+_1") (pintype "passive"))
      (node (ref "J18") (pin "2") (pinfunction "2-INPUT_B+_2") (pintype "passive"))
      (node (ref "J18") (pin "3") (pinfunction "3-INPUT_A+_3") (pintype "passive"))
      (node (ref "J18") (pin "4") (pinfunction "4-ENABLE+_4") (pintype "passive"))
      (node (ref "J19") (pin "P$2") (pinfunction "P$2_P$2") (pintype "bidirectional"))
      (node (ref "J20") (pin "P$2") (pinfunction "P$2_P$2") (pintype "bidirectional"))
      (node (ref "J21") (pin "1") (pinfunction "1-HLFB+_1") (pintype "passive"))
      (node (ref "J21") (pin "2") (pinfunction "2-INPUT_B+_2") (pintype "passive"))
      (node (ref "J21") (pin "3") (pinfunction "3-INPUT_A+_3") (pintype "passive"))
      (node (ref "J21") (pin "4") (pinfunction "4-ENABLE+_4") (pintype "passive"))
      (node (ref "J22") (pin "1") (pinfunction "1-HLFB+_1") (pintype "passive"))
      (node (ref "J22") (pin "2") (pinfunction "2-INPUT_B+_2") (pintype "passive"))
      (node (ref "J22") (pin "3") (pinfunction "3-INPUT_A+_3") (pintype "passive"))
      (node (ref "J22") (pin "4") (pinfunction "4-ENABLE+_4") (pintype "passive"))
      (node (ref "J25") (pin "1") (pinfunction "1-HLFB+_1") (pintype "passive"))
      (node (ref "J25") (pin "2") (pinfunction "2-INPUT_B+_2") (pintype "passive"))
      (node (ref "J25") (pin "3") (pinfunction "3-INPUT_A+_3") (pintype "passive"))
      (node (ref "J25") (pin "4") (pinfunction "4-ENABLE+_4") (pintype "passive"))
      (node (ref "J26") (pin "1") (pinfunction "1-HLFB+_1") (pintype "passive"))
      (node (ref "J26") (pin "2") (pinfunction "2-INPUT_B+_2") (pintype "passive"))
      (node (ref "J26") (pin "3") (pinfunction "3-INPUT_A+_3") (pintype "passive"))
      (node (ref "J26") (pin "4") (pinfunction "4-ENABLE+_4") (pintype "passive"))
      (node (ref "J27") (pin "P$2") (pinfunction "P$2_P$2") (pintype "bidirectional"))
      (node (ref "J28") (pin "P$2") (pinfunction "P$2_P$2") (pintype "bidirectional"))
      (node (ref "J29") (pin "1") (pinfunction "1-HLFB+_1") (pintype "passive"))
      (node (ref "J29") (pin "2") (pinfunction "2-INPUT_B+_2") (pintype "passive"))
      (node (ref "J29") (pin "3") (pinfunction "3-INPUT_A+_3") (pintype "passive"))
      (node (ref "J29") (pin "4") (pinfunction "4-ENABLE+_4") (pintype "passive"))
      (node (ref "J30") (pin "1") (pinfunction "1-HLFB+_1") (pintype "passive"))
      (node (ref "J30") (pin "2") (pinfunction "2-INPUT_B+_2") (pintype "passive"))
      (node (ref "J30") (pin "3") (pinfunction "3-INPUT_A+_3") (pintype "passive"))
      (node (ref "J30") (pin "4") (pinfunction "4-ENABLE+_4") (pintype "passive"))
      (node (ref "J31") (pin "P$2") (pinfunction "P$2_P$2") (pintype "bidirectional"))
      (node (ref "J33") (pin "1") (pinfunction "1-HLFB+_1") (pintype "passive"))
      (node (ref "J33") (pin "2") (pinfunction "2-INPUT_B+_2") (pintype "passive"))
      (node (ref "J33") (pin "3") (pinfunction "3-INPUT_A+_3") (pintype "passive"))
      (node (ref "J33") (pin "4") (pinfunction "4-ENABLE+_4") (pintype "passive"))
      (node (ref "J34") (pin "1") (pinfunction "1-HLFB+_1") (pintype "passive"))
      (node (ref "J34") (pin "2") (pinfunction "2-INPUT_B+_2") (pintype "passive"))
      (node (ref "J34") (pin "3") (pinfunction "3-INPUT_A+_3") (pintype "passive"))
      (node (ref "J34") (pin "4") (pinfunction "4-ENABLE+_4") (pintype "passive"))
      (node (ref "J9") (pin "P$2") (pinfunction "P$2_P$2") (pintype "bidirectional"))
      (node (ref "P2") (pin "P$1") (pinfunction "P$1_P$1") (pintype "bidirectional"))
      (node (ref "P4") (pin "P$1") (pinfunction "P$1_P$1") (pintype "bidirectional"))
      (node (ref "R109") (pin "2") (pinfunction "2_2") (pintype "passive"))
      (node (ref "R113") (pin "2") (pinfunction "2_2") (pintype "passive"))
      (node (ref "R114") (pin "2") (pinfunction "2_2") (pintype "passive"))
      (node (ref "R115") (pin "2") (pinfunction "2_2") (pintype "passive"))
      (node (ref "R119") (pin "2") (pinfunction "2_2") (pintype "passive"))
      (node (ref "R120") (pin "2") (pinfunction "2_2") (pintype "passive"))
      (node (ref "R133") (pin "2") (pinfunction "2_2") (pintype "passive"))
      (node (ref "R137") (pin "2") (pinfunction "2_2") (pintype "passive"))
      (node (ref "R138") (pin "2") (pinfunction "2_2") (pintype "passive"))
      (node (ref "R139") (pin "2") (pinfunction "2_2") (pintype "passive"))
      (node (ref "R143") (pin "2") (pinfunction "2_2") (pintype "passive"))
      (node (ref "R144") (pin "2") (pinfunction "2_2") (pintype "passive"))
      (node (ref "R157") (pin "2") (pinfunction "2_2") (pintype "passive"))
      (node (ref "R161") (pin "2") (pinfunction "2_2") (pintype "passive"))
      (node (ref "R162") (pin "2") (pinfunction "2_2") (pintype "passive"))
      (node (ref "R163") (pin "2") (pinfunction "2_2") (pintype "passive"))
      (node (ref "R167") (pin "2") (pinfunction "2_2") (pintype "passive"))
      (node (ref "R168") (pin "2") (pinfunction "2_2") (pintype "passive"))
      (node (ref "R37") (pin "2") (pinfunction "2_2") (pintype "passive"))
      (node (ref "R41") (pin "2") (pinfunction "2_2") (pintype "passive"))
      (node (ref "R42") (pin "2") (pinfunction "2_2") (pintype "passive"))
      (node (ref "R43") (pin "2") (pinfunction "2_2") (pintype "passive"))
      (node (ref "R47") (pin "2") (pinfunction "2_2") (pintype "passive"))
      (node (ref "R48") (pin "2") (pinfunction "2_2") (pintype "passive"))
      (node (ref "R61") (pin "2") (pinfunction "2_2") (pintype "passive"))
      (node (ref "R65") (pin "2") (pinfunction "2_2") (pintype "passive"))
      (node (ref "R66") (pin "2") (pinfunction "2_2") (pintype "passive"))
      (node (ref "R67") (pin "2") (pinfunction "2_2") (pintype "passive"))
      (node (ref "R71") (pin "2") (pinfunction "2_2") (pintype "passive"))
      (node (ref "R72") (pin "2") (pinfunction "2_2") (pintype "passive"))
      (node (ref "R85") (pin "2") (pinfunction "2_2") (pintype "passive"))
      (node (ref "R89") (pin "2") (pinfunction "2_2") (pintype "passive"))
      (node (ref "R90") (pin "2") (pinfunction "2_2") (pintype "passive"))
      (node (ref "R91") (pin "2") (pinfunction "2_2") (pintype "passive"))
      (node (ref "R95") (pin "2") (pinfunction "2_2") (pintype "passive"))
      (node (ref "R96") (pin "2") (pinfunction "2_2") (pintype "passive"))
    )
    (net (code "245") (name "VDDIN") (class "Default")
      (node (ref "J2") (pin "P$2") (pinfunction "P$2_P$2") (pintype "bidirectional"))
      (node (ref "L1") (pin "1") (pinfunction "P$1_1") (pintype "bidirectional"))
    )
    (net (code "246") (name "VDD_1.2") (class "Default")
      (node (ref "C10") (pin "P$1") (pinfunction "1_P$1") (pintype "passive"))
      (node (ref "C11") (pin "P$1") (pinfunction "1_P$1") (pintype "passive"))
      (node (ref "U1") (pin "1") (pinfunction "VDD_1.2_1") (pintype "power_in"))
    )
    (net (code "247") (name "WF_A_DIR") (class "Default")
      (node (ref "R159") (pin "1") (pinfunction "1_1") (pintype "passive"))
      (node (ref "U3") (pin "99") (pinfunction "P6_8_99") (pintype "bidirectional"))
    )
    (net (code "248") (name "WF_A_ENABLE") (class "Default")
      (node (ref "R160") (pin "1") (pinfunction "1_1") (pintype "passive"))
      (node (ref "U3") (pin "96") (pinfunction "P1_15_96") (pintype "bidirectional"))
    )
    (net (code "249") (name "WF_A_HLFB_OUT") (class "Default")
      (node (ref "J33") (pin "5") (pinfunction "5-HLFB-_5") (pintype "passive"))
    )
    (net (code "250") (name "WF_A_MI_DIR") (class "Default")
      (node (ref "J33") (pin "7") (pinfunction "7-INPUT_A-_7") (pintype "passive"))
      (node (ref "R161") (pin "1") (pinfunction "1_1") (pintype "passive"))
      (node (ref "U71") (pin "3") (pinfunction "C(3)_3") (pintype "input"))
    )
    (net (code "251") (name "WF_A_MI_ENABLE") (class "Default")
      (node (ref "J33") (pin "8") (pinfunction "8-ENABLE-_8") (pintype "passive"))
      (node (ref "R162") (pin "1") (pinfunction "1_1") (pintype "passive"))
      (node (ref "U72") (pin "3") (pinfunction "C(3)_3") (pintype "input"))
    )
    (net (code "252") (name "WF_A_MI_STEP") (class "Default")
      (node (ref "J33") (pin "6") (pinfunction "6-INPUT_B-_6") (pintype "passive"))
      (node (ref "R157") (pin "1") (pinfunction "1_1") (pintype "passive"))
      (node (ref "U70") (pin "3") (pinfunction "C(3)_3") (pintype "input"))
    )
    (net (code "253") (name "WF_A_STEP") (class "Default")
      (node (ref "R158") (pin "1") (pinfunction "1_1") (pintype "passive"))
      (node (ref "U3") (pin "100") (pinfunction "P6_9_100") (pintype "bidirectional"))
    )
    (net (code "254") (name "WF_B_DIR") (class "Default")
      (node (ref "R165") (pin "1") (pinfunction "1_1") (pintype "passive"))
      (node (ref "U3") (pin "94") (pinfunction "P1_13_94") (pintype "bidirectional"))
    )
    (net (code "255") (name "WF_B_ENABLE") (class "Default")
      (node (ref "R166") (pin "1") (pinfunction "1_1") (pintype "passive"))
      (node (ref "U3") (pin "93") (pinfunction "P1_12_93") (pintype "bidirectional"))
    )
    (net (code "256") (name "WF_B_HLFB_OUT") (class "Default")
      (node (ref "J34") (pin "5") (pinfunction "5-HLFB-_5") (pintype "passive"))
    )
    (net (code "257") (name "WF_B_MI_ENABLE") (class "Default")
      (node (ref "J34") (pin "8") (pinfunction "8-ENABLE-_8") (pintype "passive"))
      (node (ref "R168") (pin "1") (pinfunction "1_1") (pintype "passive"))
      (node (ref "U75") (pin "3") (pinfunction "C(3)_3") (pintype "input"))
    )
    (net (code "258") (name "WF_B_MI_STEP") (class "Default")
      (node (ref "J34") (pin "6") (pinfunction "6-INPUT_B-_6") (pintype "passive"))
      (node (ref "R163") (pin "1") (pinfunction "1_1") (pintype "passive"))
      (node (ref "U73") (pin "3") (pinfunction "C(3)_3") (pintype "input"))
    )
    (net (code "259") (name "WF_B_STEP") (class "Default")
      (node (ref "R164") (pin "1") (pinfunction "1_1") (pintype "passive"))
      (node (ref "U3") (pin "95") (pinfunction "P1_14_95") (pintype "bidirectional"))
    )
    (net (code "260") (name "XCIN") (class "Default")
      (node (ref "C32") (pin "P$1") (pinfunction "1_P$1") (pintype "passive"))
      (node (ref "U3") (pin "20") (pinfunction "XCIN_20") (pintype "bidirectional"))
      (node (ref "X3") (pin "P$1") (pinfunction "P$1_P$1") (pintype "bidirectional"))
    )
    (net (code "261") (name "XCOUT") (class "Default")
      (node (ref "C37") (pin "P$1") (pinfunction "1_P$1") (pintype "passive"))
      (node (ref "U3") (pin "21") (pinfunction "XCOUT_21") (pintype "bidirectional"))
      (node (ref "X3") (pin "P$2") (pinfunction "P$2_P$2") (pintype "bidirectional"))
    )
    (net (code "262") (name "XII") (class "Default")
      (node (ref "C1") (pin "P$1") (pinfunction "1_P$1") (pintype "passive"))
      (node (ref "U1") (pin "8") (pinfunction "XI_8") (pintype "input"))
      (node (ref "X1") (pin "1") (pinfunction "1_1") (pintype "bidirectional"))
    )
    (net (code "263") (name "XOO") (class "Default")
      (node (ref "C2") (pin "P$1") (pinfunction "1_P$1") (pintype "passive"))
      (node (ref "U1") (pin "7") (pinfunction "XO_7") (pintype "output"))
      (node (ref "X1") (pin "3") (pinfunction "3_3") (pintype "bidirectional"))
    )
    (net (code "264") (name "XTAL1") (class "Default")
      (node (ref "C17") (pin "P$1") (pinfunction "1_P$1") (pintype "passive"))
      (node (ref "U3") (pin "23") (pinfunction "P2_13/XTAL_23") (pintype "bidirectional"))
      (node (ref "X2") (pin "1") (pinfunction "1_1") (pintype "bidirectional"))
    )
    (net (code "265") (name "XTAL2") (class "Default")
      (node (ref "C18") (pin "P$1") (pinfunction "1_P$1") (pintype "passive"))
      (node (ref "U3") (pin "24") (pinfunction "P2_12/EXTAL_24") (pintype "bidirectional"))
      (node (ref "X2") (pin "3") (pinfunction "3_3") (pintype "bidirectional"))
    )
    (net (code "266") (name "X_A_DIR") (class "Default")
      (node (ref "R39") (pin "1") (pinfunction "1_1") (pintype "passive"))
      (node (ref "U3") (pin "117") (pinfunction "P6_5_117") (pintype "bidirectional"))
    )
    (net (code "267") (name "X_A_ENABLE") (class "Default")
      (node (ref "R40") (pin "1") (pinfunction "1_1") (pintype "passive"))
      (node (ref "U3") (pin "116") (pinfunction "P6_6_116") (pintype "bidirectional"))
    )
    (net (code "268") (name "X_A_HLFB_OUT") (class "Default")
      (node (ref "J13") (pin "5") (pinfunction "5-HLFB-_5") (pintype "passive"))
    )
    (net (code "269") (name "X_A_MI_DIR") (class "Default")
      (node (ref "J13") (pin "7") (pinfunction "7-INPUT_A-_7") (pintype "passive"))
      (node (ref "R41") (pin "1") (pinfunction "1_1") (pintype "passive"))
      (node (ref "U11") (pin "3") (pinfunction "C(3)_3") (pintype "input"))
    )
    (net (code "270") (name "X_A_MI_ENABLE") (class "Default")
      (node (ref "J13") (pin "8") (pinfunction "8-ENABLE-_8") (pintype "passive"))
      (node (ref "R42") (pin "1") (pinfunction "1_1") (pintype "passive"))
      (node (ref "U12") (pin "3") (pinfunction "C(3)_3") (pintype "input"))
    )
    (net (code "271") (name "X_A_MI_STEP") (class "Default")
      (node (ref "J13") (pin "6") (pinfunction "6-INPUT_B-_6") (pintype "passive"))
      (node (ref "R37") (pin "1") (pinfunction "1_1") (pintype "passive"))
      (node (ref "U10") (pin "3") (pinfunction "C(3)_3") (pintype "input"))
    )
    (net (code "272") (name "X_A_STEP") (class "Default")
      (node (ref "R38") (pin "1") (pinfunction "1_1") (pintype "passive"))
      (node (ref "U3") (pin "118") (pinfunction "P6_4_118") (pintype "bidirectional"))
    )
    (net (code "273") (name "X_B_DIR") (class "Default")
      (node (ref "R45") (pin "1") (pinfunction "1_1") (pintype "passive"))
      (node (ref "U3") (pin "120") (pinfunction "P6_2_120") (pintype "bidirectional"))
    )
    (net (code "274") (name "X_B_ENABLE") (class "Default")
      (node (ref "R46") (pin "1") (pinfunction "1_1") (pintype "passive"))
      (node (ref "U3") (pin "119") (pinfunction "P6_3_119") (pintype "bidirectional"))
    )
    (net (code "275") (name "X_B_HLFB_OUT") (class "Default")
      (node (ref "J14") (pin "5") (pinfunction "5-HLFB-_5") (pintype "passive"))
    )
    (net (code "276") (name "X_B_MI_DIR") (class "Default")
      (node (ref "J14") (pin "7") (pinfunction "7-INPUT_A-_7") (pintype "passive"))
      (node (ref "R47") (pin "1") (pinfunction "1_1") (pintype "passive"))
      (node (ref "U14") (pin "3") (pinfunction "C(3)_3") (pintype "input"))
    )
    (net (code "277") (name "X_B_MI_ENABLE") (class "Default")
      (node (ref "J14") (pin "8") (pinfunction "8-ENABLE-_8") (pintype "passive"))
      (node (ref "R48") (pin "1") (pinfunction "1_1") (pintype "passive"))
      (node (ref "U15") (pin "3") (pinfunction "C(3)_3") (pintype "input"))
    )
    (net (code "278") (name "X_B_MI_STEP") (class "Default")
      (node (ref "J14") (pin "6") (pinfunction "6-INPUT_B-_6") (pintype "passive"))
      (node (ref "R43") (pin "1") (pinfunction "1_1") (pintype "passive"))
      (node (ref "U13") (pin "3") (pinfunction "C(3)_3") (pintype "input"))
    )
    (net (code "279") (name "X_B_STEP") (class "Default")
      (node (ref "R44") (pin "1") (pinfunction "1_1") (pintype "passive"))
      (node (ref "U3") (pin "121") (pinfunction "P6_1_121") (pintype "bidirectional"))
    )
    (net (code "280") (name "Y_A_DIR") (class "Default")
      (node (ref "R63") (pin "1") (pinfunction "1_1") (pintype "passive"))
      (node (ref "U3") (pin "114") (pinfunction "PA_0_114") (pintype "bidirectional"))
    )
    (net (code "281") (name "Y_A_ENABLE") (class "Default")
      (node (ref "R64") (pin "1") (pinfunction "1_1") (pintype "passive"))
      (node (ref "U3") (pin "113") (pinfunction "PA_1_113") (pintype "bidirectional"))
    )
    (net (code "282") (name "Y_A_HLFB_OUT") (class "Default")
      (node (ref "J17") (pin "5") (pinfunction "5-HLFB-_5") (pintype "passive"))
    )
    (net (code "283") (name "Y_A_MI_DIR") (class "Default")
      (node (ref "J17") (pin "7") (pinfunction "7-INPUT_A-_7") (pintype "passive"))
      (node (ref "R65") (pin "1") (pinfunction "1_1") (pintype "passive"))
      (node (ref "U23") (pin "3") (pinfunction "C(3)_3") (pintype "input"))
    )
    (net (code "284") (name "Y_A_MI_ENABLE") (class "Default")
      (node (ref "J17") (pin "8") (pinfunction "8-ENABLE-_8") (pintype "passive"))
      (node (ref "R66") (pin "1") (pinfunction "1_1") (pintype "passive"))
      (node (ref "U24") (pin "3") (pinfunction "C(3)_3") (pintype "input"))
    )
    (net (code "285") (name "Y_A_MI_STEP") (class "Default")
      (node (ref "J17") (pin "6") (pinfunction "6-INPUT_B-_6") (pintype "passive"))
      (node (ref "R61") (pin "1") (pinfunction "1_1") (pintype "passive"))
      (node (ref "U22") (pin "3") (pinfunction "C(3)_3") (pintype "input"))
    )
    (net (code "286") (name "Y_A_STEP") (class "Default")
      (node (ref "R62") (pin "1") (pinfunction "1_1") (pintype "passive"))
      (node (ref "U3") (pin "115") (pinfunction "P6_7_115") (pintype "bidirectional"))
    )
    (net (code "287") (name "Y_B_DIR") (class "Default")
      (node (ref "R69") (pin "1") (pinfunction "1_1") (pintype "passive"))
      (node (ref "U3") (pin "108") (pinfunction "PA_9_108") (pintype "bidirectional"))
    )
    (net (code "288") (name "Y_B_ENABLE") (class "Default")
      (node (ref "R70") (pin "1") (pinfunction "1_1") (pintype "passive"))
      (node (ref "U3") (pin "107") (pinfunction "PA_8_107") (pintype "bidirectional"))
    )
    (net (code "289") (name "Y_B_HLFB_OUT") (class "Default")
      (node (ref "J18") (pin "5") (pinfunction "5-HLFB-_5") (pintype "passive"))
    )
    (net (code "290") (name "Y_B_MI_DIR") (class "Default")
      (node (ref "J18") (pin "7") (pinfunction "7-INPUT_A-_7") (pintype "passive"))
      (node (ref "R71") (pin "1") (pinfunction "1_1") (pintype "passive"))
      (node (ref "U26") (pin "3") (pinfunction "C(3)_3") (pintype "input"))
    )
    (net (code "291") (name "Y_B_MI_ENABLE") (class "Default")
      (node (ref "J18") (pin "8") (pinfunction "8-ENABLE-_8") (pintype "passive"))
      (node (ref "R72") (pin "1") (pinfunction "1_1") (pintype "passive"))
      (node (ref "U27") (pin "3") (pinfunction "C(3)_3") (pintype "input"))
    )
    (net (code "292") (name "Y_B_MI_STEP") (class "Default")
      (node (ref "J18") (pin "6") (pinfunction "6-INPUT_B-_6") (pintype "passive"))
      (node (ref "R67") (pin "1") (pinfunction "1_1") (pintype "passive"))
      (node (ref "U25") (pin "3") (pinfunction "C(3)_3") (pintype "input"))
    )
    (net (code "293") (name "Y_B_STEP") (class "Default")
      (node (ref "R68") (pin "1") (pinfunction "1_1") (pintype "passive"))
      (node (ref "U3") (pin "109") (pinfunction "PA_10_109") (pintype "bidirectional"))
    )
    (net (code "294") (name "Z_A_DIR") (class "Default")
      (node (ref "R87") (pin "1") (pinfunction "1_1") (pintype "passive"))
      (node (ref "U3") (pin "105") (pinfunction "P6_14_105") (pintype "bidirectional"))
    )
    (net (code "295") (name "Z_A_ENABLE") (class "Default")
      (node (ref "R88") (pin "1") (pinfunction "1_1") (pintype "passive"))
      (node (ref "U3") (pin "104") (pinfunction "P6_13_104") (pintype "bidirectional"))
    )
    (net (code "296") (name "Z_A_HLFB_OUT") (class "Default")
      (node (ref "J21") (pin "5") (pinfunction "5-HLFB-_5") (pintype "passive"))
    )
    (net (code "297") (name "Z_A_MI_DIR") (class "Default")
      (node (ref "J21") (pin "7") (pinfunction "7-INPUT_A-_7") (pintype "passive"))
      (node (ref "R89") (pin "1") (pinfunction "1_1") (pintype "passive"))
      (node (ref "U35") (pin "3") (pinfunction "C(3)_3") (pintype "input"))
    )
    (net (code "298") (name "Z_A_MI_ENABLE") (class "Default")
      (node (ref "J21") (pin "8") (pinfunction "8-ENABLE-_8") (pintype "passive"))
      (node (ref "R90") (pin "1") (pinfunction "1_1") (pintype "passive"))
      (node (ref "U36") (pin "3") (pinfunction "C(3)_3") (pintype "input"))
    )
    (net (code "299") (name "Z_A_MI_STEP") (class "Default")
      (node (ref "J21") (pin "6") (pinfunction "6-INPUT_B-_6") (pintype "passive"))
      (node (ref "R85") (pin "1") (pinfunction "1_1") (pintype "passive"))
      (node (ref "U34") (pin "3") (pinfunction "C(3)_3") (pintype "input"))
    )
    (net (code "300") (name "Z_A_STEP") (class "Default")
      (node (ref "R86") (pin "1") (pinfunction "1_1") (pintype "passive"))
      (node (ref "U3") (pin "106") (pinfunction "P6_15_106") (pintype "bidirectional"))
    )
    (net (code "301") (name "Z_B_DIR") (class "Default")
      (node (ref "R93") (pin "1") (pinfunction "1_1") (pintype "passive"))
      (node (ref "U3") (pin "102") (pinfunction "P6_11_102") (pintype "bidirectional"))
    )
    (net (code "302") (name "Z_B_ENABLE") (class "Default")
      (node (ref "R94") (pin "1") (pinfunction "1_1") (pintype "passive"))
      (node (ref "U3") (pin "101") (pinfunction "P6_10_101") (pintype "bidirectional"))
    )
    (net (code "303") (name "Z_B_HLFB_OUT") (class "Default")
      (node (ref "J22") (pin "5") (pinfunction "5-HLFB-_5") (pintype "passive"))
    )
    (net (code "304") (name "Z_B_MI_DIR") (class "Default")
      (node (ref "J22") (pin "7") (pinfunction "7-INPUT_A-_7") (pintype "passive"))
      (node (ref "R95") (pin "1") (pinfunction "1_1") (pintype "passive"))
      (node (ref "U38") (pin "3") (pinfunction "C(3)_3") (pintype "input"))
    )
    (net (code "305") (name "Z_B_MI_ENABLE") (class "Default")
      (node (ref "J22") (pin "8") (pinfunction "8-ENABLE-_8") (pintype "passive"))
      (node (ref "R96") (pin "1") (pinfunction "1_1") (pintype "passive"))
      (node (ref "U39") (pin "3") (pinfunction "C(3)_3") (pintype "input"))
    )
    (net (code "306") (name "Z_B_MI_STEP") (class "Default")
      (node (ref "J22") (pin "6") (pinfunction "6-INPUT_B-_6") (pintype "passive"))
      (node (ref "R91") (pin "1") (pinfunction "1_1") (pintype "passive"))
      (node (ref "U37") (pin "3") (pinfunction "C(3)_3") (pintype "input"))
    )
    (net (code "307") (name "Z_B_STEP") (class "Default")
      (node (ref "R92") (pin "1") (pinfunction "1_1") (pintype "passive"))
      (node (ref "U3") (pin "103") (pinfunction "P6_12_103") (pintype "bidirectional"))
    )
    (net (code "308") (name "unconnected-(U3-VBAT-Pad18)") (class "Default")
      (node (ref "U3") (pin "18") (pinfunction "VBAT_18") (pintype "bidirectional"))
    )
  )
)
